# Proto_Business_Card.net
KiCad netlist of a schematic drawn in EAGLE
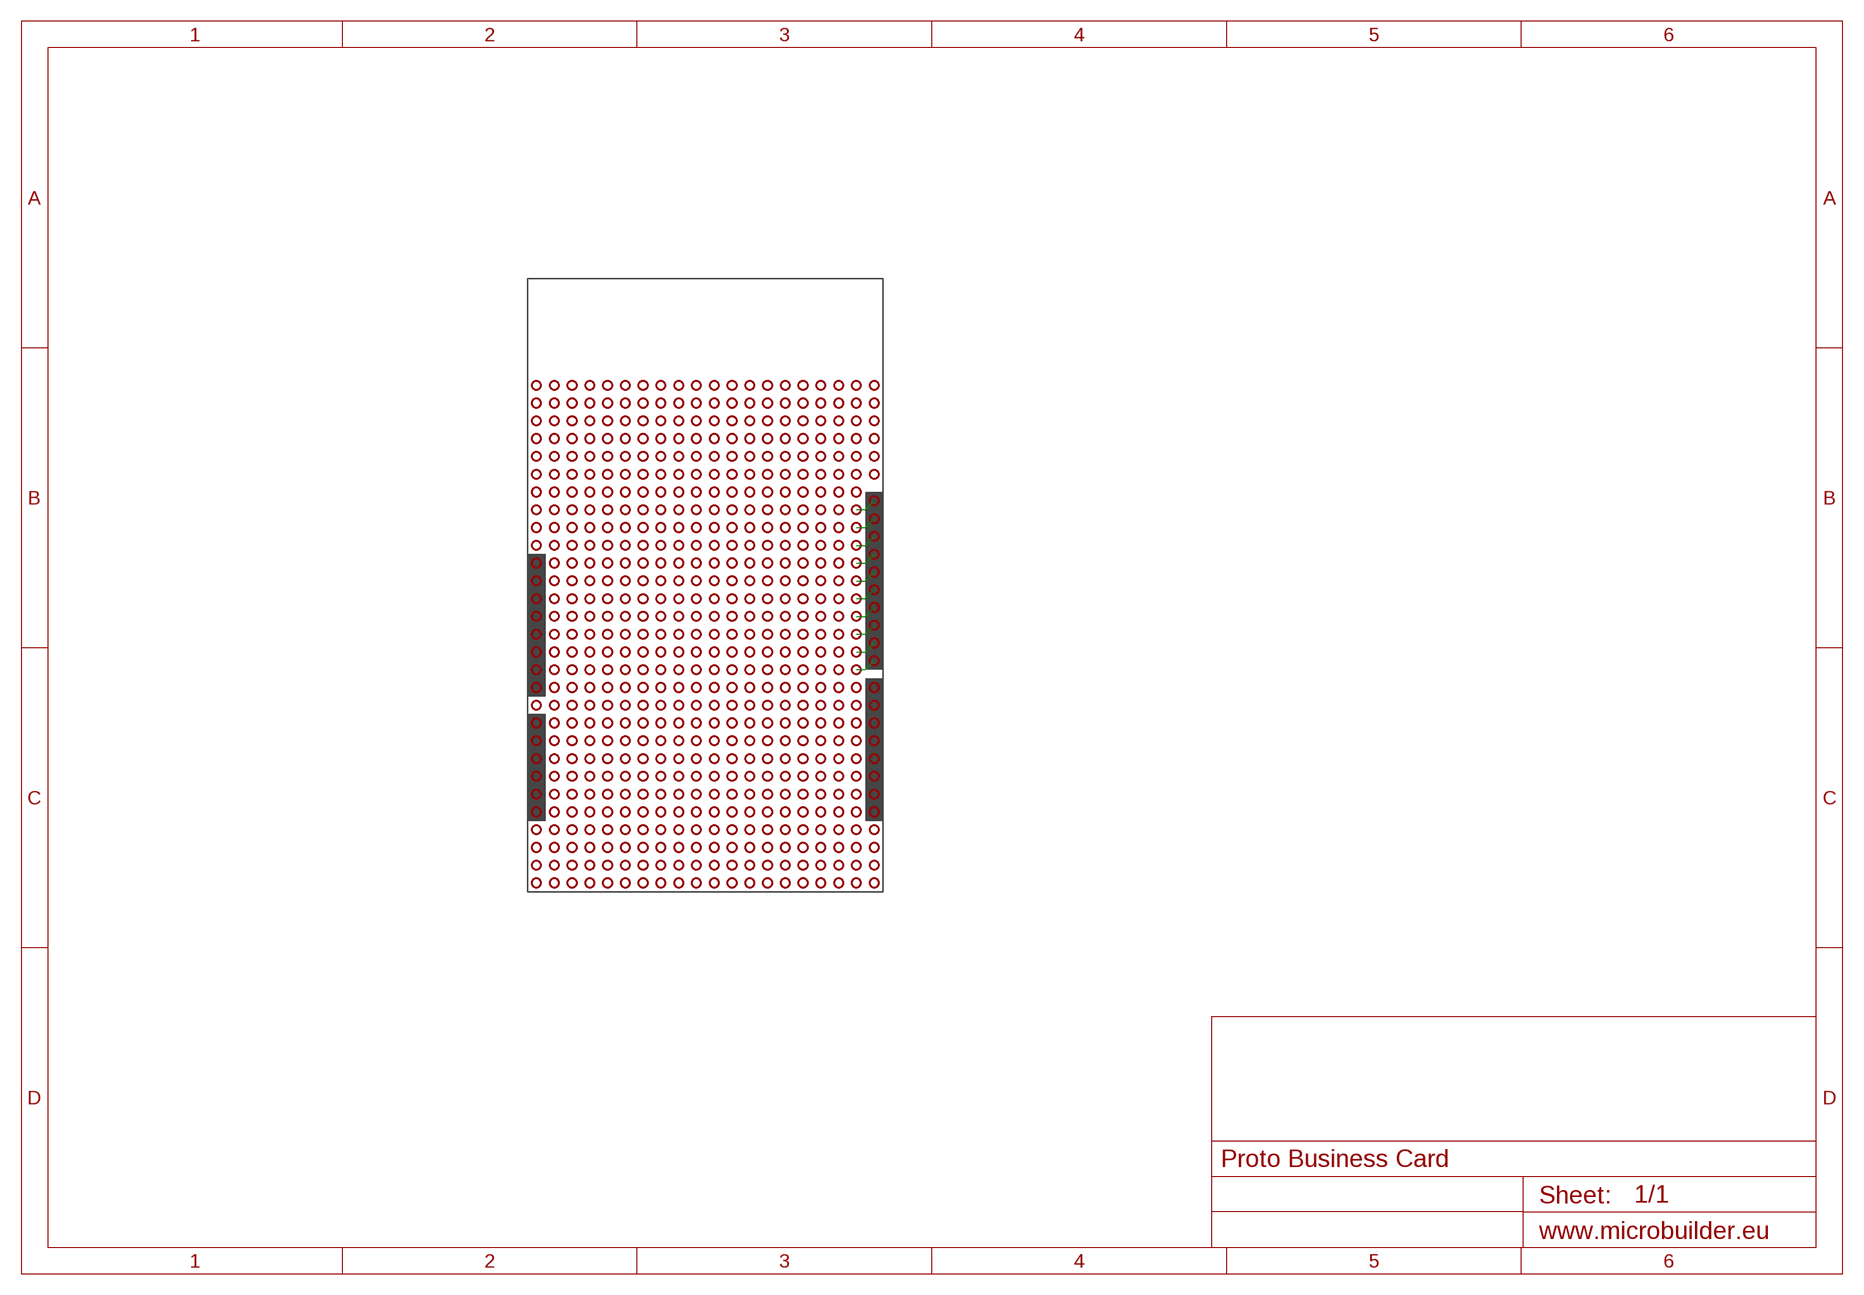
[diagram p0: schematic, sheet 1]

(export (version "E")
  (design (tool "Eeschema 10.0.6"))
  (components
    (comp (ref "U$1")
      (value "VIA.2-2.CORNER")
      (footprint "eagle-import:2-2.CORNER")
      (libsource (lib "eagle-import") (part "VIA.2-2.CORNER"))
    )
    (comp (ref "U$2")
      (value "VIA.3-3")
      (footprint "eagle-import:3-3")
      (libsource (lib "eagle-import") (part "VIA.3-3"))
    )
    (comp (ref "U$3")
      (value "VIA.2-2.CORNER")
      (footprint "eagle-import:2-2.CORNER")
      (libsource (lib "eagle-import") (part "VIA.2-2.CORNER"))
    )
    (comp (ref "U$4")
      (value "VIA.3-3")
      (footprint "eagle-import:3-3")
      (libsource (lib "eagle-import") (part "VIA.3-3"))
    )
    (comp (ref "U$5")
      (value "VIA.3-3")
      (footprint "eagle-import:3-3")
      (libsource (lib "eagle-import") (part "VIA.3-3"))
    )
    (comp (ref "U$6")
      (value "VIA.3-3")
      (footprint "eagle-import:3-3")
      (libsource (lib "eagle-import") (part "VIA.3-3"))
    )
    (comp (ref "U$7")
      (value "VIA.3-3")
      (footprint "eagle-import:3-3")
      (libsource (lib "eagle-import") (part "VIA.3-3"))
    )
    (comp (ref "U$8")
      (value "VIA.3-3")
      (footprint "eagle-import:3-3")
      (libsource (lib "eagle-import") (part "VIA.3-3"))
    )
    (comp (ref "U$9")
      (value "VIA.3-3")
      (footprint "eagle-import:3-3")
      (libsource (lib "eagle-import") (part "VIA.3-3"))
    )
    (comp (ref "U$10")
      (value "VIA.3-3")
      (footprint "eagle-import:3-3")
      (libsource (lib "eagle-import") (part "VIA.3-3"))
    )
    (comp (ref "U$11")
      (value "VIA.3-3")
      (footprint "eagle-import:3-3")
      (libsource (lib "eagle-import") (part "VIA.3-3"))
    )
    (comp (ref "U$12")
      (value "VIA.3-3")
      (footprint "eagle-import:3-3")
      (libsource (lib "eagle-import") (part "VIA.3-3"))
    )
    (comp (ref "U$13")
      (value "VIA.3-3")
      (footprint "eagle-import:3-3")
      (libsource (lib "eagle-import") (part "VIA.3-3"))
    )
    (comp (ref "U$14")
      (value "VIA.3-3")
      (footprint "eagle-import:3-3")
      (libsource (lib "eagle-import") (part "VIA.3-3"))
    )
    (comp (ref "U$15")
      (value "VIA.3-3")
      (footprint "eagle-import:3-3")
      (libsource (lib "eagle-import") (part "VIA.3-3"))
    )
    (comp (ref "U$16")
      (value "VIA.3-3")
      (footprint "eagle-import:3-3")
      (libsource (lib "eagle-import") (part "VIA.3-3"))
    )
    (comp (ref "U$17")
      (value "VIA.3-3")
      (footprint "eagle-import:3-3")
      (libsource (lib "eagle-import") (part "VIA.3-3"))
    )
    (comp (ref "U$18")
      (value "VIA.3-3")
      (footprint "eagle-import:3-3")
      (libsource (lib "eagle-import") (part "VIA.3-3"))
    )
    (comp (ref "U$19")
      (value "VIA.3-3")
      (footprint "eagle-import:3-3")
      (libsource (lib "eagle-import") (part "VIA.3-3"))
    )
    (comp (ref "U$20")
      (value "VIA.3-3")
      (footprint "eagle-import:3-3")
      (libsource (lib "eagle-import") (part "VIA.3-3"))
    )
    (comp (ref "U$21")
      (value "VIA.2-2.CORNER")
      (footprint "eagle-import:2-2.CORNER")
      (libsource (lib "eagle-import") (part "VIA.2-2.CORNER"))
    )
    (comp (ref "U$22")
      (value "VIA.3-3")
      (footprint "eagle-import:3-3")
      (libsource (lib "eagle-import") (part "VIA.3-3"))
    )
    (comp (ref "U$23")
      (value "VIA.3-3")
      (footprint "eagle-import:3-3")
      (libsource (lib "eagle-import") (part "VIA.3-3"))
    )
    (comp (ref "U$24")
      (value "VIA.3-3")
      (footprint "eagle-import:3-3")
      (libsource (lib "eagle-import") (part "VIA.3-3"))
    )
    (comp (ref "U$25")
      (value "VIA.3-3")
      (footprint "eagle-import:3-3")
      (libsource (lib "eagle-import") (part "VIA.3-3"))
    )
    (comp (ref "U$26")
      (value "VIA.3-3")
      (footprint "eagle-import:3-3")
      (libsource (lib "eagle-import") (part "VIA.3-3"))
    )
    (comp (ref "U$27")
      (value "VIA.3-3")
      (footprint "eagle-import:3-3")
      (libsource (lib "eagle-import") (part "VIA.3-3"))
    )
    (comp (ref "U$28")
      (value "VIA.3-3")
      (footprint "eagle-import:3-3")
      (libsource (lib "eagle-import") (part "VIA.3-3"))
    )
    (comp (ref "U$29")
      (value "VIA.3-3")
      (footprint "eagle-import:3-3")
      (libsource (lib "eagle-import") (part "VIA.3-3"))
    )
    (comp (ref "U$30")
      (value "VIA.3-3")
      (footprint "eagle-import:3-3")
      (libsource (lib "eagle-import") (part "VIA.3-3"))
    )
    (comp (ref "U$31")
      (value "VIA.3-3")
      (footprint "eagle-import:3-3")
      (libsource (lib "eagle-import") (part "VIA.3-3"))
    )
    (comp (ref "U$32")
      (value "VIA.3-3")
      (footprint "eagle-import:3-3")
      (libsource (lib "eagle-import") (part "VIA.3-3"))
    )
    (comp (ref "U$33")
      (value "VIA.3-3")
      (footprint "eagle-import:3-3")
      (libsource (lib "eagle-import") (part "VIA.3-3"))
    )
    (comp (ref "U$34")
      (value "VIA.3-3")
      (footprint "eagle-import:3-3")
      (libsource (lib "eagle-import") (part "VIA.3-3"))
    )
    (comp (ref "U$35")
      (value "VIA.3-3")
      (footprint "eagle-import:3-3")
      (libsource (lib "eagle-import") (part "VIA.3-3"))
    )
    (comp (ref "U$36")
      (value "VIA.3-3")
      (footprint "eagle-import:3-3")
      (libsource (lib "eagle-import") (part "VIA.3-3"))
    )
    (comp (ref "U$37")
      (value "VIA.2-2.CORNER")
      (footprint "eagle-import:2-2.CORNER")
      (libsource (lib "eagle-import") (part "VIA.2-2.CORNER"))
    )
    (comp (ref "U$38")
      (value "VIA.4-4")
      (footprint "eagle-import:4-4")
      (libsource (lib "eagle-import") (part "VIA.4-4"))
    )
    (comp (ref "U$39")
      (value "VIA.4-4")
      (footprint "eagle-import:4-4")
      (libsource (lib "eagle-import") (part "VIA.4-4"))
    )
    (comp (ref "U$40")
      (value "VIA.4-4")
      (footprint "eagle-import:4-4")
      (libsource (lib "eagle-import") (part "VIA.4-4"))
    )
    (comp (ref "U$41")
      (value "VIA.4-4")
      (footprint "eagle-import:4-4")
      (libsource (lib "eagle-import") (part "VIA.4-4"))
    )
    (comp (ref "U$42")
      (value "VIA.4-4")
      (footprint "eagle-import:4-4")
      (libsource (lib "eagle-import") (part "VIA.4-4"))
    )
    (comp (ref "U$43")
      (value "VIA.4-4")
      (footprint "eagle-import:4-4")
      (libsource (lib "eagle-import") (part "VIA.4-4"))
    )
    (comp (ref "U$44")
      (value "VIA.4-4")
      (footprint "eagle-import:4-4")
      (libsource (lib "eagle-import") (part "VIA.4-4"))
    )
    (comp (ref "U$45")
      (value "VIA.3-3")
      (footprint "eagle-import:3-3")
      (libsource (lib "eagle-import") (part "VIA.3-3"))
    )
    (comp (ref "U$46")
      (value "VIA.3-3")
      (footprint "eagle-import:3-3")
      (libsource (lib "eagle-import") (part "VIA.3-3"))
    )
    (comp (ref "U$47")
      (value "VIA.4-4")
      (footprint "eagle-import:4-4")
      (libsource (lib "eagle-import") (part "VIA.4-4"))
    )
    (comp (ref "U$48")
      (value "VIA.4-4")
      (footprint "eagle-import:4-4")
      (libsource (lib "eagle-import") (part "VIA.4-4"))
    )
    (comp (ref "U$49")
      (value "VIA.4-4")
      (footprint "eagle-import:4-4")
      (libsource (lib "eagle-import") (part "VIA.4-4"))
    )
    (comp (ref "U$50")
      (value "VIA.4-4")
      (footprint "eagle-import:4-4")
      (libsource (lib "eagle-import") (part "VIA.4-4"))
    )
    (comp (ref "U$51")
      (value "VIA.4-4")
      (footprint "eagle-import:4-4")
      (libsource (lib "eagle-import") (part "VIA.4-4"))
    )
    (comp (ref "U$52")
      (value "VIA.4-4")
      (footprint "eagle-import:4-4")
      (libsource (lib "eagle-import") (part "VIA.4-4"))
    )
    (comp (ref "U$53")
      (value "VIA.4-4")
      (footprint "eagle-import:4-4")
      (libsource (lib "eagle-import") (part "VIA.4-4"))
    )
    (comp (ref "U$54")
      (value "VIA.4-4")
      (footprint "eagle-import:4-4")
      (libsource (lib "eagle-import") (part "VIA.4-4"))
    )
    (comp (ref "U$55")
      (value "VIA.4-4")
      (footprint "eagle-import:4-4")
      (libsource (lib "eagle-import") (part "VIA.4-4"))
    )
    (comp (ref "U$56")
      (value "VIA.4-4")
      (footprint "eagle-import:4-4")
      (libsource (lib "eagle-import") (part "VIA.4-4"))
    )
    (comp (ref "U$57")
      (value "VIA.4-4")
      (footprint "eagle-import:4-4")
      (libsource (lib "eagle-import") (part "VIA.4-4"))
    )
    (comp (ref "U$58")
      (value "VIA.4-4")
      (footprint "eagle-import:4-4")
      (libsource (lib "eagle-import") (part "VIA.4-4"))
    )
    (comp (ref "U$59")
      (value "VIA.4-4")
      (footprint "eagle-import:4-4")
      (libsource (lib "eagle-import") (part "VIA.4-4"))
    )
    (comp (ref "U$60")
      (value "VIA.4-4")
      (footprint "eagle-import:4-4")
      (libsource (lib "eagle-import") (part "VIA.4-4"))
    )
    (comp (ref "U$61")
      (value "VIA.4-4")
      (footprint "eagle-import:4-4")
      (libsource (lib "eagle-import") (part "VIA.4-4"))
    )
    (comp (ref "U$62")
      (value "VIA.4-4")
      (footprint "eagle-import:4-4")
      (libsource (lib "eagle-import") (part "VIA.4-4"))
    )
    (comp (ref "U$63")
      (value "VIA.4-4")
      (footprint "eagle-import:4-4")
      (libsource (lib "eagle-import") (part "VIA.4-4"))
    )
    (comp (ref "U$64")
      (value "VIA.4-4")
      (footprint "eagle-import:4-4")
      (libsource (lib "eagle-import") (part "VIA.4-4"))
    )
    (comp (ref "U$65")
      (value "VIA.4-4")
      (footprint "eagle-import:4-4")
      (libsource (lib "eagle-import") (part "VIA.4-4"))
    )
    (comp (ref "U$66")
      (value "VIA.4-4")
      (footprint "eagle-import:4-4")
      (libsource (lib "eagle-import") (part "VIA.4-4"))
    )
    (comp (ref "U$67")
      (value "VIA.4-4")
      (footprint "eagle-import:4-4")
      (libsource (lib "eagle-import") (part "VIA.4-4"))
    )
    (comp (ref "U$68")
      (value "VIA.4-4")
      (footprint "eagle-import:4-4")
      (libsource (lib "eagle-import") (part "VIA.4-4"))
    )
    (comp (ref "U$69")
      (value "VIA.4-4")
      (footprint "eagle-import:4-4")
      (libsource (lib "eagle-import") (part "VIA.4-4"))
    )
    (comp (ref "U$70")
      (value "VIA.4-4")
      (footprint "eagle-import:4-4")
      (libsource (lib "eagle-import") (part "VIA.4-4"))
    )
    (comp (ref "U$71")
      (value "VIA.4-4")
      (footprint "eagle-import:4-4")
      (libsource (lib "eagle-import") (part "VIA.4-4"))
    )
    (comp (ref "U$72")
      (value "VIA.4-4")
      (footprint "eagle-import:4-4")
      (libsource (lib "eagle-import") (part "VIA.4-4"))
    )
    (comp (ref "U$73")
      (value "VIA.4-4")
      (footprint "eagle-import:4-4")
      (libsource (lib "eagle-import") (part "VIA.4-4"))
    )
    (comp (ref "U$74")
      (value "VIA.NONE")
      (footprint "eagle-import:NONE")
      (libsource (lib "eagle-import") (part "VIA.NONE"))
    )
    (comp (ref "U$75")
      (value "VIA.NONE")
      (footprint "eagle-import:NONE")
      (libsource (lib "eagle-import") (part "VIA.NONE"))
    )
    (comp (ref "U$76")
      (value "VIA.4-4")
      (footprint "eagle-import:4-4")
      (libsource (lib "eagle-import") (part "VIA.4-4"))
    )
    (comp (ref "U$77")
      (value "VIA.3-3")
      (footprint "eagle-import:3-3")
      (libsource (lib "eagle-import") (part "VIA.3-3"))
    )
    (comp (ref "U$78")
      (value "VIA.3-3")
      (footprint "eagle-import:3-3")
      (libsource (lib "eagle-import") (part "VIA.3-3"))
    )
    (comp (ref "U$79")
      (value "VIA.4-4")
      (footprint "eagle-import:4-4")
      (libsource (lib "eagle-import") (part "VIA.4-4"))
    )
    (comp (ref "U$80")
      (value "VIA.4-4")
      (footprint "eagle-import:4-4")
      (libsource (lib "eagle-import") (part "VIA.4-4"))
    )
    (comp (ref "U$81")
      (value "VIA.4-4")
      (footprint "eagle-import:4-4")
      (libsource (lib "eagle-import") (part "VIA.4-4"))
    )
    (comp (ref "U$82")
      (value "VIA.4-4")
      (footprint "eagle-import:4-4")
      (libsource (lib "eagle-import") (part "VIA.4-4"))
    )
    (comp (ref "U$83")
      (value "VIA.4-4")
      (footprint "eagle-import:4-4")
      (libsource (lib "eagle-import") (part "VIA.4-4"))
    )
    (comp (ref "U$84")
      (value "VIA.4-4")
      (footprint "eagle-import:4-4")
      (libsource (lib "eagle-import") (part "VIA.4-4"))
    )
    (comp (ref "U$85")
      (value "VIA.4-4")
      (footprint "eagle-import:4-4")
      (libsource (lib "eagle-import") (part "VIA.4-4"))
    )
    (comp (ref "U$86")
      (value "VIA.4-4")
      (footprint "eagle-import:4-4")
      (libsource (lib "eagle-import") (part "VIA.4-4"))
    )
    (comp (ref "U$87")
      (value "VIA.4-4")
      (footprint "eagle-import:4-4")
      (libsource (lib "eagle-import") (part "VIA.4-4"))
    )
    (comp (ref "U$88")
      (value "VIA.4-4")
      (footprint "eagle-import:4-4")
      (libsource (lib "eagle-import") (part "VIA.4-4"))
    )
    (comp (ref "U$89")
      (value "VIA.4-4")
      (footprint "eagle-import:4-4")
      (libsource (lib "eagle-import") (part "VIA.4-4"))
    )
    (comp (ref "U$90")
      (value "VIA.4-4")
      (footprint "eagle-import:4-4")
      (libsource (lib "eagle-import") (part "VIA.4-4"))
    )
    (comp (ref "U$91")
      (value "VIA.4-4")
      (footprint "eagle-import:4-4")
      (libsource (lib "eagle-import") (part "VIA.4-4"))
    )
    (comp (ref "U$92")
      (value "VIA.4-4")
      (footprint "eagle-import:4-4")
      (libsource (lib "eagle-import") (part "VIA.4-4"))
    )
    (comp (ref "U$93")
      (value "VIA.4-4")
      (footprint "eagle-import:4-4")
      (libsource (lib "eagle-import") (part "VIA.4-4"))
    )
    (comp (ref "U$94")
      (value "VIA.4-4")
      (footprint "eagle-import:4-4")
      (libsource (lib "eagle-import") (part "VIA.4-4"))
    )
    (comp (ref "U$95")
      (value "VIA.NONE")
      (footprint "eagle-import:NONE")
      (libsource (lib "eagle-import") (part "VIA.NONE"))
    )
    (comp (ref "U$96")
      (value "VIA.NONE")
      (footprint "eagle-import:NONE")
      (libsource (lib "eagle-import") (part "VIA.NONE"))
    )
    (comp (ref "U$97")
      (value "VIA.NONE")
      (footprint "eagle-import:NONE")
      (libsource (lib "eagle-import") (part "VIA.NONE"))
    )
    (comp (ref "U$98")
      (value "VIA.NONE")
      (footprint "eagle-import:NONE")
      (libsource (lib "eagle-import") (part "VIA.NONE"))
    )
    (comp (ref "U$99")
      (value "VIA.NONE")
      (footprint "eagle-import:NONE")
      (libsource (lib "eagle-import") (part "VIA.NONE"))
    )
    (comp (ref "U$100")
      (value "VIA.NONE")
      (footprint "eagle-import:NONE")
      (libsource (lib "eagle-import") (part "VIA.NONE"))
    )
    (comp (ref "U$101")
      (value "VIA.4-4")
      (footprint "eagle-import:4-4")
      (libsource (lib "eagle-import") (part "VIA.4-4"))
    )
    (comp (ref "U$102")
      (value "VIA.4-4")
      (footprint "eagle-import:4-4")
      (libsource (lib "eagle-import") (part "VIA.4-4"))
    )
    (comp (ref "U$103")
      (value "VIA.4-4")
      (footprint "eagle-import:4-4")
      (libsource (lib "eagle-import") (part "VIA.4-4"))
    )
    (comp (ref "U$104")
      (value "VIA.4-4")
      (footprint "eagle-import:4-4")
      (libsource (lib "eagle-import") (part "VIA.4-4"))
    )
    (comp (ref "U$105")
      (value "VIA.4-4")
      (footprint "eagle-import:4-4")
      (libsource (lib "eagle-import") (part "VIA.4-4"))
    )
    (comp (ref "U$106")
      (value "VIA.4-4")
      (footprint "eagle-import:4-4")
      (libsource (lib "eagle-import") (part "VIA.4-4"))
    )
    (comp (ref "U$107")
      (value "VIA.4-4")
      (footprint "eagle-import:4-4")
      (libsource (lib "eagle-import") (part "VIA.4-4"))
    )
    (comp (ref "U$108")
      (value "VIA.4-4")
      (footprint "eagle-import:4-4")
      (libsource (lib "eagle-import") (part "VIA.4-4"))
    )
    (comp (ref "U$109")
      (value "VIA.4-4")
      (footprint "eagle-import:4-4")
      (libsource (lib "eagle-import") (part "VIA.4-4"))
    )
    (comp (ref "U$110")
      (value "VIA.4-4")
      (footprint "eagle-import:4-4")
      (libsource (lib "eagle-import") (part "VIA.4-4"))
    )
    (comp (ref "U$111")
      (value "VIA.4-4")
      (footprint "eagle-import:4-4")
      (libsource (lib "eagle-import") (part "VIA.4-4"))
    )
    (comp (ref "U$112")
      (value "VIA.3-3")
      (footprint "eagle-import:3-3")
      (libsource (lib "eagle-import") (part "VIA.3-3"))
    )
    (comp (ref "U$113")
      (value "VIA.3-3")
      (footprint "eagle-import:3-3")
      (libsource (lib "eagle-import") (part "VIA.3-3"))
    )
    (comp (ref "U$114")
      (value "VIA.4-4")
      (footprint "eagle-import:4-4")
      (libsource (lib "eagle-import") (part "VIA.4-4"))
    )
    (comp (ref "U$115")
      (value "VIA.4-4")
      (footprint "eagle-import:4-4")
      (libsource (lib "eagle-import") (part "VIA.4-4"))
    )
    (comp (ref "U$116")
      (value "VIA.4-4")
      (footprint "eagle-import:4-4")
      (libsource (lib "eagle-import") (part "VIA.4-4"))
    )
    (comp (ref "U$117")
      (value "VIA.4-4")
      (footprint "eagle-import:4-4")
      (libsource (lib "eagle-import") (part "VIA.4-4"))
    )
    (comp (ref "U$118")
      (value "VIA.4-4")
      (footprint "eagle-import:4-4")
      (libsource (lib "eagle-import") (part "VIA.4-4"))
    )
    (comp (ref "U$119")
      (value "VIA.4-4")
      (footprint "eagle-import:4-4")
      (libsource (lib "eagle-import") (part "VIA.4-4"))
    )
    (comp (ref "U$120")
      (value "VIA.3-3")
      (footprint "eagle-import:3-3")
      (libsource (lib "eagle-import") (part "VIA.3-3"))
    )
    (comp (ref "U$121")
      (value "VIA.3-3")
      (footprint "eagle-import:3-3")
      (libsource (lib "eagle-import") (part "VIA.3-3"))
    )
    (comp (ref "U$122")
      (value "VIA.3-3")
      (footprint "eagle-import:3-3")
      (libsource (lib "eagle-import") (part "VIA.3-3"))
    )
    (comp (ref "U$123")
      (value "VIA.3-3")
      (footprint "eagle-import:3-3")
      (libsource (lib "eagle-import") (part "VIA.3-3"))
    )
    (comp (ref "U$124")
      (value "VIA.3-3")
      (footprint "eagle-import:3-3")
      (libsource (lib "eagle-import") (part "VIA.3-3"))
    )
    (comp (ref "U$125")
      (value "VIA.3-3")
      (footprint "eagle-import:3-3")
      (libsource (lib "eagle-import") (part "VIA.3-3"))
    )
    (comp (ref "U$126")
      (value "VIA.4-4")
      (footprint "eagle-import:4-4")
      (libsource (lib "eagle-import") (part "VIA.4-4"))
    )
    (comp (ref "U$127")
      (value "VIA.4-4")
      (footprint "eagle-import:4-4")
      (libsource (lib "eagle-import") (part "VIA.4-4"))
    )
    (comp (ref "U$128")
      (value "VIA.4-4")
      (footprint "eagle-import:4-4")
      (libsource (lib "eagle-import") (part "VIA.4-4"))
    )
    (comp (ref "U$129")
      (value "VIA.4-4")
      (footprint "eagle-import:4-4")
      (libsource (lib "eagle-import") (part "VIA.4-4"))
    )
    (comp (ref "U$130")
      (value "VIA.4-4")
      (footprint "eagle-import:4-4")
      (libsource (lib "eagle-import") (part "VIA.4-4"))
    )
    (comp (ref "U$131")
      (value "VIA.4-4")
      (footprint "eagle-import:4-4")
      (libsource (lib "eagle-import") (part "VIA.4-4"))
    )
    (comp (ref "U$132")
      (value "VIA.4-4")
      (footprint "eagle-import:4-4")
      (libsource (lib "eagle-import") (part "VIA.4-4"))
    )
    (comp (ref "U$133")
      (value "VIA.4-4")
      (footprint "eagle-import:4-4")
      (libsource (lib "eagle-import") (part "VIA.4-4"))
    )
    (comp (ref "U$134")
      (value "VIA.4-4")
      (footprint "eagle-import:4-4")
      (libsource (lib "eagle-import") (part "VIA.4-4"))
    )
    (comp (ref "U$135")
      (value "VIA.4-4")
      (footprint "eagle-import:4-4")
      (libsource (lib "eagle-import") (part "VIA.4-4"))
    )
    (comp (ref "U$136")
      (value "VIA.4-4")
      (footprint "eagle-import:4-4")
      (libsource (lib "eagle-import") (part "VIA.4-4"))
    )
    (comp (ref "U$137")
      (value "VIA.4-4")
      (footprint "eagle-import:4-4")
      (libsource (lib "eagle-import") (part "VIA.4-4"))
    )
    (comp (ref "U$138")
      (value "VIA.4-4")
      (footprint "eagle-import:4-4")
      (libsource (lib "eagle-import") (part "VIA.4-4"))
    )
    (comp (ref "U$139")
      (value "VIA.4-4")
      (footprint "eagle-import:4-4")
      (libsource (lib "eagle-import") (part "VIA.4-4"))
    )
    (comp (ref "U$140")
      (value "VIA.4-4")
      (footprint "eagle-import:4-4")
      (libsource (lib "eagle-import") (part "VIA.4-4"))
    )
    (comp (ref "U$141")
      (value "VIA.4-4")
      (footprint "eagle-import:4-4")
      (libsource (lib "eagle-import") (part "VIA.4-4"))
    )
    (comp (ref "U$142")
      (value "VIA.4-4")
      (footprint "eagle-import:4-4")
      (libsource (lib "eagle-import") (part "VIA.4-4"))
    )
    (comp (ref "U$143")
      (value "VIA.4-4")
      (footprint "eagle-import:4-4")
      (libsource (lib "eagle-import") (part "VIA.4-4"))
    )
    (comp (ref "U$144")
      (value "VIA.4-4")
      (footprint "eagle-import:4-4")
      (libsource (lib "eagle-import") (part "VIA.4-4"))
    )
    (comp (ref "U$145")
      (value "VIA.3-3")
      (footprint "eagle-import:3-3")
      (libsource (lib "eagle-import") (part "VIA.3-3"))
    )
    (comp (ref "U$146")
      (value "VIA.3-3")
      (footprint "eagle-import:3-3")
      (libsource (lib "eagle-import") (part "VIA.3-3"))
    )
    (comp (ref "U$147")
      (value "VIA.4-4")
      (footprint "eagle-import:4-4")
      (libsource (lib "eagle-import") (part "VIA.4-4"))
    )
    (comp (ref "U$148")
      (value "VIA.NONE")
      (footprint "eagle-import:NONE")
      (libsource (lib "eagle-import") (part "VIA.NONE"))
    )
    (comp (ref "U$149")
      (value "VIA.NONE")
      (footprint "eagle-import:NONE")
      (libsource (lib "eagle-import") (part "VIA.NONE"))
    )
    (comp (ref "U$150")
      (value "VIA.3-3")
      (footprint "eagle-import:3-3")
      (libsource (lib "eagle-import") (part "VIA.3-3"))
    )
    (comp (ref "U$151")
      (value "VIA.4-4")
      (footprint "eagle-import:4-4")
      (libsource (lib "eagle-import") (part "VIA.4-4"))
    )
    (comp (ref "U$152")
      (value "VIA.3-3")
      (footprint "eagle-import:3-3")
      (libsource (lib "eagle-import") (part "VIA.3-3"))
    )
    (comp (ref "U$153")
      (value "VIA.3-3")
      (footprint "eagle-import:3-3")
      (libsource (lib "eagle-import") (part "VIA.3-3"))
    )
    (comp (ref "U$154")
      (value "VIA.4-4")
      (footprint "eagle-import:4-4")
      (libsource (lib "eagle-import") (part "VIA.4-4"))
    )
    (comp (ref "U$155")
      (value "VIA.4-4")
      (footprint "eagle-import:4-4")
      (libsource (lib "eagle-import") (part "VIA.4-4"))
    )
    (comp (ref "U$156")
      (value "VIA.4-4")
      (footprint "eagle-import:4-4")
      (libsource (lib "eagle-import") (part "VIA.4-4"))
    )
    (comp (ref "U$157")
      (value "VIA.4-4")
      (footprint "eagle-import:4-4")
      (libsource (lib "eagle-import") (part "VIA.4-4"))
    )
    (comp (ref "U$158")
      (value "VIA.4-4")
      (footprint "eagle-import:4-4")
      (libsource (lib "eagle-import") (part "VIA.4-4"))
    )
    (comp (ref "U$159")
      (value "VIA.4-4")
      (footprint "eagle-import:4-4")
      (libsource (lib "eagle-import") (part "VIA.4-4"))
    )
    (comp (ref "U$160")
      (value "VIA.4-4")
      (footprint "eagle-import:4-4")
      (libsource (lib "eagle-import") (part "VIA.4-4"))
    )
    (comp (ref "U$161")
      (value "VIA.4-4")
      (footprint "eagle-import:4-4")
      (libsource (lib "eagle-import") (part "VIA.4-4"))
    )
    (comp (ref "U$162")
      (value "VIA.4-4")
      (footprint "eagle-import:4-4")
      (libsource (lib "eagle-import") (part "VIA.4-4"))
    )
    (comp (ref "U$163")
      (value "VIA.4-4")
      (footprint "eagle-import:4-4")
      (libsource (lib "eagle-import") (part "VIA.4-4"))
    )
    (comp (ref "U$164")
      (value "VIA.4-4")
      (footprint "eagle-import:4-4")
      (libsource (lib "eagle-import") (part "VIA.4-4"))
    )
    (comp (ref "U$165")
      (value "VIA.4-4")
      (footprint "eagle-import:4-4")
      (libsource (lib "eagle-import") (part "VIA.4-4"))
    )
    (comp (ref "U$166")
      (value "VIA.4-4")
      (footprint "eagle-import:4-4")
      (libsource (lib "eagle-import") (part "VIA.4-4"))
    )
    (comp (ref "U$167")
      (value "VIA.4-4")
      (footprint "eagle-import:4-4")
      (libsource (lib "eagle-import") (part "VIA.4-4"))
    )
    (comp (ref "U$168")
      (value "VIA.4-4")
      (footprint "eagle-import:4-4")
      (libsource (lib "eagle-import") (part "VIA.4-4"))
    )
    (comp (ref "U$169")
      (value "VIA.4-4")
      (footprint "eagle-import:4-4")
      (libsource (lib "eagle-import") (part "VIA.4-4"))
    )
    (comp (ref "U$170")
      (value "VIA.3-3")
      (footprint "eagle-import:3-3")
      (libsource (lib "eagle-import") (part "VIA.3-3"))
    )
    (comp (ref "U$171")
      (value "VIA.4-4")
      (footprint "eagle-import:4-4")
      (libsource (lib "eagle-import") (part "VIA.4-4"))
    )
    (comp (ref "U$172")
      (value "VIA.4-4")
      (footprint "eagle-import:4-4")
      (libsource (lib "eagle-import") (part "VIA.4-4"))
    )
    (comp (ref "U$173")
      (value "VIA.4-4")
      (footprint "eagle-import:4-4")
      (libsource (lib "eagle-import") (part "VIA.4-4"))
    )
    (comp (ref "U$174")
      (value "VIA.4-4")
      (footprint "eagle-import:4-4")
      (libsource (lib "eagle-import") (part "VIA.4-4"))
    )
    (comp (ref "U$175")
      (value "VIA.4-4")
      (footprint "eagle-import:4-4")
      (libsource (lib "eagle-import") (part "VIA.4-4"))
    )
    (comp (ref "U$176")
      (value "VIA.4-4")
      (footprint "eagle-import:4-4")
      (libsource (lib "eagle-import") (part "VIA.4-4"))
    )
    (comp (ref "U$177")
      (value "VIA.4-4")
      (footprint "eagle-import:4-4")
      (libsource (lib "eagle-import") (part "VIA.4-4"))
    )
    (comp (ref "U$178")
      (value "VIA.4-4")
      (footprint "eagle-import:4-4")
      (libsource (lib "eagle-import") (part "VIA.4-4"))
    )
    (comp (ref "U$179")
      (value "VIA.4-4")
      (footprint "eagle-import:4-4")
      (libsource (lib "eagle-import") (part "VIA.4-4"))
    )
    (comp (ref "U$180")
      (value "VIA.4-4")
      (footprint "eagle-import:4-4")
      (libsource (lib "eagle-import") (part "VIA.4-4"))
    )
    (comp (ref "U$181")
      (value "VIA.4-4")
      (footprint "eagle-import:4-4")
      (libsource (lib "eagle-import") (part "VIA.4-4"))
    )
    (comp (ref "U$182")
      (value "VIA.3-3")
      (footprint "eagle-import:3-3")
      (libsource (lib "eagle-import") (part "VIA.3-3"))
    )
    (comp (ref "U$183")
      (value "VIA.3-3")
      (footprint "eagle-import:3-3")
      (libsource (lib "eagle-import") (part "VIA.3-3"))
    )
    (comp (ref "U$184")
      (value "VIA.4-4")
      (footprint "eagle-import:4-4")
      (libsource (lib "eagle-import") (part "VIA.4-4"))
    )
    (comp (ref "U$185")
      (value "VIA.4-4")
      (footprint "eagle-import:4-4")
      (libsource (lib "eagle-import") (part "VIA.4-4"))
    )
    (comp (ref "U$186")
      (value "VIA.4-4")
      (footprint "eagle-import:4-4")
      (libsource (lib "eagle-import") (part "VIA.4-4"))
    )
    (comp (ref "U$187")
      (value "VIA.4-4")
      (footprint "eagle-import:4-4")
      (libsource (lib "eagle-import") (part "VIA.4-4"))
    )
    (comp (ref "U$188")
      (value "VIA.4-4")
      (footprint "eagle-import:4-4")
      (libsource (lib "eagle-import") (part "VIA.4-4"))
    )
    (comp (ref "U$189")
      (value "VIA.4-4")
      (footprint "eagle-import:4-4")
      (libsource (lib "eagle-import") (part "VIA.4-4"))
    )
    (comp (ref "U$190")
      (value "VIA.4-4")
      (footprint "eagle-import:4-4")
      (libsource (lib "eagle-import") (part "VIA.4-4"))
    )
    (comp (ref "U$191")
      (value "VIA.4-4")
      (footprint "eagle-import:4-4")
      (libsource (lib "eagle-import") (part "VIA.4-4"))
    )
    (comp (ref "U$192")
      (value "VIA.4-4")
      (footprint "eagle-import:4-4")
      (libsource (lib "eagle-import") (part "VIA.4-4"))
    )
    (comp (ref "U$193")
      (value "VIA.4-4")
      (footprint "eagle-import:4-4")
      (libsource (lib "eagle-import") (part "VIA.4-4"))
    )
    (comp (ref "U$194")
      (value "VIA.4-4")
      (footprint "eagle-import:4-4")
      (libsource (lib "eagle-import") (part "VIA.4-4"))
    )
    (comp (ref "U$195")
      (value "VIA.4-4")
      (footprint "eagle-import:4-4")
      (libsource (lib "eagle-import") (part "VIA.4-4"))
    )
    (comp (ref "U$196")
      (value "VIA.4-4")
      (footprint "eagle-import:4-4")
      (libsource (lib "eagle-import") (part "VIA.4-4"))
    )
    (comp (ref "U$197")
      (value "VIA.4-4")
      (footprint "eagle-import:4-4")
      (libsource (lib "eagle-import") (part "VIA.4-4"))
    )
    (comp (ref "U$198")
      (value "VIA.4-4")
      (footprint "eagle-import:4-4")
      (libsource (lib "eagle-import") (part "VIA.4-4"))
    )
    (comp (ref "U$199")
      (value "VIA.4-4")
      (footprint "eagle-import:4-4")
      (libsource (lib "eagle-import") (part "VIA.4-4"))
    )
    (comp (ref "U$200")
      (value "VIA.4-4")
      (footprint "eagle-import:4-4")
      (libsource (lib "eagle-import") (part "VIA.4-4"))
    )
    (comp (ref "U$201")
      (value "VIA.4-4")
      (footprint "eagle-import:4-4")
      (libsource (lib "eagle-import") (part "VIA.4-4"))
    )
    (comp (ref "U$202")
      (value "VIA.4-4")
      (footprint "eagle-import:4-4")
      (libsource (lib "eagle-import") (part "VIA.4-4"))
    )
    (comp (ref "U$203")
      (value "VIA.4-4")
      (footprint "eagle-import:4-4")
      (libsource (lib "eagle-import") (part "VIA.4-4"))
    )
    (comp (ref "U$204")
      (value "VIA.4-4")
      (footprint "eagle-import:4-4")
      (libsource (lib "eagle-import") (part "VIA.4-4"))
    )
    (comp (ref "U$205")
      (value "VIA.4-4")
      (footprint "eagle-import:4-4")
      (libsource (lib "eagle-import") (part "VIA.4-4"))
    )
    (comp (ref "U$206")
      (value "VIA.4-4")
      (footprint "eagle-import:4-4")
      (libsource (lib "eagle-import") (part "VIA.4-4"))
    )
    (comp (ref "U$207")
      (value "VIA.4-4")
      (footprint "eagle-import:4-4")
      (libsource (lib "eagle-import") (part "VIA.4-4"))
    )
    (comp (ref "U$208")
      (value "VIA.4-4")
      (footprint "eagle-import:4-4")
      (libsource (lib "eagle-import") (part "VIA.4-4"))
    )
    (comp (ref "U$209")
      (value "VIA.4-4")
      (footprint "eagle-import:4-4")
      (libsource (lib "eagle-import") (part "VIA.4-4"))
    )
    (comp (ref "U$210")
      (value "VIA.4-4")
      (footprint "eagle-import:4-4")
      (libsource (lib "eagle-import") (part "VIA.4-4"))
    )
    (comp (ref "U$211")
      (value "VIA.3-3")
      (footprint "eagle-import:3-3")
      (libsource (lib "eagle-import") (part "VIA.3-3"))
    )
    (comp (ref "U$212")
      (value "VIA.3-3")
      (footprint "eagle-import:3-3")
      (libsource (lib "eagle-import") (part "VIA.3-3"))
    )
    (comp (ref "U$213")
      (value "VIA.4-4")
      (footprint "eagle-import:4-4")
      (libsource (lib "eagle-import") (part "VIA.4-4"))
    )
    (comp (ref "U$214")
      (value "VIA.4-4")
      (footprint "eagle-import:4-4")
      (libsource (lib "eagle-import") (part "VIA.4-4"))
    )
    (comp (ref "U$215")
      (value "VIA.4-4")
      (footprint "eagle-import:4-4")
      (libsource (lib "eagle-import") (part "VIA.4-4"))
    )
    (comp (ref "U$216")
      (value "VIA.4-4")
      (footprint "eagle-import:4-4")
      (libsource (lib "eagle-import") (part "VIA.4-4"))
    )
    (comp (ref "U$217")
      (value "VIA.4-4")
      (footprint "eagle-import:4-4")
      (libsource (lib "eagle-import") (part "VIA.4-4"))
    )
    (comp (ref "U$218")
      (value "VIA.4-4")
      (footprint "eagle-import:4-4")
      (libsource (lib "eagle-import") (part "VIA.4-4"))
    )
    (comp (ref "U$219")
      (value "VIA.4-4")
      (footprint "eagle-import:4-4")
      (libsource (lib "eagle-import") (part "VIA.4-4"))
    )
    (comp (ref "U$220")
      (value "VIA.4-4")
      (footprint "eagle-import:4-4")
      (libsource (lib "eagle-import") (part "VIA.4-4"))
    )
    (comp (ref "U$221")
      (value "VIA.4-4")
      (footprint "eagle-import:4-4")
      (libsource (lib "eagle-import") (part "VIA.4-4"))
    )
    (comp (ref "U$222")
      (value "VIA.4-4")
      (footprint "eagle-import:4-4")
      (libsource (lib "eagle-import") (part "VIA.4-4"))
    )
    (comp (ref "U$223")
      (value "VIA.4-4")
      (footprint "eagle-import:4-4")
      (libsource (lib "eagle-import") (part "VIA.4-4"))
    )
    (comp (ref "U$224")
      (value "VIA.4-4")
      (footprint "eagle-import:4-4")
      (libsource (lib "eagle-import") (part "VIA.4-4"))
    )
    (comp (ref "U$225")
      (value "VIA.4-4")
      (footprint "eagle-import:4-4")
      (libsource (lib "eagle-import") (part "VIA.4-4"))
    )
    (comp (ref "U$226")
      (value "VIA.4-4")
      (footprint "eagle-import:4-4")
      (libsource (lib "eagle-import") (part "VIA.4-4"))
    )
    (comp (ref "U$227")
      (value "VIA.4-4")
      (footprint "eagle-import:4-4")
      (libsource (lib "eagle-import") (part "VIA.4-4"))
    )
    (comp (ref "U$228")
      (value "VIA.4-4")
      (footprint "eagle-import:4-4")
      (libsource (lib "eagle-import") (part "VIA.4-4"))
    )
    (comp (ref "U$229")
      (value "VIA.4-4")
      (footprint "eagle-import:4-4")
      (libsource (lib "eagle-import") (part "VIA.4-4"))
    )
    (comp (ref "U$230")
      (value "VIA.4-4")
      (footprint "eagle-import:4-4")
      (libsource (lib "eagle-import") (part "VIA.4-4"))
    )
    (comp (ref "U$231")
      (value "VIA.4-4")
      (footprint "eagle-import:4-4")
      (libsource (lib "eagle-import") (part "VIA.4-4"))
    )
    (comp (ref "U$232")
      (value "VIA.4-4")
      (footprint "eagle-import:4-4")
      (libsource (lib "eagle-import") (part "VIA.4-4"))
    )
    (comp (ref "U$233")
      (value "VIA.4-4")
      (footprint "eagle-import:4-4")
      (libsource (lib "eagle-import") (part "VIA.4-4"))
    )
    (comp (ref "U$234")
      (value "VIA.4-4")
      (footprint "eagle-import:4-4")
      (libsource (lib "eagle-import") (part "VIA.4-4"))
    )
    (comp (ref "U$235")
      (value "VIA.4-4")
      (footprint "eagle-import:4-4")
      (libsource (lib "eagle-import") (part "VIA.4-4"))
    )
    (comp (ref "U$236")
      (value "VIA.4-4")
      (footprint "eagle-import:4-4")
      (libsource (lib "eagle-import") (part "VIA.4-4"))
    )
    (comp (ref "U$237")
      (value "VIA.4-4")
      (footprint "eagle-import:4-4")
      (libsource (lib "eagle-import") (part "VIA.4-4"))
    )
    (comp (ref "U$238")
      (value "VIA.4-4")
      (footprint "eagle-import:4-4")
      (libsource (lib "eagle-import") (part "VIA.4-4"))
    )
    (comp (ref "U$239")
      (value "VIA.4-4")
      (footprint "eagle-import:4-4")
      (libsource (lib "eagle-import") (part "VIA.4-4"))
    )
    (comp (ref "U$240")
      (value "VIA.3-3")
      (footprint "eagle-import:3-3")
      (libsource (lib "eagle-import") (part "VIA.3-3"))
    )
    (comp (ref "U$241")
      (value "VIA.3-3")
      (footprint "eagle-import:3-3")
      (libsource (lib "eagle-import") (part "VIA.3-3"))
    )
    (comp (ref "U$242")
      (value "VIA.4-4")
      (footprint "eagle-import:4-4")
      (libsource (lib "eagle-import") (part "VIA.4-4"))
    )
    (comp (ref "U$243")
      (value "VIA.4-4")
      (footprint "eagle-import:4-4")
      (libsource (lib "eagle-import") (part "VIA.4-4"))
    )
    (comp (ref "U$244")
      (value "VIA.4-4")
      (footprint "eagle-import:4-4")
      (libsource (lib "eagle-import") (part "VIA.4-4"))
    )
    (comp (ref "U$245")
      (value "VIA.4-4")
      (footprint "eagle-import:4-4")
      (libsource (lib "eagle-import") (part "VIA.4-4"))
    )
    (comp (ref "U$246")
      (value "VIA.4-4")
      (footprint "eagle-import:4-4")
      (libsource (lib "eagle-import") (part "VIA.4-4"))
    )
    (comp (ref "U$247")
      (value "VIA.4-4")
      (footprint "eagle-import:4-4")
      (libsource (lib "eagle-import") (part "VIA.4-4"))
    )
    (comp (ref "U$248")
      (value "VIA.4-4")
      (footprint "eagle-import:4-4")
      (libsource (lib "eagle-import") (part "VIA.4-4"))
    )
    (comp (ref "U$249")
      (value "VIA.4-4")
      (footprint "eagle-import:4-4")
      (libsource (lib "eagle-import") (part "VIA.4-4"))
    )
    (comp (ref "U$250")
      (value "VIA.4-4")
      (footprint "eagle-import:4-4")
      (libsource (lib "eagle-import") (part "VIA.4-4"))
    )
    (comp (ref "U$251")
      (value "VIA.4-4")
      (footprint "eagle-import:4-4")
      (libsource (lib "eagle-import") (part "VIA.4-4"))
    )
    (comp (ref "U$252")
      (value "VIA.4-4")
      (footprint "eagle-import:4-4")
      (libsource (lib "eagle-import") (part "VIA.4-4"))
    )
    (comp (ref "U$253")
      (value "VIA.4-4")
      (footprint "eagle-import:4-4")
      (libsource (lib "eagle-import") (part "VIA.4-4"))
    )
    (comp (ref "U$254")
      (value "VIA.4-4")
      (footprint "eagle-import:4-4")
      (libsource (lib "eagle-import") (part "VIA.4-4"))
    )
    (comp (ref "U$255")
      (value "VIA.4-4")
      (footprint "eagle-import:4-4")
      (libsource (lib "eagle-import") (part "VIA.4-4"))
    )
    (comp (ref "U$256")
      (value "VIA.4-4")
      (footprint "eagle-import:4-4")
      (libsource (lib "eagle-import") (part "VIA.4-4"))
    )
    (comp (ref "U$257")
      (value "VIA.4-4")
      (footprint "eagle-import:4-4")
      (libsource (lib "eagle-import") (part "VIA.4-4"))
    )
    (comp (ref "U$258")
      (value "VIA.4-4")
      (footprint "eagle-import:4-4")
      (libsource (lib "eagle-import") (part "VIA.4-4"))
    )
    (comp (ref "U$259")
      (value "VIA.4-4")
      (footprint "eagle-import:4-4")
      (libsource (lib "eagle-import") (part "VIA.4-4"))
    )
    (comp (ref "U$260")
      (value "VIA.4-4")
      (footprint "eagle-import:4-4")
      (libsource (lib "eagle-import") (part "VIA.4-4"))
    )
    (comp (ref "U$261")
      (value "VIA.4-4")
      (footprint "eagle-import:4-4")
      (libsource (lib "eagle-import") (part "VIA.4-4"))
    )
    (comp (ref "U$262")
      (value "VIA.4-4")
      (footprint "eagle-import:4-4")
      (libsource (lib "eagle-import") (part "VIA.4-4"))
    )
    (comp (ref "U$263")
      (value "VIA.4-4")
      (footprint "eagle-import:4-4")
      (libsource (lib "eagle-import") (part "VIA.4-4"))
    )
    (comp (ref "U$264")
      (value "VIA.4-4")
      (footprint "eagle-import:4-4")
      (libsource (lib "eagle-import") (part "VIA.4-4"))
    )
    (comp (ref "U$265")
      (value "VIA.4-4")
      (footprint "eagle-import:4-4")
      (libsource (lib "eagle-import") (part "VIA.4-4"))
    )
    (comp (ref "U$266")
      (value "VIA.4-4")
      (footprint "eagle-import:4-4")
      (libsource (lib "eagle-import") (part "VIA.4-4"))
    )
    (comp (ref "U$267")
      (value "VIA.4-4")
      (footprint "eagle-import:4-4")
      (libsource (lib "eagle-import") (part "VIA.4-4"))
    )
    (comp (ref "U$268")
      (value "VIA.4-4")
      (footprint "eagle-import:4-4")
      (libsource (lib "eagle-import") (part "VIA.4-4"))
    )
    (comp (ref "U$269")
      (value "VIA.3-3")
      (footprint "eagle-import:3-3")
      (libsource (lib "eagle-import") (part "VIA.3-3"))
    )
    (comp (ref "U$270")
      (value "VIA.3-3")
      (footprint "eagle-import:3-3")
      (libsource (lib "eagle-import") (part "VIA.3-3"))
    )
    (comp (ref "U$271")
      (value "VIA.4-4")
      (footprint "eagle-import:4-4")
      (libsource (lib "eagle-import") (part "VIA.4-4"))
    )
    (comp (ref "U$272")
      (value "VIA.4-4")
      (footprint "eagle-import:4-4")
      (libsource (lib "eagle-import") (part "VIA.4-4"))
    )
    (comp (ref "U$273")
      (value "VIA.4-4")
      (footprint "eagle-import:4-4")
      (libsource (lib "eagle-import") (part "VIA.4-4"))
    )
    (comp (ref "U$274")
      (value "VIA.4-4")
      (footprint "eagle-import:4-4")
      (libsource (lib "eagle-import") (part "VIA.4-4"))
    )
    (comp (ref "U$275")
      (value "VIA.4-4")
      (footprint "eagle-import:4-4")
      (libsource (lib "eagle-import") (part "VIA.4-4"))
    )
    (comp (ref "U$276")
      (value "VIA.4-4")
      (footprint "eagle-import:4-4")
      (libsource (lib "eagle-import") (part "VIA.4-4"))
    )
    (comp (ref "U$277")
      (value "VIA.4-4")
      (footprint "eagle-import:4-4")
      (libsource (lib "eagle-import") (part "VIA.4-4"))
    )
    (comp (ref "U$278")
      (value "VIA.4-4")
      (footprint "eagle-import:4-4")
      (libsource (lib "eagle-import") (part "VIA.4-4"))
    )
    (comp (ref "U$279")
      (value "VIA.4-4")
      (footprint "eagle-import:4-4")
      (libsource (lib "eagle-import") (part "VIA.4-4"))
    )
    (comp (ref "U$280")
      (value "VIA.4-4")
      (footprint "eagle-import:4-4")
      (libsource (lib "eagle-import") (part "VIA.4-4"))
    )
    (comp (ref "U$281")
      (value "VIA.4-4")
      (footprint "eagle-import:4-4")
      (libsource (lib "eagle-import") (part "VIA.4-4"))
    )
    (comp (ref "U$282")
      (value "VIA.4-4")
      (footprint "eagle-import:4-4")
      (libsource (lib "eagle-import") (part "VIA.4-4"))
    )
    (comp (ref "U$283")
      (value "VIA.4-4")
      (footprint "eagle-import:4-4")
      (libsource (lib "eagle-import") (part "VIA.4-4"))
    )
    (comp (ref "U$284")
      (value "VIA.4-4")
      (footprint "eagle-import:4-4")
      (libsource (lib "eagle-import") (part "VIA.4-4"))
    )
    (comp (ref "U$285")
      (value "VIA.4-4")
      (footprint "eagle-import:4-4")
      (libsource (lib "eagle-import") (part "VIA.4-4"))
    )
    (comp (ref "U$286")
      (value "VIA.4-4")
      (footprint "eagle-import:4-4")
      (libsource (lib "eagle-import") (part "VIA.4-4"))
    )
    (comp (ref "U$287")
      (value "VIA.4-4")
      (footprint "eagle-import:4-4")
      (libsource (lib "eagle-import") (part "VIA.4-4"))
    )
    (comp (ref "U$288")
      (value "VIA.4-4")
      (footprint "eagle-import:4-4")
      (libsource (lib "eagle-import") (part "VIA.4-4"))
    )
    (comp (ref "U$289")
      (value "VIA.4-4")
      (footprint "eagle-import:4-4")
      (libsource (lib "eagle-import") (part "VIA.4-4"))
    )
    (comp (ref "U$290")
      (value "VIA.4-4")
      (footprint "eagle-import:4-4")
      (libsource (lib "eagle-import") (part "VIA.4-4"))
    )
    (comp (ref "U$291")
      (value "VIA.4-4")
      (footprint "eagle-import:4-4")
      (libsource (lib "eagle-import") (part "VIA.4-4"))
    )
    (comp (ref "U$292")
      (value "VIA.4-4")
      (footprint "eagle-import:4-4")
      (libsource (lib "eagle-import") (part "VIA.4-4"))
    )
    (comp (ref "U$293")
      (value "VIA.4-4")
      (footprint "eagle-import:4-4")
      (libsource (lib "eagle-import") (part "VIA.4-4"))
    )
    (comp (ref "U$294")
      (value "VIA.4-4")
      (footprint "eagle-import:4-4")
      (libsource (lib "eagle-import") (part "VIA.4-4"))
    )
    (comp (ref "U$295")
      (value "VIA.4-4")
      (footprint "eagle-import:4-4")
      (libsource (lib "eagle-import") (part "VIA.4-4"))
    )
    (comp (ref "U$296")
      (value "VIA.4-4")
      (footprint "eagle-import:4-4")
      (libsource (lib "eagle-import") (part "VIA.4-4"))
    )
    (comp (ref "U$297")
      (value "VIA.4-4")
      (footprint "eagle-import:4-4")
      (libsource (lib "eagle-import") (part "VIA.4-4"))
    )
    (comp (ref "U$298")
      (value "VIA.3-3")
      (footprint "eagle-import:3-3")
      (libsource (lib "eagle-import") (part "VIA.3-3"))
    )
    (comp (ref "U$299")
      (value "VIA.3-3")
      (footprint "eagle-import:3-3")
      (libsource (lib "eagle-import") (part "VIA.3-3"))
    )
    (comp (ref "U$300")
      (value "VIA.4-4")
      (footprint "eagle-import:4-4")
      (libsource (lib "eagle-import") (part "VIA.4-4"))
    )
    (comp (ref "U$301")
      (value "VIA.4-4")
      (footprint "eagle-import:4-4")
      (libsource (lib "eagle-import") (part "VIA.4-4"))
    )
    (comp (ref "U$302")
      (value "VIA.4-4")
      (footprint "eagle-import:4-4")
      (libsource (lib "eagle-import") (part "VIA.4-4"))
    )
    (comp (ref "U$303")
      (value "VIA.4-4")
      (footprint "eagle-import:4-4")
      (libsource (lib "eagle-import") (part "VIA.4-4"))
    )
    (comp (ref "U$304")
      (value "VIA.4-4")
      (footprint "eagle-import:4-4")
      (libsource (lib "eagle-import") (part "VIA.4-4"))
    )
    (comp (ref "U$305")
      (value "VIA.4-4")
      (footprint "eagle-import:4-4")
      (libsource (lib "eagle-import") (part "VIA.4-4"))
    )
    (comp (ref "U$306")
      (value "VIA.4-4")
      (footprint "eagle-import:4-4")
      (libsource (lib "eagle-import") (part "VIA.4-4"))
    )
    (comp (ref "U$307")
      (value "VIA.4-4")
      (footprint "eagle-import:4-4")
      (libsource (lib "eagle-import") (part "VIA.4-4"))
    )
    (comp (ref "U$308")
      (value "VIA.4-4")
      (footprint "eagle-import:4-4")
      (libsource (lib "eagle-import") (part "VIA.4-4"))
    )
    (comp (ref "U$309")
      (value "VIA.4-4")
      (footprint "eagle-import:4-4")
      (libsource (lib "eagle-import") (part "VIA.4-4"))
    )
    (comp (ref "U$310")
      (value "VIA.4-4")
      (footprint "eagle-import:4-4")
      (libsource (lib "eagle-import") (part "VIA.4-4"))
    )
    (comp (ref "U$311")
      (value "VIA.4-4")
      (footprint "eagle-import:4-4")
      (libsource (lib "eagle-import") (part "VIA.4-4"))
    )
    (comp (ref "U$312")
      (value "VIA.4-4")
      (footprint "eagle-import:4-4")
      (libsource (lib "eagle-import") (part "VIA.4-4"))
    )
    (comp (ref "U$313")
      (value "VIA.4-4")
      (footprint "eagle-import:4-4")
      (libsource (lib "eagle-import") (part "VIA.4-4"))
    )
    (comp (ref "U$314")
      (value "VIA.4-4")
      (footprint "eagle-import:4-4")
      (libsource (lib "eagle-import") (part "VIA.4-4"))
    )
    (comp (ref "U$315")
      (value "VIA.4-4")
      (footprint "eagle-import:4-4")
      (libsource (lib "eagle-import") (part "VIA.4-4"))
    )
    (comp (ref "U$316")
      (value "VIA.4-4")
      (footprint "eagle-import:4-4")
      (libsource (lib "eagle-import") (part "VIA.4-4"))
    )
    (comp (ref "U$317")
      (value "VIA.4-4")
      (footprint "eagle-import:4-4")
      (libsource (lib "eagle-import") (part "VIA.4-4"))
    )
    (comp (ref "U$318")
      (value "VIA.4-4")
      (footprint "eagle-import:4-4")
      (libsource (lib "eagle-import") (part "VIA.4-4"))
    )
    (comp (ref "U$319")
      (value "VIA.4-4")
      (footprint "eagle-import:4-4")
      (libsource (lib "eagle-import") (part "VIA.4-4"))
    )
    (comp (ref "U$320")
      (value "VIA.4-4")
      (footprint "eagle-import:4-4")
      (libsource (lib "eagle-import") (part "VIA.4-4"))
    )
    (comp (ref "U$321")
      (value "VIA.4-4")
      (footprint "eagle-import:4-4")
      (libsource (lib "eagle-import") (part "VIA.4-4"))
    )
    (comp (ref "U$322")
      (value "VIA.4-4")
      (footprint "eagle-import:4-4")
      (libsource (lib "eagle-import") (part "VIA.4-4"))
    )
    (comp (ref "U$323")
      (value "VIA.4-4")
      (footprint "eagle-import:4-4")
      (libsource (lib "eagle-import") (part "VIA.4-4"))
    )
    (comp (ref "U$324")
      (value "VIA.4-4")
      (footprint "eagle-import:4-4")
      (libsource (lib "eagle-import") (part "VIA.4-4"))
    )
    (comp (ref "U$325")
      (value "VIA.4-4")
      (footprint "eagle-import:4-4")
      (libsource (lib "eagle-import") (part "VIA.4-4"))
    )
    (comp (ref "U$326")
      (value "VIA.4-4")
      (footprint "eagle-import:4-4")
      (libsource (lib "eagle-import") (part "VIA.4-4"))
    )
    (comp (ref "U$327")
      (value "VIA.3-3")
      (footprint "eagle-import:3-3")
      (libsource (lib "eagle-import") (part "VIA.3-3"))
    )
    (comp (ref "U$328")
      (value "VIA.3-3")
      (footprint "eagle-import:3-3")
      (libsource (lib "eagle-import") (part "VIA.3-3"))
    )
    (comp (ref "U$329")
      (value "VIA.4-4")
      (footprint "eagle-import:4-4")
      (libsource (lib "eagle-import") (part "VIA.4-4"))
    )
    (comp (ref "U$330")
      (value "VIA.4-4")
      (footprint "eagle-import:4-4")
      (libsource (lib "eagle-import") (part "VIA.4-4"))
    )
    (comp (ref "U$331")
      (value "VIA.4-4")
      (footprint "eagle-import:4-4")
      (libsource (lib "eagle-import") (part "VIA.4-4"))
    )
    (comp (ref "U$332")
      (value "VIA.4-4")
      (footprint "eagle-import:4-4")
      (libsource (lib "eagle-import") (part "VIA.4-4"))
    )
    (comp (ref "U$333")
      (value "VIA.4-4")
      (footprint "eagle-import:4-4")
      (libsource (lib "eagle-import") (part "VIA.4-4"))
    )
    (comp (ref "U$334")
      (value "VIA.4-4")
      (footprint "eagle-import:4-4")
      (libsource (lib "eagle-import") (part "VIA.4-4"))
    )
    (comp (ref "U$335")
      (value "VIA.4-4")
      (footprint "eagle-import:4-4")
      (libsource (lib "eagle-import") (part "VIA.4-4"))
    )
    (comp (ref "U$336")
      (value "VIA.4-4")
      (footprint "eagle-import:4-4")
      (libsource (lib "eagle-import") (part "VIA.4-4"))
    )
    (comp (ref "U$337")
      (value "VIA.4-4")
      (footprint "eagle-import:4-4")
      (libsource (lib "eagle-import") (part "VIA.4-4"))
    )
    (comp (ref "U$338")
      (value "VIA.4-4")
      (footprint "eagle-import:4-4")
      (libsource (lib "eagle-import") (part "VIA.4-4"))
    )
    (comp (ref "U$339")
      (value "VIA.4-4")
      (footprint "eagle-import:4-4")
      (libsource (lib "eagle-import") (part "VIA.4-4"))
    )
    (comp (ref "U$340")
      (value "VIA.4-4")
      (footprint "eagle-import:4-4")
      (libsource (lib "eagle-import") (part "VIA.4-4"))
    )
    (comp (ref "U$341")
      (value "VIA.4-4")
      (footprint "eagle-import:4-4")
      (libsource (lib "eagle-import") (part "VIA.4-4"))
    )
    (comp (ref "U$342")
      (value "VIA.4-4")
      (footprint "eagle-import:4-4")
      (libsource (lib "eagle-import") (part "VIA.4-4"))
    )
    (comp (ref "U$343")
      (value "VIA.4-4")
      (footprint "eagle-import:4-4")
      (libsource (lib "eagle-import") (part "VIA.4-4"))
    )
    (comp (ref "U$344")
      (value "VIA.4-4")
      (footprint "eagle-import:4-4")
      (libsource (lib "eagle-import") (part "VIA.4-4"))
    )
    (comp (ref "U$345")
      (value "VIA.4-4")
      (footprint "eagle-import:4-4")
      (libsource (lib "eagle-import") (part "VIA.4-4"))
    )
    (comp (ref "U$346")
      (value "VIA.4-4")
      (footprint "eagle-import:4-4")
      (libsource (lib "eagle-import") (part "VIA.4-4"))
    )
    (comp (ref "U$347")
      (value "VIA.4-4")
      (footprint "eagle-import:4-4")
      (libsource (lib "eagle-import") (part "VIA.4-4"))
    )
    (comp (ref "U$348")
      (value "VIA.4-4")
      (footprint "eagle-import:4-4")
      (libsource (lib "eagle-import") (part "VIA.4-4"))
    )
    (comp (ref "U$349")
      (value "VIA.4-4")
      (footprint "eagle-import:4-4")
      (libsource (lib "eagle-import") (part "VIA.4-4"))
    )
    (comp (ref "U$350")
      (value "VIA.4-4")
      (footprint "eagle-import:4-4")
      (libsource (lib "eagle-import") (part "VIA.4-4"))
    )
    (comp (ref "U$351")
      (value "VIA.4-4")
      (footprint "eagle-import:4-4")
      (libsource (lib "eagle-import") (part "VIA.4-4"))
    )
    (comp (ref "U$352")
      (value "VIA.4-4")
      (footprint "eagle-import:4-4")
      (libsource (lib "eagle-import") (part "VIA.4-4"))
    )
    (comp (ref "U$353")
      (value "VIA.4-4")
      (footprint "eagle-import:4-4")
      (libsource (lib "eagle-import") (part "VIA.4-4"))
    )
    (comp (ref "U$354")
      (value "VIA.4-4")
      (footprint "eagle-import:4-4")
      (libsource (lib "eagle-import") (part "VIA.4-4"))
    )
    (comp (ref "U$355")
      (value "VIA.4-4")
      (footprint "eagle-import:4-4")
      (libsource (lib "eagle-import") (part "VIA.4-4"))
    )
    (comp (ref "U$356")
      (value "VIA.3-3")
      (footprint "eagle-import:3-3")
      (libsource (lib "eagle-import") (part "VIA.3-3"))
    )
    (comp (ref "U$357")
      (value "VIA.3-3")
      (footprint "eagle-import:3-3")
      (libsource (lib "eagle-import") (part "VIA.3-3"))
    )
    (comp (ref "U$358")
      (value "VIA.4-4")
      (footprint "eagle-import:4-4")
      (libsource (lib "eagle-import") (part "VIA.4-4"))
    )
    (comp (ref "U$359")
      (value "VIA.4-4")
      (footprint "eagle-import:4-4")
      (libsource (lib "eagle-import") (part "VIA.4-4"))
    )
    (comp (ref "U$360")
      (value "VIA.4-4")
      (footprint "eagle-import:4-4")
      (libsource (lib "eagle-import") (part "VIA.4-4"))
    )
    (comp (ref "U$361")
      (value "VIA.4-4")
      (footprint "eagle-import:4-4")
      (libsource (lib "eagle-import") (part "VIA.4-4"))
    )
    (comp (ref "U$362")
      (value "VIA.4-4")
      (footprint "eagle-import:4-4")
      (libsource (lib "eagle-import") (part "VIA.4-4"))
    )
    (comp (ref "U$363")
      (value "VIA.4-4")
      (footprint "eagle-import:4-4")
      (libsource (lib "eagle-import") (part "VIA.4-4"))
    )
    (comp (ref "U$364")
      (value "VIA.4-4")
      (footprint "eagle-import:4-4")
      (libsource (lib "eagle-import") (part "VIA.4-4"))
    )
    (comp (ref "U$365")
      (value "VIA.4-4")
      (footprint "eagle-import:4-4")
      (libsource (lib "eagle-import") (part "VIA.4-4"))
    )
    (comp (ref "U$366")
      (value "VIA.4-4")
      (footprint "eagle-import:4-4")
      (libsource (lib "eagle-import") (part "VIA.4-4"))
    )
    (comp (ref "U$367")
      (value "VIA.4-4")
      (footprint "eagle-import:4-4")
      (libsource (lib "eagle-import") (part "VIA.4-4"))
    )
    (comp (ref "U$368")
      (value "VIA.4-4")
      (footprint "eagle-import:4-4")
      (libsource (lib "eagle-import") (part "VIA.4-4"))
    )
    (comp (ref "U$369")
      (value "VIA.4-4")
      (footprint "eagle-import:4-4")
      (libsource (lib "eagle-import") (part "VIA.4-4"))
    )
    (comp (ref "U$370")
      (value "VIA.4-4")
      (footprint "eagle-import:4-4")
      (libsource (lib "eagle-import") (part "VIA.4-4"))
    )
    (comp (ref "U$371")
      (value "VIA.4-4")
      (footprint "eagle-import:4-4")
      (libsource (lib "eagle-import") (part "VIA.4-4"))
    )
    (comp (ref "U$372")
      (value "VIA.4-4")
      (footprint "eagle-import:4-4")
      (libsource (lib "eagle-import") (part "VIA.4-4"))
    )
    (comp (ref "U$373")
      (value "VIA.4-4")
      (footprint "eagle-import:4-4")
      (libsource (lib "eagle-import") (part "VIA.4-4"))
    )
    (comp (ref "U$374")
      (value "VIA.4-4")
      (footprint "eagle-import:4-4")
      (libsource (lib "eagle-import") (part "VIA.4-4"))
    )
    (comp (ref "U$375")
      (value "VIA.4-4")
      (footprint "eagle-import:4-4")
      (libsource (lib "eagle-import") (part "VIA.4-4"))
    )
    (comp (ref "U$376")
      (value "VIA.4-4")
      (footprint "eagle-import:4-4")
      (libsource (lib "eagle-import") (part "VIA.4-4"))
    )
    (comp (ref "U$377")
      (value "VIA.4-4")
      (footprint "eagle-import:4-4")
      (libsource (lib "eagle-import") (part "VIA.4-4"))
    )
    (comp (ref "U$378")
      (value "VIA.4-4")
      (footprint "eagle-import:4-4")
      (libsource (lib "eagle-import") (part "VIA.4-4"))
    )
    (comp (ref "U$379")
      (value "VIA.4-4")
      (footprint "eagle-import:4-4")
      (libsource (lib "eagle-import") (part "VIA.4-4"))
    )
    (comp (ref "U$380")
      (value "VIA.4-4")
      (footprint "eagle-import:4-4")
      (libsource (lib "eagle-import") (part "VIA.4-4"))
    )
    (comp (ref "U$381")
      (value "VIA.4-4")
      (footprint "eagle-import:4-4")
      (libsource (lib "eagle-import") (part "VIA.4-4"))
    )
    (comp (ref "U$382")
      (value "VIA.4-4")
      (footprint "eagle-import:4-4")
      (libsource (lib "eagle-import") (part "VIA.4-4"))
    )
    (comp (ref "U$383")
      (value "VIA.4-4")
      (footprint "eagle-import:4-4")
      (libsource (lib "eagle-import") (part "VIA.4-4"))
    )
    (comp (ref "U$384")
      (value "VIA.4-4")
      (footprint "eagle-import:4-4")
      (libsource (lib "eagle-import") (part "VIA.4-4"))
    )
    (comp (ref "U$385")
      (value "VIA.3-3")
      (footprint "eagle-import:3-3")
      (libsource (lib "eagle-import") (part "VIA.3-3"))
    )
    (comp (ref "U$386")
      (value "VIA.3-3")
      (footprint "eagle-import:3-3")
      (libsource (lib "eagle-import") (part "VIA.3-3"))
    )
    (comp (ref "U$387")
      (value "VIA.4-4")
      (footprint "eagle-import:4-4")
      (libsource (lib "eagle-import") (part "VIA.4-4"))
    )
    (comp (ref "U$388")
      (value "VIA.4-4")
      (footprint "eagle-import:4-4")
      (libsource (lib "eagle-import") (part "VIA.4-4"))
    )
    (comp (ref "U$389")
      (value "VIA.4-4")
      (footprint "eagle-import:4-4")
      (libsource (lib "eagle-import") (part "VIA.4-4"))
    )
    (comp (ref "U$390")
      (value "VIA.4-4")
      (footprint "eagle-import:4-4")
      (libsource (lib "eagle-import") (part "VIA.4-4"))
    )
    (comp (ref "U$391")
      (value "VIA.4-4")
      (footprint "eagle-import:4-4")
      (libsource (lib "eagle-import") (part "VIA.4-4"))
    )
    (comp (ref "U$392")
      (value "VIA.4-4")
      (footprint "eagle-import:4-4")
      (libsource (lib "eagle-import") (part "VIA.4-4"))
    )
    (comp (ref "U$393")
      (value "VIA.4-4")
      (footprint "eagle-import:4-4")
      (libsource (lib "eagle-import") (part "VIA.4-4"))
    )
    (comp (ref "U$394")
      (value "VIA.4-4")
      (footprint "eagle-import:4-4")
      (libsource (lib "eagle-import") (part "VIA.4-4"))
    )
    (comp (ref "U$395")
      (value "VIA.4-4")
      (footprint "eagle-import:4-4")
      (libsource (lib "eagle-import") (part "VIA.4-4"))
    )
    (comp (ref "U$396")
      (value "VIA.4-4")
      (footprint "eagle-import:4-4")
      (libsource (lib "eagle-import") (part "VIA.4-4"))
    )
    (comp (ref "U$397")
      (value "VIA.4-4")
      (footprint "eagle-import:4-4")
      (libsource (lib "eagle-import") (part "VIA.4-4"))
    )
    (comp (ref "U$398")
      (value "VIA.4-4")
      (footprint "eagle-import:4-4")
      (libsource (lib "eagle-import") (part "VIA.4-4"))
    )
    (comp (ref "U$399")
      (value "VIA.4-4")
      (footprint "eagle-import:4-4")
      (libsource (lib "eagle-import") (part "VIA.4-4"))
    )
    (comp (ref "U$400")
      (value "VIA.4-4")
      (footprint "eagle-import:4-4")
      (libsource (lib "eagle-import") (part "VIA.4-4"))
    )
    (comp (ref "U$401")
      (value "VIA.4-4")
      (footprint "eagle-import:4-4")
      (libsource (lib "eagle-import") (part "VIA.4-4"))
    )
    (comp (ref "U$402")
      (value "VIA.4-4")
      (footprint "eagle-import:4-4")
      (libsource (lib "eagle-import") (part "VIA.4-4"))
    )
    (comp (ref "U$403")
      (value "VIA.4-4")
      (footprint "eagle-import:4-4")
      (libsource (lib "eagle-import") (part "VIA.4-4"))
    )
    (comp (ref "U$404")
      (value "VIA.4-4")
      (footprint "eagle-import:4-4")
      (libsource (lib "eagle-import") (part "VIA.4-4"))
    )
    (comp (ref "U$405")
      (value "VIA.4-4")
      (footprint "eagle-import:4-4")
      (libsource (lib "eagle-import") (part "VIA.4-4"))
    )
    (comp (ref "U$406")
      (value "VIA.4-4")
      (footprint "eagle-import:4-4")
      (libsource (lib "eagle-import") (part "VIA.4-4"))
    )
    (comp (ref "U$407")
      (value "VIA.4-4")
      (footprint "eagle-import:4-4")
      (libsource (lib "eagle-import") (part "VIA.4-4"))
    )
    (comp (ref "U$408")
      (value "VIA.4-4")
      (footprint "eagle-import:4-4")
      (libsource (lib "eagle-import") (part "VIA.4-4"))
    )
    (comp (ref "U$409")
      (value "VIA.4-4")
      (footprint "eagle-import:4-4")
      (libsource (lib "eagle-import") (part "VIA.4-4"))
    )
    (comp (ref "U$410")
      (value "VIA.4-4")
      (footprint "eagle-import:4-4")
      (libsource (lib "eagle-import") (part "VIA.4-4"))
    )
    (comp (ref "U$411")
      (value "VIA.4-4")
      (footprint "eagle-import:4-4")
      (libsource (lib "eagle-import") (part "VIA.4-4"))
    )
    (comp (ref "U$412")
      (value "VIA.4-4")
      (footprint "eagle-import:4-4")
      (libsource (lib "eagle-import") (part "VIA.4-4"))
    )
    (comp (ref "U$413")
      (value "VIA.4-4")
      (footprint "eagle-import:4-4")
      (libsource (lib "eagle-import") (part "VIA.4-4"))
    )
    (comp (ref "U$414")
      (value "VIA.3-3")
      (footprint "eagle-import:3-3")
      (libsource (lib "eagle-import") (part "VIA.3-3"))
    )
    (comp (ref "U$415")
      (value "VIA.3-3")
      (footprint "eagle-import:3-3")
      (libsource (lib "eagle-import") (part "VIA.3-3"))
    )
    (comp (ref "U$416")
      (value "VIA.4-4")
      (footprint "eagle-import:4-4")
      (libsource (lib "eagle-import") (part "VIA.4-4"))
    )
    (comp (ref "U$417")
      (value "VIA.4-4")
      (footprint "eagle-import:4-4")
      (libsource (lib "eagle-import") (part "VIA.4-4"))
    )
    (comp (ref "U$418")
      (value "VIA.4-4")
      (footprint "eagle-import:4-4")
      (libsource (lib "eagle-import") (part "VIA.4-4"))
    )
    (comp (ref "U$419")
      (value "VIA.4-4")
      (footprint "eagle-import:4-4")
      (libsource (lib "eagle-import") (part "VIA.4-4"))
    )
    (comp (ref "U$420")
      (value "VIA.4-4")
      (footprint "eagle-import:4-4")
      (libsource (lib "eagle-import") (part "VIA.4-4"))
    )
    (comp (ref "U$421")
      (value "VIA.4-4")
      (footprint "eagle-import:4-4")
      (libsource (lib "eagle-import") (part "VIA.4-4"))
    )
    (comp (ref "U$422")
      (value "VIA.4-4")
      (footprint "eagle-import:4-4")
      (libsource (lib "eagle-import") (part "VIA.4-4"))
    )
    (comp (ref "U$423")
      (value "VIA.4-4")
      (footprint "eagle-import:4-4")
      (libsource (lib "eagle-import") (part "VIA.4-4"))
    )
    (comp (ref "U$424")
      (value "VIA.4-4")
      (footprint "eagle-import:4-4")
      (libsource (lib "eagle-import") (part "VIA.4-4"))
    )
    (comp (ref "U$425")
      (value "VIA.4-4")
      (footprint "eagle-import:4-4")
      (libsource (lib "eagle-import") (part "VIA.4-4"))
    )
    (comp (ref "U$426")
      (value "VIA.4-4")
      (footprint "eagle-import:4-4")
      (libsource (lib "eagle-import") (part "VIA.4-4"))
    )
    (comp (ref "U$427")
      (value "VIA.4-4")
      (footprint "eagle-import:4-4")
      (libsource (lib "eagle-import") (part "VIA.4-4"))
    )
    (comp (ref "U$428")
      (value "VIA.4-4")
      (footprint "eagle-import:4-4")
      (libsource (lib "eagle-import") (part "VIA.4-4"))
    )
    (comp (ref "U$429")
      (value "VIA.4-4")
      (footprint "eagle-import:4-4")
      (libsource (lib "eagle-import") (part "VIA.4-4"))
    )
    (comp (ref "U$430")
      (value "VIA.4-4")
      (footprint "eagle-import:4-4")
      (libsource (lib "eagle-import") (part "VIA.4-4"))
    )
    (comp (ref "U$431")
      (value "VIA.4-4")
      (footprint "eagle-import:4-4")
      (libsource (lib "eagle-import") (part "VIA.4-4"))
    )
    (comp (ref "U$432")
      (value "VIA.4-4")
      (footprint "eagle-import:4-4")
      (libsource (lib "eagle-import") (part "VIA.4-4"))
    )
    (comp (ref "U$433")
      (value "VIA.4-4")
      (footprint "eagle-import:4-4")
      (libsource (lib "eagle-import") (part "VIA.4-4"))
    )
    (comp (ref "U$434")
      (value "VIA.4-4")
      (footprint "eagle-import:4-4")
      (libsource (lib "eagle-import") (part "VIA.4-4"))
    )
    (comp (ref "U$435")
      (value "VIA.4-4")
      (footprint "eagle-import:4-4")
      (libsource (lib "eagle-import") (part "VIA.4-4"))
    )
    (comp (ref "U$436")
      (value "VIA.4-4")
      (footprint "eagle-import:4-4")
      (libsource (lib "eagle-import") (part "VIA.4-4"))
    )
    (comp (ref "U$437")
      (value "VIA.4-4")
      (footprint "eagle-import:4-4")
      (libsource (lib "eagle-import") (part "VIA.4-4"))
    )
    (comp (ref "U$438")
      (value "VIA.4-4")
      (footprint "eagle-import:4-4")
      (libsource (lib "eagle-import") (part "VIA.4-4"))
    )
    (comp (ref "U$439")
      (value "VIA.4-4")
      (footprint "eagle-import:4-4")
      (libsource (lib "eagle-import") (part "VIA.4-4"))
    )
    (comp (ref "U$440")
      (value "VIA.4-4")
      (footprint "eagle-import:4-4")
      (libsource (lib "eagle-import") (part "VIA.4-4"))
    )
    (comp (ref "U$441")
      (value "VIA.4-4")
      (footprint "eagle-import:4-4")
      (libsource (lib "eagle-import") (part "VIA.4-4"))
    )
    (comp (ref "U$442")
      (value "VIA.4-4")
      (footprint "eagle-import:4-4")
      (libsource (lib "eagle-import") (part "VIA.4-4"))
    )
    (comp (ref "U$443")
      (value "VIA.3-3")
      (footprint "eagle-import:3-3")
      (libsource (lib "eagle-import") (part "VIA.3-3"))
    )
    (comp (ref "U$444")
      (value "VIA.3-3")
      (footprint "eagle-import:3-3")
      (libsource (lib "eagle-import") (part "VIA.3-3"))
    )
    (comp (ref "U$445")
      (value "VIA.4-4")
      (footprint "eagle-import:4-4")
      (libsource (lib "eagle-import") (part "VIA.4-4"))
    )
    (comp (ref "U$446")
      (value "VIA.4-4")
      (footprint "eagle-import:4-4")
      (libsource (lib "eagle-import") (part "VIA.4-4"))
    )
    (comp (ref "U$447")
      (value "VIA.4-4")
      (footprint "eagle-import:4-4")
      (libsource (lib "eagle-import") (part "VIA.4-4"))
    )
    (comp (ref "U$448")
      (value "VIA.4-4")
      (footprint "eagle-import:4-4")
      (libsource (lib "eagle-import") (part "VIA.4-4"))
    )
    (comp (ref "U$449")
      (value "VIA.4-4")
      (footprint "eagle-import:4-4")
      (libsource (lib "eagle-import") (part "VIA.4-4"))
    )
    (comp (ref "U$450")
      (value "VIA.4-4")
      (footprint "eagle-import:4-4")
      (libsource (lib "eagle-import") (part "VIA.4-4"))
    )
    (comp (ref "U$451")
      (value "VIA.4-4")
      (footprint "eagle-import:4-4")
      (libsource (lib "eagle-import") (part "VIA.4-4"))
    )
    (comp (ref "U$452")
      (value "VIA.4-4")
      (footprint "eagle-import:4-4")
      (libsource (lib "eagle-import") (part "VIA.4-4"))
    )
    (comp (ref "U$453")
      (value "VIA.4-4")
      (footprint "eagle-import:4-4")
      (libsource (lib "eagle-import") (part "VIA.4-4"))
    )
    (comp (ref "U$454")
      (value "VIA.4-4")
      (footprint "eagle-import:4-4")
      (libsource (lib "eagle-import") (part "VIA.4-4"))
    )
    (comp (ref "U$455")
      (value "VIA.4-4")
      (footprint "eagle-import:4-4")
      (libsource (lib "eagle-import") (part "VIA.4-4"))
    )
    (comp (ref "U$456")
      (value "VIA.4-4")
      (footprint "eagle-import:4-4")
      (libsource (lib "eagle-import") (part "VIA.4-4"))
    )
    (comp (ref "U$457")
      (value "VIA.4-4")
      (footprint "eagle-import:4-4")
      (libsource (lib "eagle-import") (part "VIA.4-4"))
    )
    (comp (ref "U$458")
      (value "VIA.4-4")
      (footprint "eagle-import:4-4")
      (libsource (lib "eagle-import") (part "VIA.4-4"))
    )
    (comp (ref "U$459")
      (value "VIA.4-4")
      (footprint "eagle-import:4-4")
      (libsource (lib "eagle-import") (part "VIA.4-4"))
    )
    (comp (ref "U$460")
      (value "VIA.4-4")
      (footprint "eagle-import:4-4")
      (libsource (lib "eagle-import") (part "VIA.4-4"))
    )
    (comp (ref "U$461")
      (value "VIA.4-4")
      (footprint "eagle-import:4-4")
      (libsource (lib "eagle-import") (part "VIA.4-4"))
    )
    (comp (ref "U$462")
      (value "VIA.4-4")
      (footprint "eagle-import:4-4")
      (libsource (lib "eagle-import") (part "VIA.4-4"))
    )
    (comp (ref "U$463")
      (value "VIA.4-4")
      (footprint "eagle-import:4-4")
      (libsource (lib "eagle-import") (part "VIA.4-4"))
    )
    (comp (ref "U$464")
      (value "VIA.4-4")
      (footprint "eagle-import:4-4")
      (libsource (lib "eagle-import") (part "VIA.4-4"))
    )
    (comp (ref "U$465")
      (value "VIA.4-4")
      (footprint "eagle-import:4-4")
      (libsource (lib "eagle-import") (part "VIA.4-4"))
    )
    (comp (ref "U$466")
      (value "VIA.4-4")
      (footprint "eagle-import:4-4")
      (libsource (lib "eagle-import") (part "VIA.4-4"))
    )
    (comp (ref "U$467")
      (value "VIA.4-4")
      (footprint "eagle-import:4-4")
      (libsource (lib "eagle-import") (part "VIA.4-4"))
    )
    (comp (ref "U$468")
      (value "VIA.4-4")
      (footprint "eagle-import:4-4")
      (libsource (lib "eagle-import") (part "VIA.4-4"))
    )
    (comp (ref "U$469")
      (value "VIA.4-4")
      (footprint "eagle-import:4-4")
      (libsource (lib "eagle-import") (part "VIA.4-4"))
    )
    (comp (ref "U$470")
      (value "VIA.4-4")
      (footprint "eagle-import:4-4")
      (libsource (lib "eagle-import") (part "VIA.4-4"))
    )
    (comp (ref "U$471")
      (value "VIA.4-4")
      (footprint "eagle-import:4-4")
      (libsource (lib "eagle-import") (part "VIA.4-4"))
    )
    (comp (ref "U$472")
      (value "VIA.3-3")
      (footprint "eagle-import:3-3")
      (libsource (lib "eagle-import") (part "VIA.3-3"))
    )
    (comp (ref "U$473")
      (value "VIA.3-3")
      (footprint "eagle-import:3-3")
      (libsource (lib "eagle-import") (part "VIA.3-3"))
    )
    (comp (ref "U$474")
      (value "VIA.4-4")
      (footprint "eagle-import:4-4")
      (libsource (lib "eagle-import") (part "VIA.4-4"))
    )
    (comp (ref "U$475")
      (value "VIA.4-4")
      (footprint "eagle-import:4-4")
      (libsource (lib "eagle-import") (part "VIA.4-4"))
    )
    (comp (ref "U$476")
      (value "VIA.4-4")
      (footprint "eagle-import:4-4")
      (libsource (lib "eagle-import") (part "VIA.4-4"))
    )
    (comp (ref "U$477")
      (value "VIA.4-4")
      (footprint "eagle-import:4-4")
      (libsource (lib "eagle-import") (part "VIA.4-4"))
    )
    (comp (ref "U$478")
      (value "VIA.4-4")
      (footprint "eagle-import:4-4")
      (libsource (lib "eagle-import") (part "VIA.4-4"))
    )
    (comp (ref "U$479")
      (value "VIA.4-4")
      (footprint "eagle-import:4-4")
      (libsource (lib "eagle-import") (part "VIA.4-4"))
    )
    (comp (ref "U$480")
      (value "VIA.4-4")
      (footprint "eagle-import:4-4")
      (libsource (lib "eagle-import") (part "VIA.4-4"))
    )
    (comp (ref "U$481")
      (value "VIA.4-4")
      (footprint "eagle-import:4-4")
      (libsource (lib "eagle-import") (part "VIA.4-4"))
    )
    (comp (ref "U$482")
      (value "VIA.4-4")
      (footprint "eagle-import:4-4")
      (libsource (lib "eagle-import") (part "VIA.4-4"))
    )
    (comp (ref "U$483")
      (value "VIA.4-4")
      (footprint "eagle-import:4-4")
      (libsource (lib "eagle-import") (part "VIA.4-4"))
    )
    (comp (ref "U$484")
      (value "VIA.4-4")
      (footprint "eagle-import:4-4")
      (libsource (lib "eagle-import") (part "VIA.4-4"))
    )
    (comp (ref "U$485")
      (value "VIA.4-4")
      (footprint "eagle-import:4-4")
      (libsource (lib "eagle-import") (part "VIA.4-4"))
    )
    (comp (ref "U$486")
      (value "VIA.4-4")
      (footprint "eagle-import:4-4")
      (libsource (lib "eagle-import") (part "VIA.4-4"))
    )
    (comp (ref "U$487")
      (value "VIA.4-4")
      (footprint "eagle-import:4-4")
      (libsource (lib "eagle-import") (part "VIA.4-4"))
    )
    (comp (ref "U$488")
      (value "VIA.4-4")
      (footprint "eagle-import:4-4")
      (libsource (lib "eagle-import") (part "VIA.4-4"))
    )
    (comp (ref "U$489")
      (value "VIA.4-4")
      (footprint "eagle-import:4-4")
      (libsource (lib "eagle-import") (part "VIA.4-4"))
    )
    (comp (ref "U$490")
      (value "VIA.4-4")
      (footprint "eagle-import:4-4")
      (libsource (lib "eagle-import") (part "VIA.4-4"))
    )
    (comp (ref "U$491")
      (value "VIA.4-4")
      (footprint "eagle-import:4-4")
      (libsource (lib "eagle-import") (part "VIA.4-4"))
    )
    (comp (ref "U$492")
      (value "VIA.4-4")
      (footprint "eagle-import:4-4")
      (libsource (lib "eagle-import") (part "VIA.4-4"))
    )
    (comp (ref "U$493")
      (value "VIA.4-4")
      (footprint "eagle-import:4-4")
      (libsource (lib "eagle-import") (part "VIA.4-4"))
    )
    (comp (ref "U$494")
      (value "VIA.4-4")
      (footprint "eagle-import:4-4")
      (libsource (lib "eagle-import") (part "VIA.4-4"))
    )
    (comp (ref "U$495")
      (value "VIA.4-4")
      (footprint "eagle-import:4-4")
      (libsource (lib "eagle-import") (part "VIA.4-4"))
    )
    (comp (ref "U$496")
      (value "VIA.4-4")
      (footprint "eagle-import:4-4")
      (libsource (lib "eagle-import") (part "VIA.4-4"))
    )
    (comp (ref "U$497")
      (value "VIA.4-4")
      (footprint "eagle-import:4-4")
      (libsource (lib "eagle-import") (part "VIA.4-4"))
    )
    (comp (ref "U$498")
      (value "VIA.4-4")
      (footprint "eagle-import:4-4")
      (libsource (lib "eagle-import") (part "VIA.4-4"))
    )
    (comp (ref "U$499")
      (value "VIA.4-4")
      (footprint "eagle-import:4-4")
      (libsource (lib "eagle-import") (part "VIA.4-4"))
    )
    (comp (ref "U$500")
      (value "VIA.4-4")
      (footprint "eagle-import:4-4")
      (libsource (lib "eagle-import") (part "VIA.4-4"))
    )
    (comp (ref "U$501")
      (value "VIA.3-3")
      (footprint "eagle-import:3-3")
      (libsource (lib "eagle-import") (part "VIA.3-3"))
    )
    (comp (ref "U$502")
      (value "VIA.3-3")
      (footprint "eagle-import:3-3")
      (libsource (lib "eagle-import") (part "VIA.3-3"))
    )
    (comp (ref "U$503")
      (value "VIA.4-4")
      (footprint "eagle-import:4-4")
      (libsource (lib "eagle-import") (part "VIA.4-4"))
    )
    (comp (ref "U$504")
      (value "VIA.4-4")
      (footprint "eagle-import:4-4")
      (libsource (lib "eagle-import") (part "VIA.4-4"))
    )
    (comp (ref "U$505")
      (value "VIA.4-4")
      (footprint "eagle-import:4-4")
      (libsource (lib "eagle-import") (part "VIA.4-4"))
    )
    (comp (ref "U$506")
      (value "VIA.4-4")
      (footprint "eagle-import:4-4")
      (libsource (lib "eagle-import") (part "VIA.4-4"))
    )
    (comp (ref "U$507")
      (value "VIA.4-4")
      (footprint "eagle-import:4-4")
      (libsource (lib "eagle-import") (part "VIA.4-4"))
    )
    (comp (ref "U$508")
      (value "VIA.4-4")
      (footprint "eagle-import:4-4")
      (libsource (lib "eagle-import") (part "VIA.4-4"))
    )
    (comp (ref "U$509")
      (value "VIA.4-4")
      (footprint "eagle-import:4-4")
      (libsource (lib "eagle-import") (part "VIA.4-4"))
    )
    (comp (ref "U$510")
      (value "VIA.4-4")
      (footprint "eagle-import:4-4")
      (libsource (lib "eagle-import") (part "VIA.4-4"))
    )
    (comp (ref "U$511")
      (value "VIA.4-4")
      (footprint "eagle-import:4-4")
      (libsource (lib "eagle-import") (part "VIA.4-4"))
    )
    (comp (ref "U$512")
      (value "VIA.4-4")
      (footprint "eagle-import:4-4")
      (libsource (lib "eagle-import") (part "VIA.4-4"))
    )
    (comp (ref "U$513")
      (value "VIA.4-4")
      (footprint "eagle-import:4-4")
      (libsource (lib "eagle-import") (part "VIA.4-4"))
    )
    (comp (ref "U$514")
      (value "VIA.4-4")
      (footprint "eagle-import:4-4")
      (libsource (lib "eagle-import") (part "VIA.4-4"))
    )
    (comp (ref "U$515")
      (value "VIA.4-4")
      (footprint "eagle-import:4-4")
      (libsource (lib "eagle-import") (part "VIA.4-4"))
    )
    (comp (ref "U$516")
      (value "VIA.4-4")
      (footprint "eagle-import:4-4")
      (libsource (lib "eagle-import") (part "VIA.4-4"))
    )
    (comp (ref "U$517")
      (value "VIA.4-4")
      (footprint "eagle-import:4-4")
      (libsource (lib "eagle-import") (part "VIA.4-4"))
    )
    (comp (ref "U$518")
      (value "VIA.4-4")
      (footprint "eagle-import:4-4")
      (libsource (lib "eagle-import") (part "VIA.4-4"))
    )
    (comp (ref "U$519")
      (value "VIA.4-4")
      (footprint "eagle-import:4-4")
      (libsource (lib "eagle-import") (part "VIA.4-4"))
    )
    (comp (ref "U$520")
      (value "VIA.4-4")
      (footprint "eagle-import:4-4")
      (libsource (lib "eagle-import") (part "VIA.4-4"))
    )
    (comp (ref "U$521")
      (value "VIA.4-4")
      (footprint "eagle-import:4-4")
      (libsource (lib "eagle-import") (part "VIA.4-4"))
    )
    (comp (ref "U$522")
      (value "VIA.4-4")
      (footprint "eagle-import:4-4")
      (libsource (lib "eagle-import") (part "VIA.4-4"))
    )
    (comp (ref "U$523")
      (value "VIA.4-4")
      (footprint "eagle-import:4-4")
      (libsource (lib "eagle-import") (part "VIA.4-4"))
    )
    (comp (ref "U$524")
      (value "VIA.4-4")
      (footprint "eagle-import:4-4")
      (libsource (lib "eagle-import") (part "VIA.4-4"))
    )
    (comp (ref "U$525")
      (value "VIA.4-4")
      (footprint "eagle-import:4-4")
      (libsource (lib "eagle-import") (part "VIA.4-4"))
    )
    (comp (ref "U$526")
      (value "VIA.4-4")
      (footprint "eagle-import:4-4")
      (libsource (lib "eagle-import") (part "VIA.4-4"))
    )
    (comp (ref "U$527")
      (value "VIA.4-4")
      (footprint "eagle-import:4-4")
      (libsource (lib "eagle-import") (part "VIA.4-4"))
    )
    (comp (ref "U$528")
      (value "VIA.4-4")
      (footprint "eagle-import:4-4")
      (libsource (lib "eagle-import") (part "VIA.4-4"))
    )
    (comp (ref "U$529")
      (value "VIA.4-4")
      (footprint "eagle-import:4-4")
      (libsource (lib "eagle-import") (part "VIA.4-4"))
    )
    (comp (ref "U$530")
      (value "VIA.3-3")
      (footprint "eagle-import:3-3")
      (libsource (lib "eagle-import") (part "VIA.3-3"))
    )
    (comp (ref "U$531")
      (value "VIA.3-3")
      (footprint "eagle-import:3-3")
      (libsource (lib "eagle-import") (part "VIA.3-3"))
    )
    (comp (ref "U$532")
      (value "VIA.4-4")
      (footprint "eagle-import:4-4")
      (libsource (lib "eagle-import") (part "VIA.4-4"))
    )
    (comp (ref "U$533")
      (value "VIA.4-4")
      (footprint "eagle-import:4-4")
      (libsource (lib "eagle-import") (part "VIA.4-4"))
    )
    (comp (ref "U$534")
      (value "VIA.4-4")
      (footprint "eagle-import:4-4")
      (libsource (lib "eagle-import") (part "VIA.4-4"))
    )
    (comp (ref "U$535")
      (value "VIA.4-4")
      (footprint "eagle-import:4-4")
      (libsource (lib "eagle-import") (part "VIA.4-4"))
    )
    (comp (ref "U$536")
      (value "VIA.4-4")
      (footprint "eagle-import:4-4")
      (libsource (lib "eagle-import") (part "VIA.4-4"))
    )
    (comp (ref "U$537")
      (value "VIA.4-4")
      (footprint "eagle-import:4-4")
      (libsource (lib "eagle-import") (part "VIA.4-4"))
    )
    (comp (ref "U$538")
      (value "VIA.4-4")
      (footprint "eagle-import:4-4")
      (libsource (lib "eagle-import") (part "VIA.4-4"))
    )
    (comp (ref "U$539")
      (value "VIA.4-4")
      (footprint "eagle-import:4-4")
      (libsource (lib "eagle-import") (part "VIA.4-4"))
    )
    (comp (ref "U$540")
      (value "VIA.4-4")
      (footprint "eagle-import:4-4")
      (libsource (lib "eagle-import") (part "VIA.4-4"))
    )
    (comp (ref "U$541")
      (value "VIA.4-4")
      (footprint "eagle-import:4-4")
      (libsource (lib "eagle-import") (part "VIA.4-4"))
    )
    (comp (ref "U$542")
      (value "VIA.4-4")
      (footprint "eagle-import:4-4")
      (libsource (lib "eagle-import") (part "VIA.4-4"))
    )
    (comp (ref "U$543")
      (value "VIA.4-4")
      (footprint "eagle-import:4-4")
      (libsource (lib "eagle-import") (part "VIA.4-4"))
    )
    (comp (ref "U$544")
      (value "VIA.4-4")
      (footprint "eagle-import:4-4")
      (libsource (lib "eagle-import") (part "VIA.4-4"))
    )
    (comp (ref "U$545")
      (value "VIA.4-4")
      (footprint "eagle-import:4-4")
      (libsource (lib "eagle-import") (part "VIA.4-4"))
    )
    (comp (ref "U$546")
      (value "VIA.4-4")
      (footprint "eagle-import:4-4")
      (libsource (lib "eagle-import") (part "VIA.4-4"))
    )
    (comp (ref "U$547")
      (value "VIA.4-4")
      (footprint "eagle-import:4-4")
      (libsource (lib "eagle-import") (part "VIA.4-4"))
    )
    (comp (ref "U$548")
      (value "VIA.4-4")
      (footprint "eagle-import:4-4")
      (libsource (lib "eagle-import") (part "VIA.4-4"))
    )
    (comp (ref "U$549")
      (value "VIA.4-4")
      (footprint "eagle-import:4-4")
      (libsource (lib "eagle-import") (part "VIA.4-4"))
    )
    (comp (ref "U$550")
      (value "VIA.4-4")
      (footprint "eagle-import:4-4")
      (libsource (lib "eagle-import") (part "VIA.4-4"))
    )
    (comp (ref "U$551")
      (value "VIA.4-4")
      (footprint "eagle-import:4-4")
      (libsource (lib "eagle-import") (part "VIA.4-4"))
    )
    (comp (ref "U$552")
      (value "VIA.4-4")
      (footprint "eagle-import:4-4")
      (libsource (lib "eagle-import") (part "VIA.4-4"))
    )
    (comp (ref "U$553")
      (value "VIA.4-4")
      (footprint "eagle-import:4-4")
      (libsource (lib "eagle-import") (part "VIA.4-4"))
    )
    (comp (ref "U$554")
      (value "VIA.4-4")
      (footprint "eagle-import:4-4")
      (libsource (lib "eagle-import") (part "VIA.4-4"))
    )
    (comp (ref "U$555")
      (value "VIA.4-4")
      (footprint "eagle-import:4-4")
      (libsource (lib "eagle-import") (part "VIA.4-4"))
    )
    (comp (ref "U$556")
      (value "VIA.4-4")
      (footprint "eagle-import:4-4")
      (libsource (lib "eagle-import") (part "VIA.4-4"))
    )
    (comp (ref "U$557")
      (value "VIA.4-4")
      (footprint "eagle-import:4-4")
      (libsource (lib "eagle-import") (part "VIA.4-4"))
    )
    (comp (ref "U$558")
      (value "VIA.4-4")
      (footprint "eagle-import:4-4")
      (libsource (lib "eagle-import") (part "VIA.4-4"))
    )
    (comp (ref "U$559")
      (value "VIA.3-3")
      (footprint "eagle-import:3-3")
      (libsource (lib "eagle-import") (part "VIA.3-3"))
    )
    (comp (ref "U$560")
      (value "VIA.3-3")
      (footprint "eagle-import:3-3")
      (libsource (lib "eagle-import") (part "VIA.3-3"))
    )
    (comp (ref "U$561")
      (value "VIA.4-4")
      (footprint "eagle-import:4-4")
      (libsource (lib "eagle-import") (part "VIA.4-4"))
    )
    (comp (ref "U$562")
      (value "VIA.4-4")
      (footprint "eagle-import:4-4")
      (libsource (lib "eagle-import") (part "VIA.4-4"))
    )
    (comp (ref "U$563")
      (value "VIA.4-4")
      (footprint "eagle-import:4-4")
      (libsource (lib "eagle-import") (part "VIA.4-4"))
    )
    (comp (ref "U$564")
      (value "VIA.4-4")
      (footprint "eagle-import:4-4")
      (libsource (lib "eagle-import") (part "VIA.4-4"))
    )
    (comp (ref "U$565")
      (value "VIA.4-4")
      (footprint "eagle-import:4-4")
      (libsource (lib "eagle-import") (part "VIA.4-4"))
    )
    (comp (ref "U$566")
      (value "VIA.3-3")
      (footprint "eagle-import:3-3")
      (libsource (lib "eagle-import") (part "VIA.3-3"))
    )
    (comp (ref "U$567")
      (value "VIA.3-3")
      (footprint "eagle-import:3-3")
      (libsource (lib "eagle-import") (part "VIA.3-3"))
    )
    (comp (ref "U$568")
      (value "VIA.3-3")
      (footprint "eagle-import:3-3")
      (libsource (lib "eagle-import") (part "VIA.3-3"))
    )
    (comp (ref "U$569")
      (value "VIA.3-3")
      (footprint "eagle-import:3-3")
      (libsource (lib "eagle-import") (part "VIA.3-3"))
    )
    (comp (ref "U$570")
      (value "VIA.2-2.CORNER")
      (footprint "eagle-import:2-2.CORNER")
      (libsource (lib "eagle-import") (part "VIA.2-2.CORNER"))
    )
    (comp (ref "U$571")
      (value "VIA.3-3")
      (footprint "eagle-import:3-3")
      (libsource (lib "eagle-import") (part "VIA.3-3"))
    )
    (comp (ref "U$572")
      (value "VIA.3-3")
      (footprint "eagle-import:3-3")
      (libsource (lib "eagle-import") (part "VIA.3-3"))
    )
    (comp (ref "U$573")
      (value "VIA.3-3")
      (footprint "eagle-import:3-3")
      (libsource (lib "eagle-import") (part "VIA.3-3"))
    )
    (comp (ref "U$574")
      (value "VIA.2-2.CORNER")
      (footprint "eagle-import:2-2.CORNER")
      (libsource (lib "eagle-import") (part "VIA.2-2.CORNER"))
    )
    (comp (ref "U$575")
      (value "VIA.3-3")
      (footprint "eagle-import:3-3")
      (libsource (lib "eagle-import") (part "VIA.3-3"))
    )
    (comp (ref "U$585")
      (value "VIA.4-4")
      (footprint "eagle-import:4-4")
      (libsource (lib "eagle-import") (part "VIA.4-4"))
    )
    (comp (ref "U$586")
      (value "VIA.4-4")
      (footprint "eagle-import:4-4")
      (libsource (lib "eagle-import") (part "VIA.4-4"))
    )
    (comp (ref "U$587")
      (value "VIA.4-4")
      (footprint "eagle-import:4-4")
      (libsource (lib "eagle-import") (part "VIA.4-4"))
    )
    (comp (ref "U$588")
      (value "VIA.3-3")
      (footprint "eagle-import:3-3")
      (libsource (lib "eagle-import") (part "VIA.3-3"))
    )
  )
  (nets
    (net (code "1") (name "Net-(U$100-PadVIA)") (class "Default")
      (node (ref "U$100") (pin "VIA") (pinfunction "VIA_VIA") (pintype "bidirectional"))
      (node (ref "U$146") (pin "VIA") (pinfunction "VIA_VIA") (pintype "bidirectional"))
    )
    (net (code "2") (name "Net-(U$120-PadVIA)") (class "Default")
      (node (ref "U$120") (pin "VIA") (pinfunction "VIA_VIA") (pintype "bidirectional"))
      (node (ref "U$74") (pin "VIA") (pinfunction "VIA_VIA") (pintype "bidirectional"))
    )
    (net (code "3") (name "Net-(U$121-PadVIA)") (class "Default")
      (node (ref "U$121") (pin "VIA") (pinfunction "VIA_VIA") (pintype "bidirectional"))
      (node (ref "U$75") (pin "VIA") (pinfunction "VIA_VIA") (pintype "bidirectional"))
    )
    (net (code "4") (name "Net-(U$122-PadVIA)") (class "Default")
      (node (ref "U$122") (pin "VIA") (pinfunction "VIA_VIA") (pintype "bidirectional"))
      (node (ref "U$95") (pin "VIA") (pinfunction "VIA_VIA") (pintype "bidirectional"))
    )
    (net (code "5") (name "Net-(U$123-PadVIA)") (class "Default")
      (node (ref "U$123") (pin "VIA") (pinfunction "VIA_VIA") (pintype "bidirectional"))
      (node (ref "U$96") (pin "VIA") (pinfunction "VIA_VIA") (pintype "bidirectional"))
    )
    (net (code "6") (name "Net-(U$124-PadVIA)") (class "Default")
      (node (ref "U$124") (pin "VIA") (pinfunction "VIA_VIA") (pintype "bidirectional"))
      (node (ref "U$97") (pin "VIA") (pinfunction "VIA_VIA") (pintype "bidirectional"))
    )
    (net (code "7") (name "Net-(U$125-PadVIA)") (class "Default")
      (node (ref "U$125") (pin "VIA") (pinfunction "VIA_VIA") (pintype "bidirectional"))
      (node (ref "U$98") (pin "VIA") (pinfunction "VIA_VIA") (pintype "bidirectional"))
    )
    (net (code "8") (name "Net-(U$145-PadVIA)") (class "Default")
      (node (ref "U$145") (pin "VIA") (pinfunction "VIA_VIA") (pintype "bidirectional"))
      (node (ref "U$99") (pin "VIA") (pinfunction "VIA_VIA") (pintype "bidirectional"))
    )
    (net (code "9") (name "Net-(U$148-PadVIA)") (class "Default")
      (node (ref "U$148") (pin "VIA") (pinfunction "VIA_VIA") (pintype "bidirectional"))
      (node (ref "U$150") (pin "VIA") (pinfunction "VIA_VIA") (pintype "bidirectional"))
    )
    (net (code "10") (name "Net-(U$149-PadVIA)") (class "Default")
      (node (ref "U$149") (pin "VIA") (pinfunction "VIA_VIA") (pintype "bidirectional"))
      (node (ref "U$170") (pin "VIA") (pinfunction "VIA_VIA") (pintype "bidirectional"))
    )
    (net (code "11") (name "unconnected-(U$1-PadVIA)") (class "Default")
      (node (ref "U$1") (pin "VIA") (pinfunction "VIA_VIA") (pintype "bidirectional"))
    )
    (net (code "12") (name "unconnected-(U$2-PadVIA)") (class "Default")
      (node (ref "U$2") (pin "VIA") (pinfunction "VIA_VIA") (pintype "bidirectional"))
    )
    (net (code "13") (name "unconnected-(U$3-PadVIA)") (class "Default")
      (node (ref "U$3") (pin "VIA") (pinfunction "VIA_VIA") (pintype "bidirectional"))
    )
    (net (code "14") (name "unconnected-(U$4-PadVIA)") (class "Default")
      (node (ref "U$4") (pin "VIA") (pinfunction "VIA_VIA") (pintype "bidirectional"))
    )
    (net (code "15") (name "unconnected-(U$5-PadVIA)") (class "Default")
      (node (ref "U$5") (pin "VIA") (pinfunction "VIA_VIA") (pintype "bidirectional"))
    )
    (net (code "16") (name "unconnected-(U$6-PadVIA)") (class "Default")
      (node (ref "U$6") (pin "VIA") (pinfunction "VIA_VIA") (pintype "bidirectional"))
    )
    (net (code "17") (name "unconnected-(U$7-PadVIA)") (class "Default")
      (node (ref "U$7") (pin "VIA") (pinfunction "VIA_VIA") (pintype "bidirectional"))
    )
    (net (code "18") (name "unconnected-(U$8-PadVIA)") (class "Default")
      (node (ref "U$8") (pin "VIA") (pinfunction "VIA_VIA") (pintype "bidirectional"))
    )
    (net (code "19") (name "unconnected-(U$9-PadVIA)") (class "Default")
      (node (ref "U$9") (pin "VIA") (pinfunction "VIA_VIA") (pintype "bidirectional"))
    )
    (net (code "20") (name "unconnected-(U$10-PadVIA)") (class "Default")
      (node (ref "U$10") (pin "VIA") (pinfunction "VIA_VIA") (pintype "bidirectional"))
    )
    (net (code "21") (name "unconnected-(U$11-PadVIA)") (class "Default")
      (node (ref "U$11") (pin "VIA") (pinfunction "VIA_VIA") (pintype "bidirectional"))
    )
    (net (code "22") (name "unconnected-(U$12-PadVIA)") (class "Default")
      (node (ref "U$12") (pin "VIA") (pinfunction "VIA_VIA") (pintype "bidirectional"))
    )
    (net (code "23") (name "unconnected-(U$13-PadVIA)") (class "Default")
      (node (ref "U$13") (pin "VIA") (pinfunction "VIA_VIA") (pintype "bidirectional"))
    )
    (net (code "24") (name "unconnected-(U$14-PadVIA)") (class "Default")
      (node (ref "U$14") (pin "VIA") (pinfunction "VIA_VIA") (pintype "bidirectional"))
    )
    (net (code "25") (name "unconnected-(U$15-PadVIA)") (class "Default")
      (node (ref "U$15") (pin "VIA") (pinfunction "VIA_VIA") (pintype "bidirectional"))
    )
    (net (code "26") (name "unconnected-(U$16-PadVIA)") (class "Default")
      (node (ref "U$16") (pin "VIA") (pinfunction "VIA_VIA") (pintype "bidirectional"))
    )
    (net (code "27") (name "unconnected-(U$17-PadVIA)") (class "Default")
      (node (ref "U$17") (pin "VIA") (pinfunction "VIA_VIA") (pintype "bidirectional"))
    )
    (net (code "28") (name "unconnected-(U$18-PadVIA)") (class "Default")
      (node (ref "U$18") (pin "VIA") (pinfunction "VIA_VIA") (pintype "bidirectional"))
    )
    (net (code "29") (name "unconnected-(U$19-PadVIA)") (class "Default")
      (node (ref "U$19") (pin "VIA") (pinfunction "VIA_VIA") (pintype "bidirectional"))
    )
    (net (code "30") (name "unconnected-(U$20-PadVIA)") (class "Default")
      (node (ref "U$20") (pin "VIA") (pinfunction "VIA_VIA") (pintype "bidirectional"))
    )
    (net (code "31") (name "unconnected-(U$21-PadVIA)") (class "Default")
      (node (ref "U$21") (pin "VIA") (pinfunction "VIA_VIA") (pintype "bidirectional"))
    )
    (net (code "32") (name "unconnected-(U$22-PadVIA)") (class "Default")
      (node (ref "U$22") (pin "VIA") (pinfunction "VIA_VIA") (pintype "bidirectional"))
    )
    (net (code "33") (name "unconnected-(U$23-PadVIA)") (class "Default")
      (node (ref "U$23") (pin "VIA") (pinfunction "VIA_VIA") (pintype "bidirectional"))
    )
    (net (code "34") (name "unconnected-(U$24-PadVIA)") (class "Default")
      (node (ref "U$24") (pin "VIA") (pinfunction "VIA_VIA") (pintype "bidirectional"))
    )
    (net (code "35") (name "unconnected-(U$25-PadVIA)") (class "Default")
      (node (ref "U$25") (pin "VIA") (pinfunction "VIA_VIA") (pintype "bidirectional"))
    )
    (net (code "36") (name "unconnected-(U$26-PadVIA)") (class "Default")
      (node (ref "U$26") (pin "VIA") (pinfunction "VIA_VIA") (pintype "bidirectional"))
    )
    (net (code "37") (name "unconnected-(U$27-PadVIA)") (class "Default")
      (node (ref "U$27") (pin "VIA") (pinfunction "VIA_VIA") (pintype "bidirectional"))
    )
    (net (code "38") (name "unconnected-(U$28-PadVIA)") (class "Default")
      (node (ref "U$28") (pin "VIA") (pinfunction "VIA_VIA") (pintype "bidirectional"))
    )
    (net (code "39") (name "unconnected-(U$29-PadVIA)") (class "Default")
      (node (ref "U$29") (pin "VIA") (pinfunction "VIA_VIA") (pintype "bidirectional"))
    )
    (net (code "40") (name "unconnected-(U$30-PadVIA)") (class "Default")
      (node (ref "U$30") (pin "VIA") (pinfunction "VIA_VIA") (pintype "bidirectional"))
    )
    (net (code "41") (name "unconnected-(U$31-PadVIA)") (class "Default")
      (node (ref "U$31") (pin "VIA") (pinfunction "VIA_VIA") (pintype "bidirectional"))
    )
    (net (code "42") (name "unconnected-(U$32-PadVIA)") (class "Default")
      (node (ref "U$32") (pin "VIA") (pinfunction "VIA_VIA") (pintype "bidirectional"))
    )
    (net (code "43") (name "unconnected-(U$33-PadVIA)") (class "Default")
      (node (ref "U$33") (pin "VIA") (pinfunction "VIA_VIA") (pintype "bidirectional"))
    )
    (net (code "44") (name "unconnected-(U$34-PadVIA)") (class "Default")
      (node (ref "U$34") (pin "VIA") (pinfunction "VIA_VIA") (pintype "bidirectional"))
    )
    (net (code "45") (name "unconnected-(U$35-PadVIA)") (class "Default")
      (node (ref "U$35") (pin "VIA") (pinfunction "VIA_VIA") (pintype "bidirectional"))
    )
    (net (code "46") (name "unconnected-(U$36-PadVIA)") (class "Default")
      (node (ref "U$36") (pin "VIA") (pinfunction "VIA_VIA") (pintype "bidirectional"))
    )
    (net (code "47") (name "unconnected-(U$37-PadVIA)") (class "Default")
      (node (ref "U$37") (pin "VIA") (pinfunction "VIA_VIA") (pintype "bidirectional"))
    )
    (net (code "48") (name "unconnected-(U$38-PadVIA)") (class "Default")
      (node (ref "U$38") (pin "VIA") (pinfunction "VIA_VIA") (pintype "bidirectional"))
    )
    (net (code "49") (name "unconnected-(U$39-PadVIA)") (class "Default")
      (node (ref "U$39") (pin "VIA") (pinfunction "VIA_VIA") (pintype "bidirectional"))
    )
    (net (code "50") (name "unconnected-(U$40-PadVIA)") (class "Default")
      (node (ref "U$40") (pin "VIA") (pinfunction "VIA_VIA") (pintype "bidirectional"))
    )
    (net (code "51") (name "unconnected-(U$41-PadVIA)") (class "Default")
      (node (ref "U$41") (pin "VIA") (pinfunction "VIA_VIA") (pintype "bidirectional"))
    )
    (net (code "52") (name "unconnected-(U$42-PadVIA)") (class "Default")
      (node (ref "U$42") (pin "VIA") (pinfunction "VIA_VIA") (pintype "bidirectional"))
    )
    (net (code "53") (name "unconnected-(U$43-PadVIA)") (class "Default")
      (node (ref "U$43") (pin "VIA") (pinfunction "VIA_VIA") (pintype "bidirectional"))
    )
    (net (code "54") (name "unconnected-(U$44-PadVIA)") (class "Default")
      (node (ref "U$44") (pin "VIA") (pinfunction "VIA_VIA") (pintype "bidirectional"))
    )
    (net (code "55") (name "unconnected-(U$45-PadVIA)") (class "Default")
      (node (ref "U$45") (pin "VIA") (pinfunction "VIA_VIA") (pintype "bidirectional"))
    )
    (net (code "56") (name "unconnected-(U$46-PadVIA)") (class "Default")
      (node (ref "U$46") (pin "VIA") (pinfunction "VIA_VIA") (pintype "bidirectional"))
    )
    (net (code "57") (name "unconnected-(U$47-PadVIA)") (class "Default")
      (node (ref "U$47") (pin "VIA") (pinfunction "VIA_VIA") (pintype "bidirectional"))
    )
    (net (code "58") (name "unconnected-(U$48-PadVIA)") (class "Default")
      (node (ref "U$48") (pin "VIA") (pinfunction "VIA_VIA") (pintype "bidirectional"))
    )
    (net (code "59") (name "unconnected-(U$49-PadVIA)") (class "Default")
      (node (ref "U$49") (pin "VIA") (pinfunction "VIA_VIA") (pintype "bidirectional"))
    )
    (net (code "60") (name "unconnected-(U$50-PadVIA)") (class "Default")
      (node (ref "U$50") (pin "VIA") (pinfunction "VIA_VIA") (pintype "bidirectional"))
    )
    (net (code "61") (name "unconnected-(U$51-PadVIA)") (class "Default")
      (node (ref "U$51") (pin "VIA") (pinfunction "VIA_VIA") (pintype "bidirectional"))
    )
    (net (code "62") (name "unconnected-(U$52-PadVIA)") (class "Default")
      (node (ref "U$52") (pin "VIA") (pinfunction "VIA_VIA") (pintype "bidirectional"))
    )
    (net (code "63") (name "unconnected-(U$53-PadVIA)") (class "Default")
      (node (ref "U$53") (pin "VIA") (pinfunction "VIA_VIA") (pintype "bidirectional"))
    )
    (net (code "64") (name "unconnected-(U$54-PadVIA)") (class "Default")
      (node (ref "U$54") (pin "VIA") (pinfunction "VIA_VIA") (pintype "bidirectional"))
    )
    (net (code "65") (name "unconnected-(U$55-PadVIA)") (class "Default")
      (node (ref "U$55") (pin "VIA") (pinfunction "VIA_VIA") (pintype "bidirectional"))
    )
    (net (code "66") (name "unconnected-(U$56-PadVIA)") (class "Default")
      (node (ref "U$56") (pin "VIA") (pinfunction "VIA_VIA") (pintype "bidirectional"))
    )
    (net (code "67") (name "unconnected-(U$57-PadVIA)") (class "Default")
      (node (ref "U$57") (pin "VIA") (pinfunction "VIA_VIA") (pintype "bidirectional"))
    )
    (net (code "68") (name "unconnected-(U$58-PadVIA)") (class "Default")
      (node (ref "U$58") (pin "VIA") (pinfunction "VIA_VIA") (pintype "bidirectional"))
    )
    (net (code "69") (name "unconnected-(U$59-PadVIA)") (class "Default")
      (node (ref "U$59") (pin "VIA") (pinfunction "VIA_VIA") (pintype "bidirectional"))
    )
    (net (code "70") (name "unconnected-(U$60-PadVIA)") (class "Default")
      (node (ref "U$60") (pin "VIA") (pinfunction "VIA_VIA") (pintype "bidirectional"))
    )
    (net (code "71") (name "unconnected-(U$61-PadVIA)") (class "Default")
      (node (ref "U$61") (pin "VIA") (pinfunction "VIA_VIA") (pintype "bidirectional"))
    )
    (net (code "72") (name "unconnected-(U$62-PadVIA)") (class "Default")
      (node (ref "U$62") (pin "VIA") (pinfunction "VIA_VIA") (pintype "bidirectional"))
    )
    (net (code "73") (name "unconnected-(U$63-PadVIA)") (class "Default")
      (node (ref "U$63") (pin "VIA") (pinfunction "VIA_VIA") (pintype "bidirectional"))
    )
    (net (code "74") (name "unconnected-(U$64-PadVIA)") (class "Default")
      (node (ref "U$64") (pin "VIA") (pinfunction "VIA_VIA") (pintype "bidirectional"))
    )
    (net (code "75") (name "unconnected-(U$65-PadVIA)") (class "Default")
      (node (ref "U$65") (pin "VIA") (pinfunction "VIA_VIA") (pintype "bidirectional"))
    )
    (net (code "76") (name "unconnected-(U$66-PadVIA)") (class "Default")
      (node (ref "U$66") (pin "VIA") (pinfunction "VIA_VIA") (pintype "bidirectional"))
    )
    (net (code "77") (name "unconnected-(U$67-PadVIA)") (class "Default")
      (node (ref "U$67") (pin "VIA") (pinfunction "VIA_VIA") (pintype "bidirectional"))
    )
    (net (code "78") (name "unconnected-(U$68-PadVIA)") (class "Default")
      (node (ref "U$68") (pin "VIA") (pinfunction "VIA_VIA") (pintype "bidirectional"))
    )
    (net (code "79") (name "unconnected-(U$69-PadVIA)") (class "Default")
      (node (ref "U$69") (pin "VIA") (pinfunction "VIA_VIA") (pintype "bidirectional"))
    )
    (net (code "80") (name "unconnected-(U$70-PadVIA)") (class "Default")
      (node (ref "U$70") (pin "VIA") (pinfunction "VIA_VIA") (pintype "bidirectional"))
    )
    (net (code "81") (name "unconnected-(U$71-PadVIA)") (class "Default")
      (node (ref "U$71") (pin "VIA") (pinfunction "VIA_VIA") (pintype "bidirectional"))
    )
    (net (code "82") (name "unconnected-(U$72-PadVIA)") (class "Default")
      (node (ref "U$72") (pin "VIA") (pinfunction "VIA_VIA") (pintype "bidirectional"))
    )
    (net (code "83") (name "unconnected-(U$73-PadVIA)") (class "Default")
      (node (ref "U$73") (pin "VIA") (pinfunction "VIA_VIA") (pintype "bidirectional"))
    )
    (net (code "84") (name "unconnected-(U$76-PadVIA)") (class "Default")
      (node (ref "U$76") (pin "VIA") (pinfunction "VIA_VIA") (pintype "bidirectional"))
    )
    (net (code "85") (name "unconnected-(U$77-PadVIA)") (class "Default")
      (node (ref "U$77") (pin "VIA") (pinfunction "VIA_VIA") (pintype "bidirectional"))
    )
    (net (code "86") (name "unconnected-(U$78-PadVIA)") (class "Default")
      (node (ref "U$78") (pin "VIA") (pinfunction "VIA_VIA") (pintype "bidirectional"))
    )
    (net (code "87") (name "unconnected-(U$79-PadVIA)") (class "Default")
      (node (ref "U$79") (pin "VIA") (pinfunction "VIA_VIA") (pintype "bidirectional"))
    )
    (net (code "88") (name "unconnected-(U$80-PadVIA)") (class "Default")
      (node (ref "U$80") (pin "VIA") (pinfunction "VIA_VIA") (pintype "bidirectional"))
    )
    (net (code "89") (name "unconnected-(U$81-PadVIA)") (class "Default")
      (node (ref "U$81") (pin "VIA") (pinfunction "VIA_VIA") (pintype "bidirectional"))
    )
    (net (code "90") (name "unconnected-(U$82-PadVIA)") (class "Default")
      (node (ref "U$82") (pin "VIA") (pinfunction "VIA_VIA") (pintype "bidirectional"))
    )
    (net (code "91") (name "unconnected-(U$83-PadVIA)") (class "Default")
      (node (ref "U$83") (pin "VIA") (pinfunction "VIA_VIA") (pintype "bidirectional"))
    )
    (net (code "92") (name "unconnected-(U$84-PadVIA)") (class "Default")
      (node (ref "U$84") (pin "VIA") (pinfunction "VIA_VIA") (pintype "bidirectional"))
    )
    (net (code "93") (name "unconnected-(U$85-PadVIA)") (class "Default")
      (node (ref "U$85") (pin "VIA") (pinfunction "VIA_VIA") (pintype "bidirectional"))
    )
    (net (code "94") (name "unconnected-(U$86-PadVIA)") (class "Default")
      (node (ref "U$86") (pin "VIA") (pinfunction "VIA_VIA") (pintype "bidirectional"))
    )
    (net (code "95") (name "unconnected-(U$87-PadVIA)") (class "Default")
      (node (ref "U$87") (pin "VIA") (pinfunction "VIA_VIA") (pintype "bidirectional"))
    )
    (net (code "96") (name "unconnected-(U$88-PadVIA)") (class "Default")
      (node (ref "U$88") (pin "VIA") (pinfunction "VIA_VIA") (pintype "bidirectional"))
    )
    (net (code "97") (name "unconnected-(U$89-PadVIA)") (class "Default")
      (node (ref "U$89") (pin "VIA") (pinfunction "VIA_VIA") (pintype "bidirectional"))
    )
    (net (code "98") (name "unconnected-(U$90-PadVIA)") (class "Default")
      (node (ref "U$90") (pin "VIA") (pinfunction "VIA_VIA") (pintype "bidirectional"))
    )
    (net (code "99") (name "unconnected-(U$91-PadVIA)") (class "Default")
      (node (ref "U$91") (pin "VIA") (pinfunction "VIA_VIA") (pintype "bidirectional"))
    )
    (net (code "100") (name "unconnected-(U$92-PadVIA)") (class "Default")
      (node (ref "U$92") (pin "VIA") (pinfunction "VIA_VIA") (pintype "bidirectional"))
    )
    (net (code "101") (name "unconnected-(U$93-PadVIA)") (class "Default")
      (node (ref "U$93") (pin "VIA") (pinfunction "VIA_VIA") (pintype "bidirectional"))
    )
    (net (code "102") (name "unconnected-(U$94-PadVIA)") (class "Default")
      (node (ref "U$94") (pin "VIA") (pinfunction "VIA_VIA") (pintype "bidirectional"))
    )
    (net (code "103") (name "unconnected-(U$101-PadVIA)") (class "Default")
      (node (ref "U$101") (pin "VIA") (pinfunction "VIA_VIA") (pintype "bidirectional"))
    )
    (net (code "104") (name "unconnected-(U$102-PadVIA)") (class "Default")
      (node (ref "U$102") (pin "VIA") (pinfunction "VIA_VIA") (pintype "bidirectional"))
    )
    (net (code "105") (name "unconnected-(U$103-PadVIA)") (class "Default")
      (node (ref "U$103") (pin "VIA") (pinfunction "VIA_VIA") (pintype "bidirectional"))
    )
    (net (code "106") (name "unconnected-(U$104-PadVIA)") (class "Default")
      (node (ref "U$104") (pin "VIA") (pinfunction "VIA_VIA") (pintype "bidirectional"))
    )
    (net (code "107") (name "unconnected-(U$105-PadVIA)") (class "Default")
      (node (ref "U$105") (pin "VIA") (pinfunction "VIA_VIA") (pintype "bidirectional"))
    )
    (net (code "108") (name "unconnected-(U$106-PadVIA)") (class "Default")
      (node (ref "U$106") (pin "VIA") (pinfunction "VIA_VIA") (pintype "bidirectional"))
    )
    (net (code "109") (name "unconnected-(U$107-PadVIA)") (class "Default")
      (node (ref "U$107") (pin "VIA") (pinfunction "VIA_VIA") (pintype "bidirectional"))
    )
    (net (code "110") (name "unconnected-(U$108-PadVIA)") (class "Default")
      (node (ref "U$108") (pin "VIA") (pinfunction "VIA_VIA") (pintype "bidirectional"))
    )
    (net (code "111") (name "unconnected-(U$109-PadVIA)") (class "Default")
      (node (ref "U$109") (pin "VIA") (pinfunction "VIA_VIA") (pintype "bidirectional"))
    )
    (net (code "112") (name "unconnected-(U$110-PadVIA)") (class "Default")
      (node (ref "U$110") (pin "VIA") (pinfunction "VIA_VIA") (pintype "bidirectional"))
    )
    (net (code "113") (name "unconnected-(U$111-PadVIA)") (class "Default")
      (node (ref "U$111") (pin "VIA") (pinfunction "VIA_VIA") (pintype "bidirectional"))
    )
    (net (code "114") (name "unconnected-(U$112-PadVIA)") (class "Default")
      (node (ref "U$112") (pin "VIA") (pinfunction "VIA_VIA") (pintype "bidirectional"))
    )
    (net (code "115") (name "unconnected-(U$113-PadVIA)") (class "Default")
      (node (ref "U$113") (pin "VIA") (pinfunction "VIA_VIA") (pintype "bidirectional"))
    )
    (net (code "116") (name "unconnected-(U$114-PadVIA)") (class "Default")
      (node (ref "U$114") (pin "VIA") (pinfunction "VIA_VIA") (pintype "bidirectional"))
    )
    (net (code "117") (name "unconnected-(U$115-PadVIA)") (class "Default")
      (node (ref "U$115") (pin "VIA") (pinfunction "VIA_VIA") (pintype "bidirectional"))
    )
    (net (code "118") (name "unconnected-(U$116-PadVIA)") (class "Default")
      (node (ref "U$116") (pin "VIA") (pinfunction "VIA_VIA") (pintype "bidirectional"))
    )
    (net (code "119") (name "unconnected-(U$117-PadVIA)") (class "Default")
      (node (ref "U$117") (pin "VIA") (pinfunction "VIA_VIA") (pintype "bidirectional"))
    )
    (net (code "120") (name "unconnected-(U$118-PadVIA)") (class "Default")
      (node (ref "U$118") (pin "VIA") (pinfunction "VIA_VIA") (pintype "bidirectional"))
    )
    (net (code "121") (name "unconnected-(U$119-PadVIA)") (class "Default")
      (node (ref "U$119") (pin "VIA") (pinfunction "VIA_VIA") (pintype "bidirectional"))
    )
    (net (code "122") (name "unconnected-(U$126-PadVIA)") (class "Default")
      (node (ref "U$126") (pin "VIA") (pinfunction "VIA_VIA") (pintype "bidirectional"))
    )
    (net (code "123") (name "unconnected-(U$127-PadVIA)") (class "Default")
      (node (ref "U$127") (pin "VIA") (pinfunction "VIA_VIA") (pintype "bidirectional"))
    )
    (net (code "124") (name "unconnected-(U$128-PadVIA)") (class "Default")
      (node (ref "U$128") (pin "VIA") (pinfunction "VIA_VIA") (pintype "bidirectional"))
    )
    (net (code "125") (name "unconnected-(U$129-PadVIA)") (class "Default")
      (node (ref "U$129") (pin "VIA") (pinfunction "VIA_VIA") (pintype "bidirectional"))
    )
    (net (code "126") (name "unconnected-(U$130-PadVIA)") (class "Default")
      (node (ref "U$130") (pin "VIA") (pinfunction "VIA_VIA") (pintype "bidirectional"))
    )
    (net (code "127") (name "unconnected-(U$131-PadVIA)") (class "Default")
      (node (ref "U$131") (pin "VIA") (pinfunction "VIA_VIA") (pintype "bidirectional"))
    )
    (net (code "128") (name "unconnected-(U$132-PadVIA)") (class "Default")
      (node (ref "U$132") (pin "VIA") (pinfunction "VIA_VIA") (pintype "bidirectional"))
    )
    (net (code "129") (name "unconnected-(U$133-PadVIA)") (class "Default")
      (node (ref "U$133") (pin "VIA") (pinfunction "VIA_VIA") (pintype "bidirectional"))
    )
    (net (code "130") (name "unconnected-(U$134-PadVIA)") (class "Default")
      (node (ref "U$134") (pin "VIA") (pinfunction "VIA_VIA") (pintype "bidirectional"))
    )
    (net (code "131") (name "unconnected-(U$135-PadVIA)") (class "Default")
      (node (ref "U$135") (pin "VIA") (pinfunction "VIA_VIA") (pintype "bidirectional"))
    )
    (net (code "132") (name "unconnected-(U$136-PadVIA)") (class "Default")
      (node (ref "U$136") (pin "VIA") (pinfunction "VIA_VIA") (pintype "bidirectional"))
    )
    (net (code "133") (name "unconnected-(U$137-PadVIA)") (class "Default")
      (node (ref "U$137") (pin "VIA") (pinfunction "VIA_VIA") (pintype "bidirectional"))
    )
    (net (code "134") (name "unconnected-(U$138-PadVIA)") (class "Default")
      (node (ref "U$138") (pin "VIA") (pinfunction "VIA_VIA") (pintype "bidirectional"))
    )
    (net (code "135") (name "unconnected-(U$139-PadVIA)") (class "Default")
      (node (ref "U$139") (pin "VIA") (pinfunction "VIA_VIA") (pintype "bidirectional"))
    )
    (net (code "136") (name "unconnected-(U$140-PadVIA)") (class "Default")
      (node (ref "U$140") (pin "VIA") (pinfunction "VIA_VIA") (pintype "bidirectional"))
    )
    (net (code "137") (name "unconnected-(U$141-PadVIA)") (class "Default")
      (node (ref "U$141") (pin "VIA") (pinfunction "VIA_VIA") (pintype "bidirectional"))
    )
    (net (code "138") (name "unconnected-(U$142-PadVIA)") (class "Default")
      (node (ref "U$142") (pin "VIA") (pinfunction "VIA_VIA") (pintype "bidirectional"))
    )
    (net (code "139") (name "unconnected-(U$143-PadVIA)") (class "Default")
      (node (ref "U$143") (pin "VIA") (pinfunction "VIA_VIA") (pintype "bidirectional"))
    )
    (net (code "140") (name "unconnected-(U$144-PadVIA)") (class "Default")
      (node (ref "U$144") (pin "VIA") (pinfunction "VIA_VIA") (pintype "bidirectional"))
    )
    (net (code "141") (name "unconnected-(U$147-PadVIA)") (class "Default")
      (node (ref "U$147") (pin "VIA") (pinfunction "VIA_VIA") (pintype "bidirectional"))
    )
    (net (code "142") (name "unconnected-(U$151-PadVIA)") (class "Default")
      (node (ref "U$151") (pin "VIA") (pinfunction "VIA_VIA") (pintype "bidirectional"))
    )
    (net (code "143") (name "unconnected-(U$152-PadVIA)") (class "Default")
      (node (ref "U$152") (pin "VIA") (pinfunction "VIA_VIA") (pintype "bidirectional"))
    )
    (net (code "144") (name "unconnected-(U$153-PadVIA)") (class "Default")
      (node (ref "U$153") (pin "VIA") (pinfunction "VIA_VIA") (pintype "bidirectional"))
    )
    (net (code "145") (name "unconnected-(U$154-PadVIA)") (class "Default")
      (node (ref "U$154") (pin "VIA") (pinfunction "VIA_VIA") (pintype "bidirectional"))
    )
    (net (code "146") (name "unconnected-(U$155-PadVIA)") (class "Default")
      (node (ref "U$155") (pin "VIA") (pinfunction "VIA_VIA") (pintype "bidirectional"))
    )
    (net (code "147") (name "unconnected-(U$156-PadVIA)") (class "Default")
      (node (ref "U$156") (pin "VIA") (pinfunction "VIA_VIA") (pintype "bidirectional"))
    )
    (net (code "148") (name "unconnected-(U$157-PadVIA)") (class "Default")
      (node (ref "U$157") (pin "VIA") (pinfunction "VIA_VIA") (pintype "bidirectional"))
    )
    (net (code "149") (name "unconnected-(U$158-PadVIA)") (class "Default")
      (node (ref "U$158") (pin "VIA") (pinfunction "VIA_VIA") (pintype "bidirectional"))
    )
    (net (code "150") (name "unconnected-(U$159-PadVIA)") (class "Default")
      (node (ref "U$159") (pin "VIA") (pinfunction "VIA_VIA") (pintype "bidirectional"))
    )
    (net (code "151") (name "unconnected-(U$160-PadVIA)") (class "Default")
      (node (ref "U$160") (pin "VIA") (pinfunction "VIA_VIA") (pintype "bidirectional"))
    )
    (net (code "152") (name "unconnected-(U$161-PadVIA)") (class "Default")
      (node (ref "U$161") (pin "VIA") (pinfunction "VIA_VIA") (pintype "bidirectional"))
    )
    (net (code "153") (name "unconnected-(U$162-PadVIA)") (class "Default")
      (node (ref "U$162") (pin "VIA") (pinfunction "VIA_VIA") (pintype "bidirectional"))
    )
    (net (code "154") (name "unconnected-(U$163-PadVIA)") (class "Default")
      (node (ref "U$163") (pin "VIA") (pinfunction "VIA_VIA") (pintype "bidirectional"))
    )
    (net (code "155") (name "unconnected-(U$164-PadVIA)") (class "Default")
      (node (ref "U$164") (pin "VIA") (pinfunction "VIA_VIA") (pintype "bidirectional"))
    )
    (net (code "156") (name "unconnected-(U$165-PadVIA)") (class "Default")
      (node (ref "U$165") (pin "VIA") (pinfunction "VIA_VIA") (pintype "bidirectional"))
    )
    (net (code "157") (name "unconnected-(U$166-PadVIA)") (class "Default")
      (node (ref "U$166") (pin "VIA") (pinfunction "VIA_VIA") (pintype "bidirectional"))
    )
    (net (code "158") (name "unconnected-(U$167-PadVIA)") (class "Default")
      (node (ref "U$167") (pin "VIA") (pinfunction "VIA_VIA") (pintype "bidirectional"))
    )
    (net (code "159") (name "unconnected-(U$168-PadVIA)") (class "Default")
      (node (ref "U$168") (pin "VIA") (pinfunction "VIA_VIA") (pintype "bidirectional"))
    )
    (net (code "160") (name "unconnected-(U$169-PadVIA)") (class "Default")
      (node (ref "U$169") (pin "VIA") (pinfunction "VIA_VIA") (pintype "bidirectional"))
    )
    (net (code "161") (name "unconnected-(U$171-PadVIA)") (class "Default")
      (node (ref "U$171") (pin "VIA") (pinfunction "VIA_VIA") (pintype "bidirectional"))
    )
    (net (code "162") (name "unconnected-(U$172-PadVIA)") (class "Default")
      (node (ref "U$172") (pin "VIA") (pinfunction "VIA_VIA") (pintype "bidirectional"))
    )
    (net (code "163") (name "unconnected-(U$173-PadVIA)") (class "Default")
      (node (ref "U$173") (pin "VIA") (pinfunction "VIA_VIA") (pintype "bidirectional"))
    )
    (net (code "164") (name "unconnected-(U$174-PadVIA)") (class "Default")
      (node (ref "U$174") (pin "VIA") (pinfunction "VIA_VIA") (pintype "bidirectional"))
    )
    (net (code "165") (name "unconnected-(U$175-PadVIA)") (class "Default")
      (node (ref "U$175") (pin "VIA") (pinfunction "VIA_VIA") (pintype "bidirectional"))
    )
    (net (code "166") (name "unconnected-(U$176-PadVIA)") (class "Default")
      (node (ref "U$176") (pin "VIA") (pinfunction "VIA_VIA") (pintype "bidirectional"))
    )
    (net (code "167") (name "unconnected-(U$177-PadVIA)") (class "Default")
      (node (ref "U$177") (pin "VIA") (pinfunction "VIA_VIA") (pintype "bidirectional"))
    )
    (net (code "168") (name "unconnected-(U$178-PadVIA)") (class "Default")
      (node (ref "U$178") (pin "VIA") (pinfunction "VIA_VIA") (pintype "bidirectional"))
    )
    (net (code "169") (name "unconnected-(U$179-PadVIA)") (class "Default")
      (node (ref "U$179") (pin "VIA") (pinfunction "VIA_VIA") (pintype "bidirectional"))
    )
    (net (code "170") (name "unconnected-(U$180-PadVIA)") (class "Default")
      (node (ref "U$180") (pin "VIA") (pinfunction "VIA_VIA") (pintype "bidirectional"))
    )
    (net (code "171") (name "unconnected-(U$181-PadVIA)") (class "Default")
      (node (ref "U$181") (pin "VIA") (pinfunction "VIA_VIA") (pintype "bidirectional"))
    )
    (net (code "172") (name "unconnected-(U$182-PadVIA)") (class "Default")
      (node (ref "U$182") (pin "VIA") (pinfunction "VIA_VIA") (pintype "bidirectional"))
    )
    (net (code "173") (name "unconnected-(U$183-PadVIA)") (class "Default")
      (node (ref "U$183") (pin "VIA") (pinfunction "VIA_VIA") (pintype "bidirectional"))
    )
    (net (code "174") (name "unconnected-(U$184-PadVIA)") (class "Default")
      (node (ref "U$184") (pin "VIA") (pinfunction "VIA_VIA") (pintype "bidirectional"))
    )
    (net (code "175") (name "unconnected-(U$185-PadVIA)") (class "Default")
      (node (ref "U$185") (pin "VIA") (pinfunction "VIA_VIA") (pintype "bidirectional"))
    )
    (net (code "176") (name "unconnected-(U$186-PadVIA)") (class "Default")
      (node (ref "U$186") (pin "VIA") (pinfunction "VIA_VIA") (pintype "bidirectional"))
    )
    (net (code "177") (name "unconnected-(U$187-PadVIA)") (class "Default")
      (node (ref "U$187") (pin "VIA") (pinfunction "VIA_VIA") (pintype "bidirectional"))
    )
    (net (code "178") (name "unconnected-(U$188-PadVIA)") (class "Default")
      (node (ref "U$188") (pin "VIA") (pinfunction "VIA_VIA") (pintype "bidirectional"))
    )
    (net (code "179") (name "unconnected-(U$189-PadVIA)") (class "Default")
      (node (ref "U$189") (pin "VIA") (pinfunction "VIA_VIA") (pintype "bidirectional"))
    )
    (net (code "180") (name "unconnected-(U$190-PadVIA)") (class "Default")
      (node (ref "U$190") (pin "VIA") (pinfunction "VIA_VIA") (pintype "bidirectional"))
    )
    (net (code "181") (name "unconnected-(U$191-PadVIA)") (class "Default")
      (node (ref "U$191") (pin "VIA") (pinfunction "VIA_VIA") (pintype "bidirectional"))
    )
    (net (code "182") (name "unconnected-(U$192-PadVIA)") (class "Default")
      (node (ref "U$192") (pin "VIA") (pinfunction "VIA_VIA") (pintype "bidirectional"))
    )
    (net (code "183") (name "unconnected-(U$193-PadVIA)") (class "Default")
      (node (ref "U$193") (pin "VIA") (pinfunction "VIA_VIA") (pintype "bidirectional"))
    )
    (net (code "184") (name "unconnected-(U$194-PadVIA)") (class "Default")
      (node (ref "U$194") (pin "VIA") (pinfunction "VIA_VIA") (pintype "bidirectional"))
    )
    (net (code "185") (name "unconnected-(U$195-PadVIA)") (class "Default")
      (node (ref "U$195") (pin "VIA") (pinfunction "VIA_VIA") (pintype "bidirectional"))
    )
    (net (code "186") (name "unconnected-(U$196-PadVIA)") (class "Default")
      (node (ref "U$196") (pin "VIA") (pinfunction "VIA_VIA") (pintype "bidirectional"))
    )
    (net (code "187") (name "unconnected-(U$197-PadVIA)") (class "Default")
      (node (ref "U$197") (pin "VIA") (pinfunction "VIA_VIA") (pintype "bidirectional"))
    )
    (net (code "188") (name "unconnected-(U$198-PadVIA)") (class "Default")
      (node (ref "U$198") (pin "VIA") (pinfunction "VIA_VIA") (pintype "bidirectional"))
    )
    (net (code "189") (name "unconnected-(U$199-PadVIA)") (class "Default")
      (node (ref "U$199") (pin "VIA") (pinfunction "VIA_VIA") (pintype "bidirectional"))
    )
    (net (code "190") (name "unconnected-(U$200-PadVIA)") (class "Default")
      (node (ref "U$200") (pin "VIA") (pinfunction "VIA_VIA") (pintype "bidirectional"))
    )
    (net (code "191") (name "unconnected-(U$201-PadVIA)") (class "Default")
      (node (ref "U$201") (pin "VIA") (pinfunction "VIA_VIA") (pintype "bidirectional"))
    )
    (net (code "192") (name "unconnected-(U$202-PadVIA)") (class "Default")
      (node (ref "U$202") (pin "VIA") (pinfunction "VIA_VIA") (pintype "bidirectional"))
    )
    (net (code "193") (name "unconnected-(U$203-PadVIA)") (class "Default")
      (node (ref "U$203") (pin "VIA") (pinfunction "VIA_VIA") (pintype "bidirectional"))
    )
    (net (code "194") (name "unconnected-(U$204-PadVIA)") (class "Default")
      (node (ref "U$204") (pin "VIA") (pinfunction "VIA_VIA") (pintype "bidirectional"))
    )
    (net (code "195") (name "unconnected-(U$205-PadVIA)") (class "Default")
      (node (ref "U$205") (pin "VIA") (pinfunction "VIA_VIA") (pintype "bidirectional"))
    )
    (net (code "196") (name "unconnected-(U$206-PadVIA)") (class "Default")
      (node (ref "U$206") (pin "VIA") (pinfunction "VIA_VIA") (pintype "bidirectional"))
    )
    (net (code "197") (name "unconnected-(U$207-PadVIA)") (class "Default")
      (node (ref "U$207") (pin "VIA") (pinfunction "VIA_VIA") (pintype "bidirectional"))
    )
    (net (code "198") (name "unconnected-(U$208-PadVIA)") (class "Default")
      (node (ref "U$208") (pin "VIA") (pinfunction "VIA_VIA") (pintype "bidirectional"))
    )
    (net (code "199") (name "unconnected-(U$209-PadVIA)") (class "Default")
      (node (ref "U$209") (pin "VIA") (pinfunction "VIA_VIA") (pintype "bidirectional"))
    )
    (net (code "200") (name "unconnected-(U$210-PadVIA)") (class "Default")
      (node (ref "U$210") (pin "VIA") (pinfunction "VIA_VIA") (pintype "bidirectional"))
    )
    (net (code "201") (name "unconnected-(U$211-PadVIA)") (class "Default")
      (node (ref "U$211") (pin "VIA") (pinfunction "VIA_VIA") (pintype "bidirectional"))
    )
    (net (code "202") (name "unconnected-(U$212-PadVIA)") (class "Default")
      (node (ref "U$212") (pin "VIA") (pinfunction "VIA_VIA") (pintype "bidirectional"))
    )
    (net (code "203") (name "unconnected-(U$213-PadVIA)") (class "Default")
      (node (ref "U$213") (pin "VIA") (pinfunction "VIA_VIA") (pintype "bidirectional"))
    )
    (net (code "204") (name "unconnected-(U$214-PadVIA)") (class "Default")
      (node (ref "U$214") (pin "VIA") (pinfunction "VIA_VIA") (pintype "bidirectional"))
    )
    (net (code "205") (name "unconnected-(U$215-PadVIA)") (class "Default")
      (node (ref "U$215") (pin "VIA") (pinfunction "VIA_VIA") (pintype "bidirectional"))
    )
    (net (code "206") (name "unconnected-(U$216-PadVIA)") (class "Default")
      (node (ref "U$216") (pin "VIA") (pinfunction "VIA_VIA") (pintype "bidirectional"))
    )
    (net (code "207") (name "unconnected-(U$217-PadVIA)") (class "Default")
      (node (ref "U$217") (pin "VIA") (pinfunction "VIA_VIA") (pintype "bidirectional"))
    )
    (net (code "208") (name "unconnected-(U$218-PadVIA)") (class "Default")
      (node (ref "U$218") (pin "VIA") (pinfunction "VIA_VIA") (pintype "bidirectional"))
    )
    (net (code "209") (name "unconnected-(U$219-PadVIA)") (class "Default")
      (node (ref "U$219") (pin "VIA") (pinfunction "VIA_VIA") (pintype "bidirectional"))
    )
    (net (code "210") (name "unconnected-(U$220-PadVIA)") (class "Default")
      (node (ref "U$220") (pin "VIA") (pinfunction "VIA_VIA") (pintype "bidirectional"))
    )
    (net (code "211") (name "unconnected-(U$221-PadVIA)") (class "Default")
      (node (ref "U$221") (pin "VIA") (pinfunction "VIA_VIA") (pintype "bidirectional"))
    )
    (net (code "212") (name "unconnected-(U$222-PadVIA)") (class "Default")
      (node (ref "U$222") (pin "VIA") (pinfunction "VIA_VIA") (pintype "bidirectional"))
    )
    (net (code "213") (name "unconnected-(U$223-PadVIA)") (class "Default")
      (node (ref "U$223") (pin "VIA") (pinfunction "VIA_VIA") (pintype "bidirectional"))
    )
    (net (code "214") (name "unconnected-(U$224-PadVIA)") (class "Default")
      (node (ref "U$224") (pin "VIA") (pinfunction "VIA_VIA") (pintype "bidirectional"))
    )
    (net (code "215") (name "unconnected-(U$225-PadVIA)") (class "Default")
      (node (ref "U$225") (pin "VIA") (pinfunction "VIA_VIA") (pintype "bidirectional"))
    )
    (net (code "216") (name "unconnected-(U$226-PadVIA)") (class "Default")
      (node (ref "U$226") (pin "VIA") (pinfunction "VIA_VIA") (pintype "bidirectional"))
    )
    (net (code "217") (name "unconnected-(U$227-PadVIA)") (class "Default")
      (node (ref "U$227") (pin "VIA") (pinfunction "VIA_VIA") (pintype "bidirectional"))
    )
    (net (code "218") (name "unconnected-(U$228-PadVIA)") (class "Default")
      (node (ref "U$228") (pin "VIA") (pinfunction "VIA_VIA") (pintype "bidirectional"))
    )
    (net (code "219") (name "unconnected-(U$229-PadVIA)") (class "Default")
      (node (ref "U$229") (pin "VIA") (pinfunction "VIA_VIA") (pintype "bidirectional"))
    )
    (net (code "220") (name "unconnected-(U$230-PadVIA)") (class "Default")
      (node (ref "U$230") (pin "VIA") (pinfunction "VIA_VIA") (pintype "bidirectional"))
    )
    (net (code "221") (name "unconnected-(U$231-PadVIA)") (class "Default")
      (node (ref "U$231") (pin "VIA") (pinfunction "VIA_VIA") (pintype "bidirectional"))
    )
    (net (code "222") (name "unconnected-(U$232-PadVIA)") (class "Default")
      (node (ref "U$232") (pin "VIA") (pinfunction "VIA_VIA") (pintype "bidirectional"))
    )
    (net (code "223") (name "unconnected-(U$233-PadVIA)") (class "Default")
      (node (ref "U$233") (pin "VIA") (pinfunction "VIA_VIA") (pintype "bidirectional"))
    )
    (net (code "224") (name "unconnected-(U$234-PadVIA)") (class "Default")
      (node (ref "U$234") (pin "VIA") (pinfunction "VIA_VIA") (pintype "bidirectional"))
    )
    (net (code "225") (name "unconnected-(U$235-PadVIA)") (class "Default")
      (node (ref "U$235") (pin "VIA") (pinfunction "VIA_VIA") (pintype "bidirectional"))
    )
    (net (code "226") (name "unconnected-(U$236-PadVIA)") (class "Default")
      (node (ref "U$236") (pin "VIA") (pinfunction "VIA_VIA") (pintype "bidirectional"))
    )
    (net (code "227") (name "unconnected-(U$237-PadVIA)") (class "Default")
      (node (ref "U$237") (pin "VIA") (pinfunction "VIA_VIA") (pintype "bidirectional"))
    )
    (net (code "228") (name "unconnected-(U$238-PadVIA)") (class "Default")
      (node (ref "U$238") (pin "VIA") (pinfunction "VIA_VIA") (pintype "bidirectional"))
    )
    (net (code "229") (name "unconnected-(U$239-PadVIA)") (class "Default")
      (node (ref "U$239") (pin "VIA") (pinfunction "VIA_VIA") (pintype "bidirectional"))
    )
    (net (code "230") (name "unconnected-(U$240-PadVIA)") (class "Default")
      (node (ref "U$240") (pin "VIA") (pinfunction "VIA_VIA") (pintype "bidirectional"))
    )
    (net (code "231") (name "unconnected-(U$241-PadVIA)") (class "Default")
      (node (ref "U$241") (pin "VIA") (pinfunction "VIA_VIA") (pintype "bidirectional"))
    )
    (net (code "232") (name "unconnected-(U$242-PadVIA)") (class "Default")
      (node (ref "U$242") (pin "VIA") (pinfunction "VIA_VIA") (pintype "bidirectional"))
    )
    (net (code "233") (name "unconnected-(U$243-PadVIA)") (class "Default")
      (node (ref "U$243") (pin "VIA") (pinfunction "VIA_VIA") (pintype "bidirectional"))
    )
    (net (code "234") (name "unconnected-(U$244-PadVIA)") (class "Default")
      (node (ref "U$244") (pin "VIA") (pinfunction "VIA_VIA") (pintype "bidirectional"))
    )
    (net (code "235") (name "unconnected-(U$245-PadVIA)") (class "Default")
      (node (ref "U$245") (pin "VIA") (pinfunction "VIA_VIA") (pintype "bidirectional"))
    )
    (net (code "236") (name "unconnected-(U$246-PadVIA)") (class "Default")
      (node (ref "U$246") (pin "VIA") (pinfunction "VIA_VIA") (pintype "bidirectional"))
    )
    (net (code "237") (name "unconnected-(U$247-PadVIA)") (class "Default")
      (node (ref "U$247") (pin "VIA") (pinfunction "VIA_VIA") (pintype "bidirectional"))
    )
    (net (code "238") (name "unconnected-(U$248-PadVIA)") (class "Default")
      (node (ref "U$248") (pin "VIA") (pinfunction "VIA_VIA") (pintype "bidirectional"))
    )
    (net (code "239") (name "unconnected-(U$249-PadVIA)") (class "Default")
      (node (ref "U$249") (pin "VIA") (pinfunction "VIA_VIA") (pintype "bidirectional"))
    )
    (net (code "240") (name "unconnected-(U$250-PadVIA)") (class "Default")
      (node (ref "U$250") (pin "VIA") (pinfunction "VIA_VIA") (pintype "bidirectional"))
    )
    (net (code "241") (name "unconnected-(U$251-PadVIA)") (class "Default")
      (node (ref "U$251") (pin "VIA") (pinfunction "VIA_VIA") (pintype "bidirectional"))
    )
    (net (code "242") (name "unconnected-(U$252-PadVIA)") (class "Default")
      (node (ref "U$252") (pin "VIA") (pinfunction "VIA_VIA") (pintype "bidirectional"))
    )
    (net (code "243") (name "unconnected-(U$253-PadVIA)") (class "Default")
      (node (ref "U$253") (pin "VIA") (pinfunction "VIA_VIA") (pintype "bidirectional"))
    )
    (net (code "244") (name "unconnected-(U$254-PadVIA)") (class "Default")
      (node (ref "U$254") (pin "VIA") (pinfunction "VIA_VIA") (pintype "bidirectional"))
    )
    (net (code "245") (name "unconnected-(U$255-PadVIA)") (class "Default")
      (node (ref "U$255") (pin "VIA") (pinfunction "VIA_VIA") (pintype "bidirectional"))
    )
    (net (code "246") (name "unconnected-(U$256-PadVIA)") (class "Default")
      (node (ref "U$256") (pin "VIA") (pinfunction "VIA_VIA") (pintype "bidirectional"))
    )
    (net (code "247") (name "unconnected-(U$257-PadVIA)") (class "Default")
      (node (ref "U$257") (pin "VIA") (pinfunction "VIA_VIA") (pintype "bidirectional"))
    )
    (net (code "248") (name "unconnected-(U$258-PadVIA)") (class "Default")
      (node (ref "U$258") (pin "VIA") (pinfunction "VIA_VIA") (pintype "bidirectional"))
    )
    (net (code "249") (name "unconnected-(U$259-PadVIA)") (class "Default")
      (node (ref "U$259") (pin "VIA") (pinfunction "VIA_VIA") (pintype "bidirectional"))
    )
    (net (code "250") (name "unconnected-(U$260-PadVIA)") (class "Default")
      (node (ref "U$260") (pin "VIA") (pinfunction "VIA_VIA") (pintype "bidirectional"))
    )
    (net (code "251") (name "unconnected-(U$261-PadVIA)") (class "Default")
      (node (ref "U$261") (pin "VIA") (pinfunction "VIA_VIA") (pintype "bidirectional"))
    )
    (net (code "252") (name "unconnected-(U$262-PadVIA)") (class "Default")
      (node (ref "U$262") (pin "VIA") (pinfunction "VIA_VIA") (pintype "bidirectional"))
    )
    (net (code "253") (name "unconnected-(U$263-PadVIA)") (class "Default")
      (node (ref "U$263") (pin "VIA") (pinfunction "VIA_VIA") (pintype "bidirectional"))
    )
    (net (code "254") (name "unconnected-(U$264-PadVIA)") (class "Default")
      (node (ref "U$264") (pin "VIA") (pinfunction "VIA_VIA") (pintype "bidirectional"))
    )
    (net (code "255") (name "unconnected-(U$265-PadVIA)") (class "Default")
      (node (ref "U$265") (pin "VIA") (pinfunction "VIA_VIA") (pintype "bidirectional"))
    )
    (net (code "256") (name "unconnected-(U$266-PadVIA)") (class "Default")
      (node (ref "U$266") (pin "VIA") (pinfunction "VIA_VIA") (pintype "bidirectional"))
    )
    (net (code "257") (name "unconnected-(U$267-PadVIA)") (class "Default")
      (node (ref "U$267") (pin "VIA") (pinfunction "VIA_VIA") (pintype "bidirectional"))
    )
    (net (code "258") (name "unconnected-(U$268-PadVIA)") (class "Default")
      (node (ref "U$268") (pin "VIA") (pinfunction "VIA_VIA") (pintype "bidirectional"))
    )
    (net (code "259") (name "unconnected-(U$269-PadVIA)") (class "Default")
      (node (ref "U$269") (pin "VIA") (pinfunction "VIA_VIA") (pintype "bidirectional"))
    )
    (net (code "260") (name "unconnected-(U$270-PadVIA)") (class "Default")
      (node (ref "U$270") (pin "VIA") (pinfunction "VIA_VIA") (pintype "bidirectional"))
    )
    (net (code "261") (name "unconnected-(U$271-PadVIA)") (class "Default")
      (node (ref "U$271") (pin "VIA") (pinfunction "VIA_VIA") (pintype "bidirectional"))
    )
    (net (code "262") (name "unconnected-(U$272-PadVIA)") (class "Default")
      (node (ref "U$272") (pin "VIA") (pinfunction "VIA_VIA") (pintype "bidirectional"))
    )
    (net (code "263") (name "unconnected-(U$273-PadVIA)") (class "Default")
      (node (ref "U$273") (pin "VIA") (pinfunction "VIA_VIA") (pintype "bidirectional"))
    )
    (net (code "264") (name "unconnected-(U$274-PadVIA)") (class "Default")
      (node (ref "U$274") (pin "VIA") (pinfunction "VIA_VIA") (pintype "bidirectional"))
    )
    (net (code "265") (name "unconnected-(U$275-PadVIA)") (class "Default")
      (node (ref "U$275") (pin "VIA") (pinfunction "VIA_VIA") (pintype "bidirectional"))
    )
    (net (code "266") (name "unconnected-(U$276-PadVIA)") (class "Default")
      (node (ref "U$276") (pin "VIA") (pinfunction "VIA_VIA") (pintype "bidirectional"))
    )
    (net (code "267") (name "unconnected-(U$277-PadVIA)") (class "Default")
      (node (ref "U$277") (pin "VIA") (pinfunction "VIA_VIA") (pintype "bidirectional"))
    )
    (net (code "268") (name "unconnected-(U$278-PadVIA)") (class "Default")
      (node (ref "U$278") (pin "VIA") (pinfunction "VIA_VIA") (pintype "bidirectional"))
    )
    (net (code "269") (name "unconnected-(U$279-PadVIA)") (class "Default")
      (node (ref "U$279") (pin "VIA") (pinfunction "VIA_VIA") (pintype "bidirectional"))
    )
    (net (code "270") (name "unconnected-(U$280-PadVIA)") (class "Default")
      (node (ref "U$280") (pin "VIA") (pinfunction "VIA_VIA") (pintype "bidirectional"))
    )
    (net (code "271") (name "unconnected-(U$281-PadVIA)") (class "Default")
      (node (ref "U$281") (pin "VIA") (pinfunction "VIA_VIA") (pintype "bidirectional"))
    )
    (net (code "272") (name "unconnected-(U$282-PadVIA)") (class "Default")
      (node (ref "U$282") (pin "VIA") (pinfunction "VIA_VIA") (pintype "bidirectional"))
    )
    (net (code "273") (name "unconnected-(U$283-PadVIA)") (class "Default")
      (node (ref "U$283") (pin "VIA") (pinfunction "VIA_VIA") (pintype "bidirectional"))
    )
    (net (code "274") (name "unconnected-(U$284-PadVIA)") (class "Default")
      (node (ref "U$284") (pin "VIA") (pinfunction "VIA_VIA") (pintype "bidirectional"))
    )
    (net (code "275") (name "unconnected-(U$285-PadVIA)") (class "Default")
      (node (ref "U$285") (pin "VIA") (pinfunction "VIA_VIA") (pintype "bidirectional"))
    )
    (net (code "276") (name "unconnected-(U$286-PadVIA)") (class "Default")
      (node (ref "U$286") (pin "VIA") (pinfunction "VIA_VIA") (pintype "bidirectional"))
    )
    (net (code "277") (name "unconnected-(U$287-PadVIA)") (class "Default")
      (node (ref "U$287") (pin "VIA") (pinfunction "VIA_VIA") (pintype "bidirectional"))
    )
    (net (code "278") (name "unconnected-(U$288-PadVIA)") (class "Default")
      (node (ref "U$288") (pin "VIA") (pinfunction "VIA_VIA") (pintype "bidirectional"))
    )
    (net (code "279") (name "unconnected-(U$289-PadVIA)") (class "Default")
      (node (ref "U$289") (pin "VIA") (pinfunction "VIA_VIA") (pintype "bidirectional"))
    )
    (net (code "280") (name "unconnected-(U$290-PadVIA)") (class "Default")
      (node (ref "U$290") (pin "VIA") (pinfunction "VIA_VIA") (pintype "bidirectional"))
    )
    (net (code "281") (name "unconnected-(U$291-PadVIA)") (class "Default")
      (node (ref "U$291") (pin "VIA") (pinfunction "VIA_VIA") (pintype "bidirectional"))
    )
    (net (code "282") (name "unconnected-(U$292-PadVIA)") (class "Default")
      (node (ref "U$292") (pin "VIA") (pinfunction "VIA_VIA") (pintype "bidirectional"))
    )
    (net (code "283") (name "unconnected-(U$293-PadVIA)") (class "Default")
      (node (ref "U$293") (pin "VIA") (pinfunction "VIA_VIA") (pintype "bidirectional"))
    )
    (net (code "284") (name "unconnected-(U$294-PadVIA)") (class "Default")
      (node (ref "U$294") (pin "VIA") (pinfunction "VIA_VIA") (pintype "bidirectional"))
    )
    (net (code "285") (name "unconnected-(U$295-PadVIA)") (class "Default")
      (node (ref "U$295") (pin "VIA") (pinfunction "VIA_VIA") (pintype "bidirectional"))
    )
    (net (code "286") (name "unconnected-(U$296-PadVIA)") (class "Default")
      (node (ref "U$296") (pin "VIA") (pinfunction "VIA_VIA") (pintype "bidirectional"))
    )
    (net (code "287") (name "unconnected-(U$297-PadVIA)") (class "Default")
      (node (ref "U$297") (pin "VIA") (pinfunction "VIA_VIA") (pintype "bidirectional"))
    )
    (net (code "288") (name "unconnected-(U$298-PadVIA)") (class "Default")
      (node (ref "U$298") (pin "VIA") (pinfunction "VIA_VIA") (pintype "bidirectional"))
    )
    (net (code "289") (name "unconnected-(U$299-PadVIA)") (class "Default")
      (node (ref "U$299") (pin "VIA") (pinfunction "VIA_VIA") (pintype "bidirectional"))
    )
    (net (code "290") (name "unconnected-(U$300-PadVIA)") (class "Default")
      (node (ref "U$300") (pin "VIA") (pinfunction "VIA_VIA") (pintype "bidirectional"))
    )
    (net (code "291") (name "unconnected-(U$301-PadVIA)") (class "Default")
      (node (ref "U$301") (pin "VIA") (pinfunction "VIA_VIA") (pintype "bidirectional"))
    )
    (net (code "292") (name "unconnected-(U$302-PadVIA)") (class "Default")
      (node (ref "U$302") (pin "VIA") (pinfunction "VIA_VIA") (pintype "bidirectional"))
    )
    (net (code "293") (name "unconnected-(U$303-PadVIA)") (class "Default")
      (node (ref "U$303") (pin "VIA") (pinfunction "VIA_VIA") (pintype "bidirectional"))
    )
    (net (code "294") (name "unconnected-(U$304-PadVIA)") (class "Default")
      (node (ref "U$304") (pin "VIA") (pinfunction "VIA_VIA") (pintype "bidirectional"))
    )
    (net (code "295") (name "unconnected-(U$305-PadVIA)") (class "Default")
      (node (ref "U$305") (pin "VIA") (pinfunction "VIA_VIA") (pintype "bidirectional"))
    )
    (net (code "296") (name "unconnected-(U$306-PadVIA)") (class "Default")
      (node (ref "U$306") (pin "VIA") (pinfunction "VIA_VIA") (pintype "bidirectional"))
    )
    (net (code "297") (name "unconnected-(U$307-PadVIA)") (class "Default")
      (node (ref "U$307") (pin "VIA") (pinfunction "VIA_VIA") (pintype "bidirectional"))
    )
    (net (code "298") (name "unconnected-(U$308-PadVIA)") (class "Default")
      (node (ref "U$308") (pin "VIA") (pinfunction "VIA_VIA") (pintype "bidirectional"))
    )
    (net (code "299") (name "unconnected-(U$309-PadVIA)") (class "Default")
      (node (ref "U$309") (pin "VIA") (pinfunction "VIA_VIA") (pintype "bidirectional"))
    )
    (net (code "300") (name "unconnected-(U$310-PadVIA)") (class "Default")
      (node (ref "U$310") (pin "VIA") (pinfunction "VIA_VIA") (pintype "bidirectional"))
    )
    (net (code "301") (name "unconnected-(U$311-PadVIA)") (class "Default")
      (node (ref "U$311") (pin "VIA") (pinfunction "VIA_VIA") (pintype "bidirectional"))
    )
    (net (code "302") (name "unconnected-(U$312-PadVIA)") (class "Default")
      (node (ref "U$312") (pin "VIA") (pinfunction "VIA_VIA") (pintype "bidirectional"))
    )
    (net (code "303") (name "unconnected-(U$313-PadVIA)") (class "Default")
      (node (ref "U$313") (pin "VIA") (pinfunction "VIA_VIA") (pintype "bidirectional"))
    )
    (net (code "304") (name "unconnected-(U$314-PadVIA)") (class "Default")
      (node (ref "U$314") (pin "VIA") (pinfunction "VIA_VIA") (pintype "bidirectional"))
    )
    (net (code "305") (name "unconnected-(U$315-PadVIA)") (class "Default")
      (node (ref "U$315") (pin "VIA") (pinfunction "VIA_VIA") (pintype "bidirectional"))
    )
    (net (code "306") (name "unconnected-(U$316-PadVIA)") (class "Default")
      (node (ref "U$316") (pin "VIA") (pinfunction "VIA_VIA") (pintype "bidirectional"))
    )
    (net (code "307") (name "unconnected-(U$317-PadVIA)") (class "Default")
      (node (ref "U$317") (pin "VIA") (pinfunction "VIA_VIA") (pintype "bidirectional"))
    )
    (net (code "308") (name "unconnected-(U$318-PadVIA)") (class "Default")
      (node (ref "U$318") (pin "VIA") (pinfunction "VIA_VIA") (pintype "bidirectional"))
    )
    (net (code "309") (name "unconnected-(U$319-PadVIA)") (class "Default")
      (node (ref "U$319") (pin "VIA") (pinfunction "VIA_VIA") (pintype "bidirectional"))
    )
    (net (code "310") (name "unconnected-(U$320-PadVIA)") (class "Default")
      (node (ref "U$320") (pin "VIA") (pinfunction "VIA_VIA") (pintype "bidirectional"))
    )
    (net (code "311") (name "unconnected-(U$321-PadVIA)") (class "Default")
      (node (ref "U$321") (pin "VIA") (pinfunction "VIA_VIA") (pintype "bidirectional"))
    )
    (net (code "312") (name "unconnected-(U$322-PadVIA)") (class "Default")
      (node (ref "U$322") (pin "VIA") (pinfunction "VIA_VIA") (pintype "bidirectional"))
    )
    (net (code "313") (name "unconnected-(U$323-PadVIA)") (class "Default")
      (node (ref "U$323") (pin "VIA") (pinfunction "VIA_VIA") (pintype "bidirectional"))
    )
    (net (code "314") (name "unconnected-(U$324-PadVIA)") (class "Default")
      (node (ref "U$324") (pin "VIA") (pinfunction "VIA_VIA") (pintype "bidirectional"))
    )
    (net (code "315") (name "unconnected-(U$325-PadVIA)") (class "Default")
      (node (ref "U$325") (pin "VIA") (pinfunction "VIA_VIA") (pintype "bidirectional"))
    )
    (net (code "316") (name "unconnected-(U$326-PadVIA)") (class "Default")
      (node (ref "U$326") (pin "VIA") (pinfunction "VIA_VIA") (pintype "bidirectional"))
    )
    (net (code "317") (name "unconnected-(U$327-PadVIA)") (class "Default")
      (node (ref "U$327") (pin "VIA") (pinfunction "VIA_VIA") (pintype "bidirectional"))
    )
    (net (code "318") (name "unconnected-(U$328-PadVIA)") (class "Default")
      (node (ref "U$328") (pin "VIA") (pinfunction "VIA_VIA") (pintype "bidirectional"))
    )
    (net (code "319") (name "unconnected-(U$329-PadVIA)") (class "Default")
      (node (ref "U$329") (pin "VIA") (pinfunction "VIA_VIA") (pintype "bidirectional"))
    )
    (net (code "320") (name "unconnected-(U$330-PadVIA)") (class "Default")
      (node (ref "U$330") (pin "VIA") (pinfunction "VIA_VIA") (pintype "bidirectional"))
    )
    (net (code "321") (name "unconnected-(U$331-PadVIA)") (class "Default")
      (node (ref "U$331") (pin "VIA") (pinfunction "VIA_VIA") (pintype "bidirectional"))
    )
    (net (code "322") (name "unconnected-(U$332-PadVIA)") (class "Default")
      (node (ref "U$332") (pin "VIA") (pinfunction "VIA_VIA") (pintype "bidirectional"))
    )
    (net (code "323") (name "unconnected-(U$333-PadVIA)") (class "Default")
      (node (ref "U$333") (pin "VIA") (pinfunction "VIA_VIA") (pintype "bidirectional"))
    )
    (net (code "324") (name "unconnected-(U$334-PadVIA)") (class "Default")
      (node (ref "U$334") (pin "VIA") (pinfunction "VIA_VIA") (pintype "bidirectional"))
    )
    (net (code "325") (name "unconnected-(U$335-PadVIA)") (class "Default")
      (node (ref "U$335") (pin "VIA") (pinfunction "VIA_VIA") (pintype "bidirectional"))
    )
    (net (code "326") (name "unconnected-(U$336-PadVIA)") (class "Default")
      (node (ref "U$336") (pin "VIA") (pinfunction "VIA_VIA") (pintype "bidirectional"))
    )
    (net (code "327") (name "unconnected-(U$337-PadVIA)") (class "Default")
      (node (ref "U$337") (pin "VIA") (pinfunction "VIA_VIA") (pintype "bidirectional"))
    )
    (net (code "328") (name "unconnected-(U$338-PadVIA)") (class "Default")
      (node (ref "U$338") (pin "VIA") (pinfunction "VIA_VIA") (pintype "bidirectional"))
    )
    (net (code "329") (name "unconnected-(U$339-PadVIA)") (class "Default")
      (node (ref "U$339") (pin "VIA") (pinfunction "VIA_VIA") (pintype "bidirectional"))
    )
    (net (code "330") (name "unconnected-(U$340-PadVIA)") (class "Default")
      (node (ref "U$340") (pin "VIA") (pinfunction "VIA_VIA") (pintype "bidirectional"))
    )
    (net (code "331") (name "unconnected-(U$341-PadVIA)") (class "Default")
      (node (ref "U$341") (pin "VIA") (pinfunction "VIA_VIA") (pintype "bidirectional"))
    )
    (net (code "332") (name "unconnected-(U$342-PadVIA)") (class "Default")
      (node (ref "U$342") (pin "VIA") (pinfunction "VIA_VIA") (pintype "bidirectional"))
    )
    (net (code "333") (name "unconnected-(U$343-PadVIA)") (class "Default")
      (node (ref "U$343") (pin "VIA") (pinfunction "VIA_VIA") (pintype "bidirectional"))
    )
    (net (code "334") (name "unconnected-(U$344-PadVIA)") (class "Default")
      (node (ref "U$344") (pin "VIA") (pinfunction "VIA_VIA") (pintype "bidirectional"))
    )
    (net (code "335") (name "unconnected-(U$345-PadVIA)") (class "Default")
      (node (ref "U$345") (pin "VIA") (pinfunction "VIA_VIA") (pintype "bidirectional"))
    )
    (net (code "336") (name "unconnected-(U$346-PadVIA)") (class "Default")
      (node (ref "U$346") (pin "VIA") (pinfunction "VIA_VIA") (pintype "bidirectional"))
    )
    (net (code "337") (name "unconnected-(U$347-PadVIA)") (class "Default")
      (node (ref "U$347") (pin "VIA") (pinfunction "VIA_VIA") (pintype "bidirectional"))
    )
    (net (code "338") (name "unconnected-(U$348-PadVIA)") (class "Default")
      (node (ref "U$348") (pin "VIA") (pinfunction "VIA_VIA") (pintype "bidirectional"))
    )
    (net (code "339") (name "unconnected-(U$349-PadVIA)") (class "Default")
      (node (ref "U$349") (pin "VIA") (pinfunction "VIA_VIA") (pintype "bidirectional"))
    )
    (net (code "340") (name "unconnected-(U$350-PadVIA)") (class "Default")
      (node (ref "U$350") (pin "VIA") (pinfunction "VIA_VIA") (pintype "bidirectional"))
    )
    (net (code "341") (name "unconnected-(U$351-PadVIA)") (class "Default")
      (node (ref "U$351") (pin "VIA") (pinfunction "VIA_VIA") (pintype "bidirectional"))
    )
    (net (code "342") (name "unconnected-(U$352-PadVIA)") (class "Default")
      (node (ref "U$352") (pin "VIA") (pinfunction "VIA_VIA") (pintype "bidirectional"))
    )
    (net (code "343") (name "unconnected-(U$353-PadVIA)") (class "Default")
      (node (ref "U$353") (pin "VIA") (pinfunction "VIA_VIA") (pintype "bidirectional"))
    )
    (net (code "344") (name "unconnected-(U$354-PadVIA)") (class "Default")
      (node (ref "U$354") (pin "VIA") (pinfunction "VIA_VIA") (pintype "bidirectional"))
    )
    (net (code "345") (name "unconnected-(U$355-PadVIA)") (class "Default")
      (node (ref "U$355") (pin "VIA") (pinfunction "VIA_VIA") (pintype "bidirectional"))
    )
    (net (code "346") (name "unconnected-(U$356-PadVIA)") (class "Default")
      (node (ref "U$356") (pin "VIA") (pinfunction "VIA_VIA") (pintype "bidirectional"))
    )
    (net (code "347") (name "unconnected-(U$357-PadVIA)") (class "Default")
      (node (ref "U$357") (pin "VIA") (pinfunction "VIA_VIA") (pintype "bidirectional"))
    )
    (net (code "348") (name "unconnected-(U$358-PadVIA)") (class "Default")
      (node (ref "U$358") (pin "VIA") (pinfunction "VIA_VIA") (pintype "bidirectional"))
    )
    (net (code "349") (name "unconnected-(U$359-PadVIA)") (class "Default")
      (node (ref "U$359") (pin "VIA") (pinfunction "VIA_VIA") (pintype "bidirectional"))
    )
    (net (code "350") (name "unconnected-(U$360-PadVIA)") (class "Default")
      (node (ref "U$360") (pin "VIA") (pinfunction "VIA_VIA") (pintype "bidirectional"))
    )
    (net (code "351") (name "unconnected-(U$361-PadVIA)") (class "Default")
      (node (ref "U$361") (pin "VIA") (pinfunction "VIA_VIA") (pintype "bidirectional"))
    )
    (net (code "352") (name "unconnected-(U$362-PadVIA)") (class "Default")
      (node (ref "U$362") (pin "VIA") (pinfunction "VIA_VIA") (pintype "bidirectional"))
    )
    (net (code "353") (name "unconnected-(U$363-PadVIA)") (class "Default")
      (node (ref "U$363") (pin "VIA") (pinfunction "VIA_VIA") (pintype "bidirectional"))
    )
    (net (code "354") (name "unconnected-(U$364-PadVIA)") (class "Default")
      (node (ref "U$364") (pin "VIA") (pinfunction "VIA_VIA") (pintype "bidirectional"))
    )
    (net (code "355") (name "unconnected-(U$365-PadVIA)") (class "Default")
      (node (ref "U$365") (pin "VIA") (pinfunction "VIA_VIA") (pintype "bidirectional"))
    )
    (net (code "356") (name "unconnected-(U$366-PadVIA)") (class "Default")
      (node (ref "U$366") (pin "VIA") (pinfunction "VIA_VIA") (pintype "bidirectional"))
    )
    (net (code "357") (name "unconnected-(U$367-PadVIA)") (class "Default")
      (node (ref "U$367") (pin "VIA") (pinfunction "VIA_VIA") (pintype "bidirectional"))
    )
    (net (code "358") (name "unconnected-(U$368-PadVIA)") (class "Default")
      (node (ref "U$368") (pin "VIA") (pinfunction "VIA_VIA") (pintype "bidirectional"))
    )
    (net (code "359") (name "unconnected-(U$369-PadVIA)") (class "Default")
      (node (ref "U$369") (pin "VIA") (pinfunction "VIA_VIA") (pintype "bidirectional"))
    )
    (net (code "360") (name "unconnected-(U$370-PadVIA)") (class "Default")
      (node (ref "U$370") (pin "VIA") (pinfunction "VIA_VIA") (pintype "bidirectional"))
    )
    (net (code "361") (name "unconnected-(U$371-PadVIA)") (class "Default")
      (node (ref "U$371") (pin "VIA") (pinfunction "VIA_VIA") (pintype "bidirectional"))
    )
    (net (code "362") (name "unconnected-(U$372-PadVIA)") (class "Default")
      (node (ref "U$372") (pin "VIA") (pinfunction "VIA_VIA") (pintype "bidirectional"))
    )
    (net (code "363") (name "unconnected-(U$373-PadVIA)") (class "Default")
      (node (ref "U$373") (pin "VIA") (pinfunction "VIA_VIA") (pintype "bidirectional"))
    )
    (net (code "364") (name "unconnected-(U$374-PadVIA)") (class "Default")
      (node (ref "U$374") (pin "VIA") (pinfunction "VIA_VIA") (pintype "bidirectional"))
    )
    (net (code "365") (name "unconnected-(U$375-PadVIA)") (class "Default")
      (node (ref "U$375") (pin "VIA") (pinfunction "VIA_VIA") (pintype "bidirectional"))
    )
    (net (code "366") (name "unconnected-(U$376-PadVIA)") (class "Default")
      (node (ref "U$376") (pin "VIA") (pinfunction "VIA_VIA") (pintype "bidirectional"))
    )
    (net (code "367") (name "unconnected-(U$377-PadVIA)") (class "Default")
      (node (ref "U$377") (pin "VIA") (pinfunction "VIA_VIA") (pintype "bidirectional"))
    )
    (net (code "368") (name "unconnected-(U$378-PadVIA)") (class "Default")
      (node (ref "U$378") (pin "VIA") (pinfunction "VIA_VIA") (pintype "bidirectional"))
    )
    (net (code "369") (name "unconnected-(U$379-PadVIA)") (class "Default")
      (node (ref "U$379") (pin "VIA") (pinfunction "VIA_VIA") (pintype "bidirectional"))
    )
    (net (code "370") (name "unconnected-(U$380-PadVIA)") (class "Default")
      (node (ref "U$380") (pin "VIA") (pinfunction "VIA_VIA") (pintype "bidirectional"))
    )
    (net (code "371") (name "unconnected-(U$381-PadVIA)") (class "Default")
      (node (ref "U$381") (pin "VIA") (pinfunction "VIA_VIA") (pintype "bidirectional"))
    )
    (net (code "372") (name "unconnected-(U$382-PadVIA)") (class "Default")
      (node (ref "U$382") (pin "VIA") (pinfunction "VIA_VIA") (pintype "bidirectional"))
    )
    (net (code "373") (name "unconnected-(U$383-PadVIA)") (class "Default")
      (node (ref "U$383") (pin "VIA") (pinfunction "VIA_VIA") (pintype "bidirectional"))
    )
    (net (code "374") (name "unconnected-(U$384-PadVIA)") (class "Default")
      (node (ref "U$384") (pin "VIA") (pinfunction "VIA_VIA") (pintype "bidirectional"))
    )
    (net (code "375") (name "unconnected-(U$385-PadVIA)") (class "Default")
      (node (ref "U$385") (pin "VIA") (pinfunction "VIA_VIA") (pintype "bidirectional"))
    )
    (net (code "376") (name "unconnected-(U$386-PadVIA)") (class "Default")
      (node (ref "U$386") (pin "VIA") (pinfunction "VIA_VIA") (pintype "bidirectional"))
    )
    (net (code "377") (name "unconnected-(U$387-PadVIA)") (class "Default")
      (node (ref "U$387") (pin "VIA") (pinfunction "VIA_VIA") (pintype "bidirectional"))
    )
    (net (code "378") (name "unconnected-(U$388-PadVIA)") (class "Default")
      (node (ref "U$388") (pin "VIA") (pinfunction "VIA_VIA") (pintype "bidirectional"))
    )
    (net (code "379") (name "unconnected-(U$389-PadVIA)") (class "Default")
      (node (ref "U$389") (pin "VIA") (pinfunction "VIA_VIA") (pintype "bidirectional"))
    )
    (net (code "380") (name "unconnected-(U$390-PadVIA)") (class "Default")
      (node (ref "U$390") (pin "VIA") (pinfunction "VIA_VIA") (pintype "bidirectional"))
    )
    (net (code "381") (name "unconnected-(U$391-PadVIA)") (class "Default")
      (node (ref "U$391") (pin "VIA") (pinfunction "VIA_VIA") (pintype "bidirectional"))
    )
    (net (code "382") (name "unconnected-(U$392-PadVIA)") (class "Default")
      (node (ref "U$392") (pin "VIA") (pinfunction "VIA_VIA") (pintype "bidirectional"))
    )
    (net (code "383") (name "unconnected-(U$393-PadVIA)") (class "Default")
      (node (ref "U$393") (pin "VIA") (pinfunction "VIA_VIA") (pintype "bidirectional"))
    )
    (net (code "384") (name "unconnected-(U$394-PadVIA)") (class "Default")
      (node (ref "U$394") (pin "VIA") (pinfunction "VIA_VIA") (pintype "bidirectional"))
    )
    (net (code "385") (name "unconnected-(U$395-PadVIA)") (class "Default")
      (node (ref "U$395") (pin "VIA") (pinfunction "VIA_VIA") (pintype "bidirectional"))
    )
    (net (code "386") (name "unconnected-(U$396-PadVIA)") (class "Default")
      (node (ref "U$396") (pin "VIA") (pinfunction "VIA_VIA") (pintype "bidirectional"))
    )
    (net (code "387") (name "unconnected-(U$397-PadVIA)") (class "Default")
      (node (ref "U$397") (pin "VIA") (pinfunction "VIA_VIA") (pintype "bidirectional"))
    )
    (net (code "388") (name "unconnected-(U$398-PadVIA)") (class "Default")
      (node (ref "U$398") (pin "VIA") (pinfunction "VIA_VIA") (pintype "bidirectional"))
    )
    (net (code "389") (name "unconnected-(U$399-PadVIA)") (class "Default")
      (node (ref "U$399") (pin "VIA") (pinfunction "VIA_VIA") (pintype "bidirectional"))
    )
    (net (code "390") (name "unconnected-(U$400-PadVIA)") (class "Default")
      (node (ref "U$400") (pin "VIA") (pinfunction "VIA_VIA") (pintype "bidirectional"))
    )
    (net (code "391") (name "unconnected-(U$401-PadVIA)") (class "Default")
      (node (ref "U$401") (pin "VIA") (pinfunction "VIA_VIA") (pintype "bidirectional"))
    )
    (net (code "392") (name "unconnected-(U$402-PadVIA)") (class "Default")
      (node (ref "U$402") (pin "VIA") (pinfunction "VIA_VIA") (pintype "bidirectional"))
    )
    (net (code "393") (name "unconnected-(U$403-PadVIA)") (class "Default")
      (node (ref "U$403") (pin "VIA") (pinfunction "VIA_VIA") (pintype "bidirectional"))
    )
    (net (code "394") (name "unconnected-(U$404-PadVIA)") (class "Default")
      (node (ref "U$404") (pin "VIA") (pinfunction "VIA_VIA") (pintype "bidirectional"))
    )
    (net (code "395") (name "unconnected-(U$405-PadVIA)") (class "Default")
      (node (ref "U$405") (pin "VIA") (pinfunction "VIA_VIA") (pintype "bidirectional"))
    )
    (net (code "396") (name "unconnected-(U$406-PadVIA)") (class "Default")
      (node (ref "U$406") (pin "VIA") (pinfunction "VIA_VIA") (pintype "bidirectional"))
    )
    (net (code "397") (name "unconnected-(U$407-PadVIA)") (class "Default")
      (node (ref "U$407") (pin "VIA") (pinfunction "VIA_VIA") (pintype "bidirectional"))
    )
    (net (code "398") (name "unconnected-(U$408-PadVIA)") (class "Default")
      (node (ref "U$408") (pin "VIA") (pinfunction "VIA_VIA") (pintype "bidirectional"))
    )
    (net (code "399") (name "unconnected-(U$409-PadVIA)") (class "Default")
      (node (ref "U$409") (pin "VIA") (pinfunction "VIA_VIA") (pintype "bidirectional"))
    )
    (net (code "400") (name "unconnected-(U$410-PadVIA)") (class "Default")
      (node (ref "U$410") (pin "VIA") (pinfunction "VIA_VIA") (pintype "bidirectional"))
    )
    (net (code "401") (name "unconnected-(U$411-PadVIA)") (class "Default")
      (node (ref "U$411") (pin "VIA") (pinfunction "VIA_VIA") (pintype "bidirectional"))
    )
    (net (code "402") (name "unconnected-(U$412-PadVIA)") (class "Default")
      (node (ref "U$412") (pin "VIA") (pinfunction "VIA_VIA") (pintype "bidirectional"))
    )
    (net (code "403") (name "unconnected-(U$413-PadVIA)") (class "Default")
      (node (ref "U$413") (pin "VIA") (pinfunction "VIA_VIA") (pintype "bidirectional"))
    )
    (net (code "404") (name "unconnected-(U$414-PadVIA)") (class "Default")
      (node (ref "U$414") (pin "VIA") (pinfunction "VIA_VIA") (pintype "bidirectional"))
    )
    (net (code "405") (name "unconnected-(U$415-PadVIA)") (class "Default")
      (node (ref "U$415") (pin "VIA") (pinfunction "VIA_VIA") (pintype "bidirectional"))
    )
    (net (code "406") (name "unconnected-(U$416-PadVIA)") (class "Default")
      (node (ref "U$416") (pin "VIA") (pinfunction "VIA_VIA") (pintype "bidirectional"))
    )
    (net (code "407") (name "unconnected-(U$417-PadVIA)") (class "Default")
      (node (ref "U$417") (pin "VIA") (pinfunction "VIA_VIA") (pintype "bidirectional"))
    )
    (net (code "408") (name "unconnected-(U$418-PadVIA)") (class "Default")
      (node (ref "U$418") (pin "VIA") (pinfunction "VIA_VIA") (pintype "bidirectional"))
    )
    (net (code "409") (name "unconnected-(U$419-PadVIA)") (class "Default")
      (node (ref "U$419") (pin "VIA") (pinfunction "VIA_VIA") (pintype "bidirectional"))
    )
    (net (code "410") (name "unconnected-(U$420-PadVIA)") (class "Default")
      (node (ref "U$420") (pin "VIA") (pinfunction "VIA_VIA") (pintype "bidirectional"))
    )
    (net (code "411") (name "unconnected-(U$421-PadVIA)") (class "Default")
      (node (ref "U$421") (pin "VIA") (pinfunction "VIA_VIA") (pintype "bidirectional"))
    )
    (net (code "412") (name "unconnected-(U$422-PadVIA)") (class "Default")
      (node (ref "U$422") (pin "VIA") (pinfunction "VIA_VIA") (pintype "bidirectional"))
    )
    (net (code "413") (name "unconnected-(U$423-PadVIA)") (class "Default")
      (node (ref "U$423") (pin "VIA") (pinfunction "VIA_VIA") (pintype "bidirectional"))
    )
    (net (code "414") (name "unconnected-(U$424-PadVIA)") (class "Default")
      (node (ref "U$424") (pin "VIA") (pinfunction "VIA_VIA") (pintype "bidirectional"))
    )
    (net (code "415") (name "unconnected-(U$425-PadVIA)") (class "Default")
      (node (ref "U$425") (pin "VIA") (pinfunction "VIA_VIA") (pintype "bidirectional"))
    )
    (net (code "416") (name "unconnected-(U$426-PadVIA)") (class "Default")
      (node (ref "U$426") (pin "VIA") (pinfunction "VIA_VIA") (pintype "bidirectional"))
    )
    (net (code "417") (name "unconnected-(U$427-PadVIA)") (class "Default")
      (node (ref "U$427") (pin "VIA") (pinfunction "VIA_VIA") (pintype "bidirectional"))
    )
    (net (code "418") (name "unconnected-(U$428-PadVIA)") (class "Default")
      (node (ref "U$428") (pin "VIA") (pinfunction "VIA_VIA") (pintype "bidirectional"))
    )
    (net (code "419") (name "unconnected-(U$429-PadVIA)") (class "Default")
      (node (ref "U$429") (pin "VIA") (pinfunction "VIA_VIA") (pintype "bidirectional"))
    )
    (net (code "420") (name "unconnected-(U$430-PadVIA)") (class "Default")
      (node (ref "U$430") (pin "VIA") (pinfunction "VIA_VIA") (pintype "bidirectional"))
    )
    (net (code "421") (name "unconnected-(U$431-PadVIA)") (class "Default")
      (node (ref "U$431") (pin "VIA") (pinfunction "VIA_VIA") (pintype "bidirectional"))
    )
    (net (code "422") (name "unconnected-(U$432-PadVIA)") (class "Default")
      (node (ref "U$432") (pin "VIA") (pinfunction "VIA_VIA") (pintype "bidirectional"))
    )
    (net (code "423") (name "unconnected-(U$433-PadVIA)") (class "Default")
      (node (ref "U$433") (pin "VIA") (pinfunction "VIA_VIA") (pintype "bidirectional"))
    )
    (net (code "424") (name "unconnected-(U$434-PadVIA)") (class "Default")
      (node (ref "U$434") (pin "VIA") (pinfunction "VIA_VIA") (pintype "bidirectional"))
    )
    (net (code "425") (name "unconnected-(U$435-PadVIA)") (class "Default")
      (node (ref "U$435") (pin "VIA") (pinfunction "VIA_VIA") (pintype "bidirectional"))
    )
    (net (code "426") (name "unconnected-(U$436-PadVIA)") (class "Default")
      (node (ref "U$436") (pin "VIA") (pinfunction "VIA_VIA") (pintype "bidirectional"))
    )
    (net (code "427") (name "unconnected-(U$437-PadVIA)") (class "Default")
      (node (ref "U$437") (pin "VIA") (pinfunction "VIA_VIA") (pintype "bidirectional"))
    )
    (net (code "428") (name "unconnected-(U$438-PadVIA)") (class "Default")
      (node (ref "U$438") (pin "VIA") (pinfunction "VIA_VIA") (pintype "bidirectional"))
    )
    (net (code "429") (name "unconnected-(U$439-PadVIA)") (class "Default")
      (node (ref "U$439") (pin "VIA") (pinfunction "VIA_VIA") (pintype "bidirectional"))
    )
    (net (code "430") (name "unconnected-(U$440-PadVIA)") (class "Default")
      (node (ref "U$440") (pin "VIA") (pinfunction "VIA_VIA") (pintype "bidirectional"))
    )
    (net (code "431") (name "unconnected-(U$441-PadVIA)") (class "Default")
      (node (ref "U$441") (pin "VIA") (pinfunction "VIA_VIA") (pintype "bidirectional"))
    )
    (net (code "432") (name "unconnected-(U$442-PadVIA)") (class "Default")
      (node (ref "U$442") (pin "VIA") (pinfunction "VIA_VIA") (pintype "bidirectional"))
    )
    (net (code "433") (name "unconnected-(U$443-PadVIA)") (class "Default")
      (node (ref "U$443") (pin "VIA") (pinfunction "VIA_VIA") (pintype "bidirectional"))
    )
    (net (code "434") (name "unconnected-(U$444-PadVIA)") (class "Default")
      (node (ref "U$444") (pin "VIA") (pinfunction "VIA_VIA") (pintype "bidirectional"))
    )
    (net (code "435") (name "unconnected-(U$445-PadVIA)") (class "Default")
      (node (ref "U$445") (pin "VIA") (pinfunction "VIA_VIA") (pintype "bidirectional"))
    )
    (net (code "436") (name "unconnected-(U$446-PadVIA)") (class "Default")
      (node (ref "U$446") (pin "VIA") (pinfunction "VIA_VIA") (pintype "bidirectional"))
    )
    (net (code "437") (name "unconnected-(U$447-PadVIA)") (class "Default")
      (node (ref "U$447") (pin "VIA") (pinfunction "VIA_VIA") (pintype "bidirectional"))
    )
    (net (code "438") (name "unconnected-(U$448-PadVIA)") (class "Default")
      (node (ref "U$448") (pin "VIA") (pinfunction "VIA_VIA") (pintype "bidirectional"))
    )
    (net (code "439") (name "unconnected-(U$449-PadVIA)") (class "Default")
      (node (ref "U$449") (pin "VIA") (pinfunction "VIA_VIA") (pintype "bidirectional"))
    )
    (net (code "440") (name "unconnected-(U$450-PadVIA)") (class "Default")
      (node (ref "U$450") (pin "VIA") (pinfunction "VIA_VIA") (pintype "bidirectional"))
    )
    (net (code "441") (name "unconnected-(U$451-PadVIA)") (class "Default")
      (node (ref "U$451") (pin "VIA") (pinfunction "VIA_VIA") (pintype "bidirectional"))
    )
    (net (code "442") (name "unconnected-(U$452-PadVIA)") (class "Default")
      (node (ref "U$452") (pin "VIA") (pinfunction "VIA_VIA") (pintype "bidirectional"))
    )
    (net (code "443") (name "unconnected-(U$453-PadVIA)") (class "Default")
      (node (ref "U$453") (pin "VIA") (pinfunction "VIA_VIA") (pintype "bidirectional"))
    )
    (net (code "444") (name "unconnected-(U$454-PadVIA)") (class "Default")
      (node (ref "U$454") (pin "VIA") (pinfunction "VIA_VIA") (pintype "bidirectional"))
    )
    (net (code "445") (name "unconnected-(U$455-PadVIA)") (class "Default")
      (node (ref "U$455") (pin "VIA") (pinfunction "VIA_VIA") (pintype "bidirectional"))
    )
    (net (code "446") (name "unconnected-(U$456-PadVIA)") (class "Default")
      (node (ref "U$456") (pin "VIA") (pinfunction "VIA_VIA") (pintype "bidirectional"))
    )
    (net (code "447") (name "unconnected-(U$457-PadVIA)") (class "Default")
      (node (ref "U$457") (pin "VIA") (pinfunction "VIA_VIA") (pintype "bidirectional"))
    )
    (net (code "448") (name "unconnected-(U$458-PadVIA)") (class "Default")
      (node (ref "U$458") (pin "VIA") (pinfunction "VIA_VIA") (pintype "bidirectional"))
    )
    (net (code "449") (name "unconnected-(U$459-PadVIA)") (class "Default")
      (node (ref "U$459") (pin "VIA") (pinfunction "VIA_VIA") (pintype "bidirectional"))
    )
    (net (code "450") (name "unconnected-(U$460-PadVIA)") (class "Default")
      (node (ref "U$460") (pin "VIA") (pinfunction "VIA_VIA") (pintype "bidirectional"))
    )
    (net (code "451") (name "unconnected-(U$461-PadVIA)") (class "Default")
      (node (ref "U$461") (pin "VIA") (pinfunction "VIA_VIA") (pintype "bidirectional"))
    )
    (net (code "452") (name "unconnected-(U$462-PadVIA)") (class "Default")
      (node (ref "U$462") (pin "VIA") (pinfunction "VIA_VIA") (pintype "bidirectional"))
    )
    (net (code "453") (name "unconnected-(U$463-PadVIA)") (class "Default")
      (node (ref "U$463") (pin "VIA") (pinfunction "VIA_VIA") (pintype "bidirectional"))
    )
    (net (code "454") (name "unconnected-(U$464-PadVIA)") (class "Default")
      (node (ref "U$464") (pin "VIA") (pinfunction "VIA_VIA") (pintype "bidirectional"))
    )
    (net (code "455") (name "unconnected-(U$465-PadVIA)") (class "Default")
      (node (ref "U$465") (pin "VIA") (pinfunction "VIA_VIA") (pintype "bidirectional"))
    )
    (net (code "456") (name "unconnected-(U$466-PadVIA)") (class "Default")
      (node (ref "U$466") (pin "VIA") (pinfunction "VIA_VIA") (pintype "bidirectional"))
    )
    (net (code "457") (name "unconnected-(U$467-PadVIA)") (class "Default")
      (node (ref "U$467") (pin "VIA") (pinfunction "VIA_VIA") (pintype "bidirectional"))
    )
    (net (code "458") (name "unconnected-(U$468-PadVIA)") (class "Default")
      (node (ref "U$468") (pin "VIA") (pinfunction "VIA_VIA") (pintype "bidirectional"))
    )
    (net (code "459") (name "unconnected-(U$469-PadVIA)") (class "Default")
      (node (ref "U$469") (pin "VIA") (pinfunction "VIA_VIA") (pintype "bidirectional"))
    )
    (net (code "460") (name "unconnected-(U$470-PadVIA)") (class "Default")
      (node (ref "U$470") (pin "VIA") (pinfunction "VIA_VIA") (pintype "bidirectional"))
    )
    (net (code "461") (name "unconnected-(U$471-PadVIA)") (class "Default")
      (node (ref "U$471") (pin "VIA") (pinfunction "VIA_VIA") (pintype "bidirectional"))
    )
    (net (code "462") (name "unconnected-(U$472-PadVIA)") (class "Default")
      (node (ref "U$472") (pin "VIA") (pinfunction "VIA_VIA") (pintype "bidirectional"))
    )
    (net (code "463") (name "unconnected-(U$473-PadVIA)") (class "Default")
      (node (ref "U$473") (pin "VIA") (pinfunction "VIA_VIA") (pintype "bidirectional"))
    )
    (net (code "464") (name "unconnected-(U$474-PadVIA)") (class "Default")
      (node (ref "U$474") (pin "VIA") (pinfunction "VIA_VIA") (pintype "bidirectional"))
    )
    (net (code "465") (name "unconnected-(U$475-PadVIA)") (class "Default")
      (node (ref "U$475") (pin "VIA") (pinfunction "VIA_VIA") (pintype "bidirectional"))
    )
    (net (code "466") (name "unconnected-(U$476-PadVIA)") (class "Default")
      (node (ref "U$476") (pin "VIA") (pinfunction "VIA_VIA") (pintype "bidirectional"))
    )
    (net (code "467") (name "unconnected-(U$477-PadVIA)") (class "Default")
      (node (ref "U$477") (pin "VIA") (pinfunction "VIA_VIA") (pintype "bidirectional"))
    )
    (net (code "468") (name "unconnected-(U$478-PadVIA)") (class "Default")
      (node (ref "U$478") (pin "VIA") (pinfunction "VIA_VIA") (pintype "bidirectional"))
    )
    (net (code "469") (name "unconnected-(U$479-PadVIA)") (class "Default")
      (node (ref "U$479") (pin "VIA") (pinfunction "VIA_VIA") (pintype "bidirectional"))
    )
    (net (code "470") (name "unconnected-(U$480-PadVIA)") (class "Default")
      (node (ref "U$480") (pin "VIA") (pinfunction "VIA_VIA") (pintype "bidirectional"))
    )
    (net (code "471") (name "unconnected-(U$481-PadVIA)") (class "Default")
      (node (ref "U$481") (pin "VIA") (pinfunction "VIA_VIA") (pintype "bidirectional"))
    )
    (net (code "472") (name "unconnected-(U$482-PadVIA)") (class "Default")
      (node (ref "U$482") (pin "VIA") (pinfunction "VIA_VIA") (pintype "bidirectional"))
    )
    (net (code "473") (name "unconnected-(U$483-PadVIA)") (class "Default")
      (node (ref "U$483") (pin "VIA") (pinfunction "VIA_VIA") (pintype "bidirectional"))
    )
    (net (code "474") (name "unconnected-(U$484-PadVIA)") (class "Default")
      (node (ref "U$484") (pin "VIA") (pinfunction "VIA_VIA") (pintype "bidirectional"))
    )
    (net (code "475") (name "unconnected-(U$485-PadVIA)") (class "Default")
      (node (ref "U$485") (pin "VIA") (pinfunction "VIA_VIA") (pintype "bidirectional"))
    )
    (net (code "476") (name "unconnected-(U$486-PadVIA)") (class "Default")
      (node (ref "U$486") (pin "VIA") (pinfunction "VIA_VIA") (pintype "bidirectional"))
    )
    (net (code "477") (name "unconnected-(U$487-PadVIA)") (class "Default")
      (node (ref "U$487") (pin "VIA") (pinfunction "VIA_VIA") (pintype "bidirectional"))
    )
    (net (code "478") (name "unconnected-(U$488-PadVIA)") (class "Default")
      (node (ref "U$488") (pin "VIA") (pinfunction "VIA_VIA") (pintype "bidirectional"))
    )
    (net (code "479") (name "unconnected-(U$489-PadVIA)") (class "Default")
      (node (ref "U$489") (pin "VIA") (pinfunction "VIA_VIA") (pintype "bidirectional"))
    )
    (net (code "480") (name "unconnected-(U$490-PadVIA)") (class "Default")
      (node (ref "U$490") (pin "VIA") (pinfunction "VIA_VIA") (pintype "bidirectional"))
    )
    (net (code "481") (name "unconnected-(U$491-PadVIA)") (class "Default")
      (node (ref "U$491") (pin "VIA") (pinfunction "VIA_VIA") (pintype "bidirectional"))
    )
    (net (code "482") (name "unconnected-(U$492-PadVIA)") (class "Default")
      (node (ref "U$492") (pin "VIA") (pinfunction "VIA_VIA") (pintype "bidirectional"))
    )
    (net (code "483") (name "unconnected-(U$493-PadVIA)") (class "Default")
      (node (ref "U$493") (pin "VIA") (pinfunction "VIA_VIA") (pintype "bidirectional"))
    )
    (net (code "484") (name "unconnected-(U$494-PadVIA)") (class "Default")
      (node (ref "U$494") (pin "VIA") (pinfunction "VIA_VIA") (pintype "bidirectional"))
    )
    (net (code "485") (name "unconnected-(U$495-PadVIA)") (class "Default")
      (node (ref "U$495") (pin "VIA") (pinfunction "VIA_VIA") (pintype "bidirectional"))
    )
    (net (code "486") (name "unconnected-(U$496-PadVIA)") (class "Default")
      (node (ref "U$496") (pin "VIA") (pinfunction "VIA_VIA") (pintype "bidirectional"))
    )
    (net (code "487") (name "unconnected-(U$497-PadVIA)") (class "Default")
      (node (ref "U$497") (pin "VIA") (pinfunction "VIA_VIA") (pintype "bidirectional"))
    )
    (net (code "488") (name "unconnected-(U$498-PadVIA)") (class "Default")
      (node (ref "U$498") (pin "VIA") (pinfunction "VIA_VIA") (pintype "bidirectional"))
    )
    (net (code "489") (name "unconnected-(U$499-PadVIA)") (class "Default")
      (node (ref "U$499") (pin "VIA") (pinfunction "VIA_VIA") (pintype "bidirectional"))
    )
    (net (code "490") (name "unconnected-(U$500-PadVIA)") (class "Default")
      (node (ref "U$500") (pin "VIA") (pinfunction "VIA_VIA") (pintype "bidirectional"))
    )
    (net (code "491") (name "unconnected-(U$501-PadVIA)") (class "Default")
      (node (ref "U$501") (pin "VIA") (pinfunction "VIA_VIA") (pintype "bidirectional"))
    )
    (net (code "492") (name "unconnected-(U$502-PadVIA)") (class "Default")
      (node (ref "U$502") (pin "VIA") (pinfunction "VIA_VIA") (pintype "bidirectional"))
    )
    (net (code "493") (name "unconnected-(U$503-PadVIA)") (class "Default")
      (node (ref "U$503") (pin "VIA") (pinfunction "VIA_VIA") (pintype "bidirectional"))
    )
    (net (code "494") (name "unconnected-(U$504-PadVIA)") (class "Default")
      (node (ref "U$504") (pin "VIA") (pinfunction "VIA_VIA") (pintype "bidirectional"))
    )
    (net (code "495") (name "unconnected-(U$505-PadVIA)") (class "Default")
      (node (ref "U$505") (pin "VIA") (pinfunction "VIA_VIA") (pintype "bidirectional"))
    )
    (net (code "496") (name "unconnected-(U$506-PadVIA)") (class "Default")
      (node (ref "U$506") (pin "VIA") (pinfunction "VIA_VIA") (pintype "bidirectional"))
    )
    (net (code "497") (name "unconnected-(U$507-PadVIA)") (class "Default")
      (node (ref "U$507") (pin "VIA") (pinfunction "VIA_VIA") (pintype "bidirectional"))
    )
    (net (code "498") (name "unconnected-(U$508-PadVIA)") (class "Default")
      (node (ref "U$508") (pin "VIA") (pinfunction "VIA_VIA") (pintype "bidirectional"))
    )
    (net (code "499") (name "unconnected-(U$509-PadVIA)") (class "Default")
      (node (ref "U$509") (pin "VIA") (pinfunction "VIA_VIA") (pintype "bidirectional"))
    )
    (net (code "500") (name "unconnected-(U$510-PadVIA)") (class "Default")
      (node (ref "U$510") (pin "VIA") (pinfunction "VIA_VIA") (pintype "bidirectional"))
    )
    (net (code "501") (name "unconnected-(U$511-PadVIA)") (class "Default")
      (node (ref "U$511") (pin "VIA") (pinfunction "VIA_VIA") (pintype "bidirectional"))
    )
    (net (code "502") (name "unconnected-(U$512-PadVIA)") (class "Default")
      (node (ref "U$512") (pin "VIA") (pinfunction "VIA_VIA") (pintype "bidirectional"))
    )
    (net (code "503") (name "unconnected-(U$513-PadVIA)") (class "Default")
      (node (ref "U$513") (pin "VIA") (pinfunction "VIA_VIA") (pintype "bidirectional"))
    )
    (net (code "504") (name "unconnected-(U$514-PadVIA)") (class "Default")
      (node (ref "U$514") (pin "VIA") (pinfunction "VIA_VIA") (pintype "bidirectional"))
    )
    (net (code "505") (name "unconnected-(U$515-PadVIA)") (class "Default")
      (node (ref "U$515") (pin "VIA") (pinfunction "VIA_VIA") (pintype "bidirectional"))
    )
    (net (code "506") (name "unconnected-(U$516-PadVIA)") (class "Default")
      (node (ref "U$516") (pin "VIA") (pinfunction "VIA_VIA") (pintype "bidirectional"))
    )
    (net (code "507") (name "unconnected-(U$517-PadVIA)") (class "Default")
      (node (ref "U$517") (pin "VIA") (pinfunction "VIA_VIA") (pintype "bidirectional"))
    )
    (net (code "508") (name "unconnected-(U$518-PadVIA)") (class "Default")
      (node (ref "U$518") (pin "VIA") (pinfunction "VIA_VIA") (pintype "bidirectional"))
    )
    (net (code "509") (name "unconnected-(U$519-PadVIA)") (class "Default")
      (node (ref "U$519") (pin "VIA") (pinfunction "VIA_VIA") (pintype "bidirectional"))
    )
    (net (code "510") (name "unconnected-(U$520-PadVIA)") (class "Default")
      (node (ref "U$520") (pin "VIA") (pinfunction "VIA_VIA") (pintype "bidirectional"))
    )
    (net (code "511") (name "unconnected-(U$521-PadVIA)") (class "Default")
      (node (ref "U$521") (pin "VIA") (pinfunction "VIA_VIA") (pintype "bidirectional"))
    )
    (net (code "512") (name "unconnected-(U$522-PadVIA)") (class "Default")
      (node (ref "U$522") (pin "VIA") (pinfunction "VIA_VIA") (pintype "bidirectional"))
    )
    (net (code "513") (name "unconnected-(U$523-PadVIA)") (class "Default")
      (node (ref "U$523") (pin "VIA") (pinfunction "VIA_VIA") (pintype "bidirectional"))
    )
    (net (code "514") (name "unconnected-(U$524-PadVIA)") (class "Default")
      (node (ref "U$524") (pin "VIA") (pinfunction "VIA_VIA") (pintype "bidirectional"))
    )
    (net (code "515") (name "unconnected-(U$525-PadVIA)") (class "Default")
      (node (ref "U$525") (pin "VIA") (pinfunction "VIA_VIA") (pintype "bidirectional"))
    )
    (net (code "516") (name "unconnected-(U$526-PadVIA)") (class "Default")
      (node (ref "U$526") (pin "VIA") (pinfunction "VIA_VIA") (pintype "bidirectional"))
    )
    (net (code "517") (name "unconnected-(U$527-PadVIA)") (class "Default")
      (node (ref "U$527") (pin "VIA") (pinfunction "VIA_VIA") (pintype "bidirectional"))
    )
    (net (code "518") (name "unconnected-(U$528-PadVIA)") (class "Default")
      (node (ref "U$528") (pin "VIA") (pinfunction "VIA_VIA") (pintype "bidirectional"))
    )
    (net (code "519") (name "unconnected-(U$529-PadVIA)") (class "Default")
      (node (ref "U$529") (pin "VIA") (pinfunction "VIA_VIA") (pintype "bidirectional"))
    )
    (net (code "520") (name "unconnected-(U$530-PadVIA)") (class "Default")
      (node (ref "U$530") (pin "VIA") (pinfunction "VIA_VIA") (pintype "bidirectional"))
    )
    (net (code "521") (name "unconnected-(U$531-PadVIA)") (class "Default")
      (node (ref "U$531") (pin "VIA") (pinfunction "VIA_VIA") (pintype "bidirectional"))
    )
    (net (code "522") (name "unconnected-(U$532-PadVIA)") (class "Default")
      (node (ref "U$532") (pin "VIA") (pinfunction "VIA_VIA") (pintype "bidirectional"))
    )
    (net (code "523") (name "unconnected-(U$533-PadVIA)") (class "Default")
      (node (ref "U$533") (pin "VIA") (pinfunction "VIA_VIA") (pintype "bidirectional"))
    )
    (net (code "524") (name "unconnected-(U$534-PadVIA)") (class "Default")
      (node (ref "U$534") (pin "VIA") (pinfunction "VIA_VIA") (pintype "bidirectional"))
    )
    (net (code "525") (name "unconnected-(U$535-PadVIA)") (class "Default")
      (node (ref "U$535") (pin "VIA") (pinfunction "VIA_VIA") (pintype "bidirectional"))
    )
    (net (code "526") (name "unconnected-(U$536-PadVIA)") (class "Default")
      (node (ref "U$536") (pin "VIA") (pinfunction "VIA_VIA") (pintype "bidirectional"))
    )
    (net (code "527") (name "unconnected-(U$537-PadVIA)") (class "Default")
      (node (ref "U$537") (pin "VIA") (pinfunction "VIA_VIA") (pintype "bidirectional"))
    )
    (net (code "528") (name "unconnected-(U$538-PadVIA)") (class "Default")
      (node (ref "U$538") (pin "VIA") (pinfunction "VIA_VIA") (pintype "bidirectional"))
    )
    (net (code "529") (name "unconnected-(U$539-PadVIA)") (class "Default")
      (node (ref "U$539") (pin "VIA") (pinfunction "VIA_VIA") (pintype "bidirectional"))
    )
    (net (code "530") (name "unconnected-(U$540-PadVIA)") (class "Default")
      (node (ref "U$540") (pin "VIA") (pinfunction "VIA_VIA") (pintype "bidirectional"))
    )
    (net (code "531") (name "unconnected-(U$541-PadVIA)") (class "Default")
      (node (ref "U$541") (pin "VIA") (pinfunction "VIA_VIA") (pintype "bidirectional"))
    )
    (net (code "532") (name "unconnected-(U$542-PadVIA)") (class "Default")
      (node (ref "U$542") (pin "VIA") (pinfunction "VIA_VIA") (pintype "bidirectional"))
    )
    (net (code "533") (name "unconnected-(U$543-PadVIA)") (class "Default")
      (node (ref "U$543") (pin "VIA") (pinfunction "VIA_VIA") (pintype "bidirectional"))
    )
    (net (code "534") (name "unconnected-(U$544-PadVIA)") (class "Default")
      (node (ref "U$544") (pin "VIA") (pinfunction "VIA_VIA") (pintype "bidirectional"))
    )
    (net (code "535") (name "unconnected-(U$545-PadVIA)") (class "Default")
      (node (ref "U$545") (pin "VIA") (pinfunction "VIA_VIA") (pintype "bidirectional"))
    )
    (net (code "536") (name "unconnected-(U$546-PadVIA)") (class "Default")
      (node (ref "U$546") (pin "VIA") (pinfunction "VIA_VIA") (pintype "bidirectional"))
    )
    (net (code "537") (name "unconnected-(U$547-PadVIA)") (class "Default")
      (node (ref "U$547") (pin "VIA") (pinfunction "VIA_VIA") (pintype "bidirectional"))
    )
    (net (code "538") (name "unconnected-(U$548-PadVIA)") (class "Default")
      (node (ref "U$548") (pin "VIA") (pinfunction "VIA_VIA") (pintype "bidirectional"))
    )
    (net (code "539") (name "unconnected-(U$549-PadVIA)") (class "Default")
      (node (ref "U$549") (pin "VIA") (pinfunction "VIA_VIA") (pintype "bidirectional"))
    )
    (net (code "540") (name "unconnected-(U$550-PadVIA)") (class "Default")
      (node (ref "U$550") (pin "VIA") (pinfunction "VIA_VIA") (pintype "bidirectional"))
    )
    (net (code "541") (name "unconnected-(U$551-PadVIA)") (class "Default")
      (node (ref "U$551") (pin "VIA") (pinfunction "VIA_VIA") (pintype "bidirectional"))
    )
    (net (code "542") (name "unconnected-(U$552-PadVIA)") (class "Default")
      (node (ref "U$552") (pin "VIA") (pinfunction "VIA_VIA") (pintype "bidirectional"))
    )
    (net (code "543") (name "unconnected-(U$553-PadVIA)") (class "Default")
      (node (ref "U$553") (pin "VIA") (pinfunction "VIA_VIA") (pintype "bidirectional"))
    )
    (net (code "544") (name "unconnected-(U$554-PadVIA)") (class "Default")
      (node (ref "U$554") (pin "VIA") (pinfunction "VIA_VIA") (pintype "bidirectional"))
    )
    (net (code "545") (name "unconnected-(U$555-PadVIA)") (class "Default")
      (node (ref "U$555") (pin "VIA") (pinfunction "VIA_VIA") (pintype "bidirectional"))
    )
    (net (code "546") (name "unconnected-(U$556-PadVIA)") (class "Default")
      (node (ref "U$556") (pin "VIA") (pinfunction "VIA_VIA") (pintype "bidirectional"))
    )
    (net (code "547") (name "unconnected-(U$557-PadVIA)") (class "Default")
      (node (ref "U$557") (pin "VIA") (pinfunction "VIA_VIA") (pintype "bidirectional"))
    )
    (net (code "548") (name "unconnected-(U$558-PadVIA)") (class "Default")
      (node (ref "U$558") (pin "VIA") (pinfunction "VIA_VIA") (pintype "bidirectional"))
    )
    (net (code "549") (name "unconnected-(U$559-PadVIA)") (class "Default")
      (node (ref "U$559") (pin "VIA") (pinfunction "VIA_VIA") (pintype "bidirectional"))
    )
    (net (code "550") (name "unconnected-(U$560-PadVIA)") (class "Default")
      (node (ref "U$560") (pin "VIA") (pinfunction "VIA_VIA") (pintype "bidirectional"))
    )
    (net (code "551") (name "unconnected-(U$561-PadVIA)") (class "Default")
      (node (ref "U$561") (pin "VIA") (pinfunction "VIA_VIA") (pintype "bidirectional"))
    )
    (net (code "552") (name "unconnected-(U$562-PadVIA)") (class "Default")
      (node (ref "U$562") (pin "VIA") (pinfunction "VIA_VIA") (pintype "bidirectional"))
    )
    (net (code "553") (name "unconnected-(U$563-PadVIA)") (class "Default")
      (node (ref "U$563") (pin "VIA") (pinfunction "VIA_VIA") (pintype "bidirectional"))
    )
    (net (code "554") (name "unconnected-(U$564-PadVIA)") (class "Default")
      (node (ref "U$564") (pin "VIA") (pinfunction "VIA_VIA") (pintype "bidirectional"))
    )
    (net (code "555") (name "unconnected-(U$565-PadVIA)") (class "Default")
      (node (ref "U$565") (pin "VIA") (pinfunction "VIA_VIA") (pintype "bidirectional"))
    )
    (net (code "556") (name "unconnected-(U$566-PadVIA)") (class "Default")
      (node (ref "U$566") (pin "VIA") (pinfunction "VIA_VIA") (pintype "bidirectional"))
    )
    (net (code "557") (name "unconnected-(U$567-PadVIA)") (class "Default")
      (node (ref "U$567") (pin "VIA") (pinfunction "VIA_VIA") (pintype "bidirectional"))
    )
    (net (code "558") (name "unconnected-(U$568-PadVIA)") (class "Default")
      (node (ref "U$568") (pin "VIA") (pinfunction "VIA_VIA") (pintype "bidirectional"))
    )
    (net (code "559") (name "unconnected-(U$569-PadVIA)") (class "Default")
      (node (ref "U$569") (pin "VIA") (pinfunction "VIA_VIA") (pintype "bidirectional"))
    )
    (net (code "560") (name "unconnected-(U$570-PadVIA)") (class "Default")
      (node (ref "U$570") (pin "VIA") (pinfunction "VIA_VIA") (pintype "bidirectional"))
    )
    (net (code "561") (name "unconnected-(U$571-PadVIA)") (class "Default")
      (node (ref "U$571") (pin "VIA") (pinfunction "VIA_VIA") (pintype "bidirectional"))
    )
    (net (code "562") (name "unconnected-(U$572-PadVIA)") (class "Default")
      (node (ref "U$572") (pin "VIA") (pinfunction "VIA_VIA") (pintype "bidirectional"))
    )
    (net (code "563") (name "unconnected-(U$573-PadVIA)") (class "Default")
      (node (ref "U$573") (pin "VIA") (pinfunction "VIA_VIA") (pintype "bidirectional"))
    )
    (net (code "564") (name "unconnected-(U$574-PadVIA)") (class "Default")
      (node (ref "U$574") (pin "VIA") (pinfunction "VIA_VIA") (pintype "bidirectional"))
    )
    (net (code "565") (name "unconnected-(U$575-PadVIA)") (class "Default")
      (node (ref "U$575") (pin "VIA") (pinfunction "VIA_VIA") (pintype "bidirectional"))
    )
    (net (code "566") (name "unconnected-(U$585-PadVIA)") (class "Default")
      (node (ref "U$585") (pin "VIA") (pinfunction "VIA_VIA") (pintype "bidirectional"))
    )
    (net (code "567") (name "unconnected-(U$586-PadVIA)") (class "Default")
      (node (ref "U$586") (pin "VIA") (pinfunction "VIA_VIA") (pintype "bidirectional"))
    )
    (net (code "568") (name "unconnected-(U$587-PadVIA)") (class "Default")
      (node (ref "U$587") (pin "VIA") (pinfunction "VIA_VIA") (pintype "bidirectional"))
    )
    (net (code "569") (name "unconnected-(U$588-PadVIA)") (class "Default")
      (node (ref "U$588") (pin "VIA") (pinfunction "VIA_VIA") (pintype "bidirectional"))
    )
  )
)
